# UCirKitBreadboardWithEverythingTop-08201.net
KiCad netlist of a schematic drawn in EAGLE
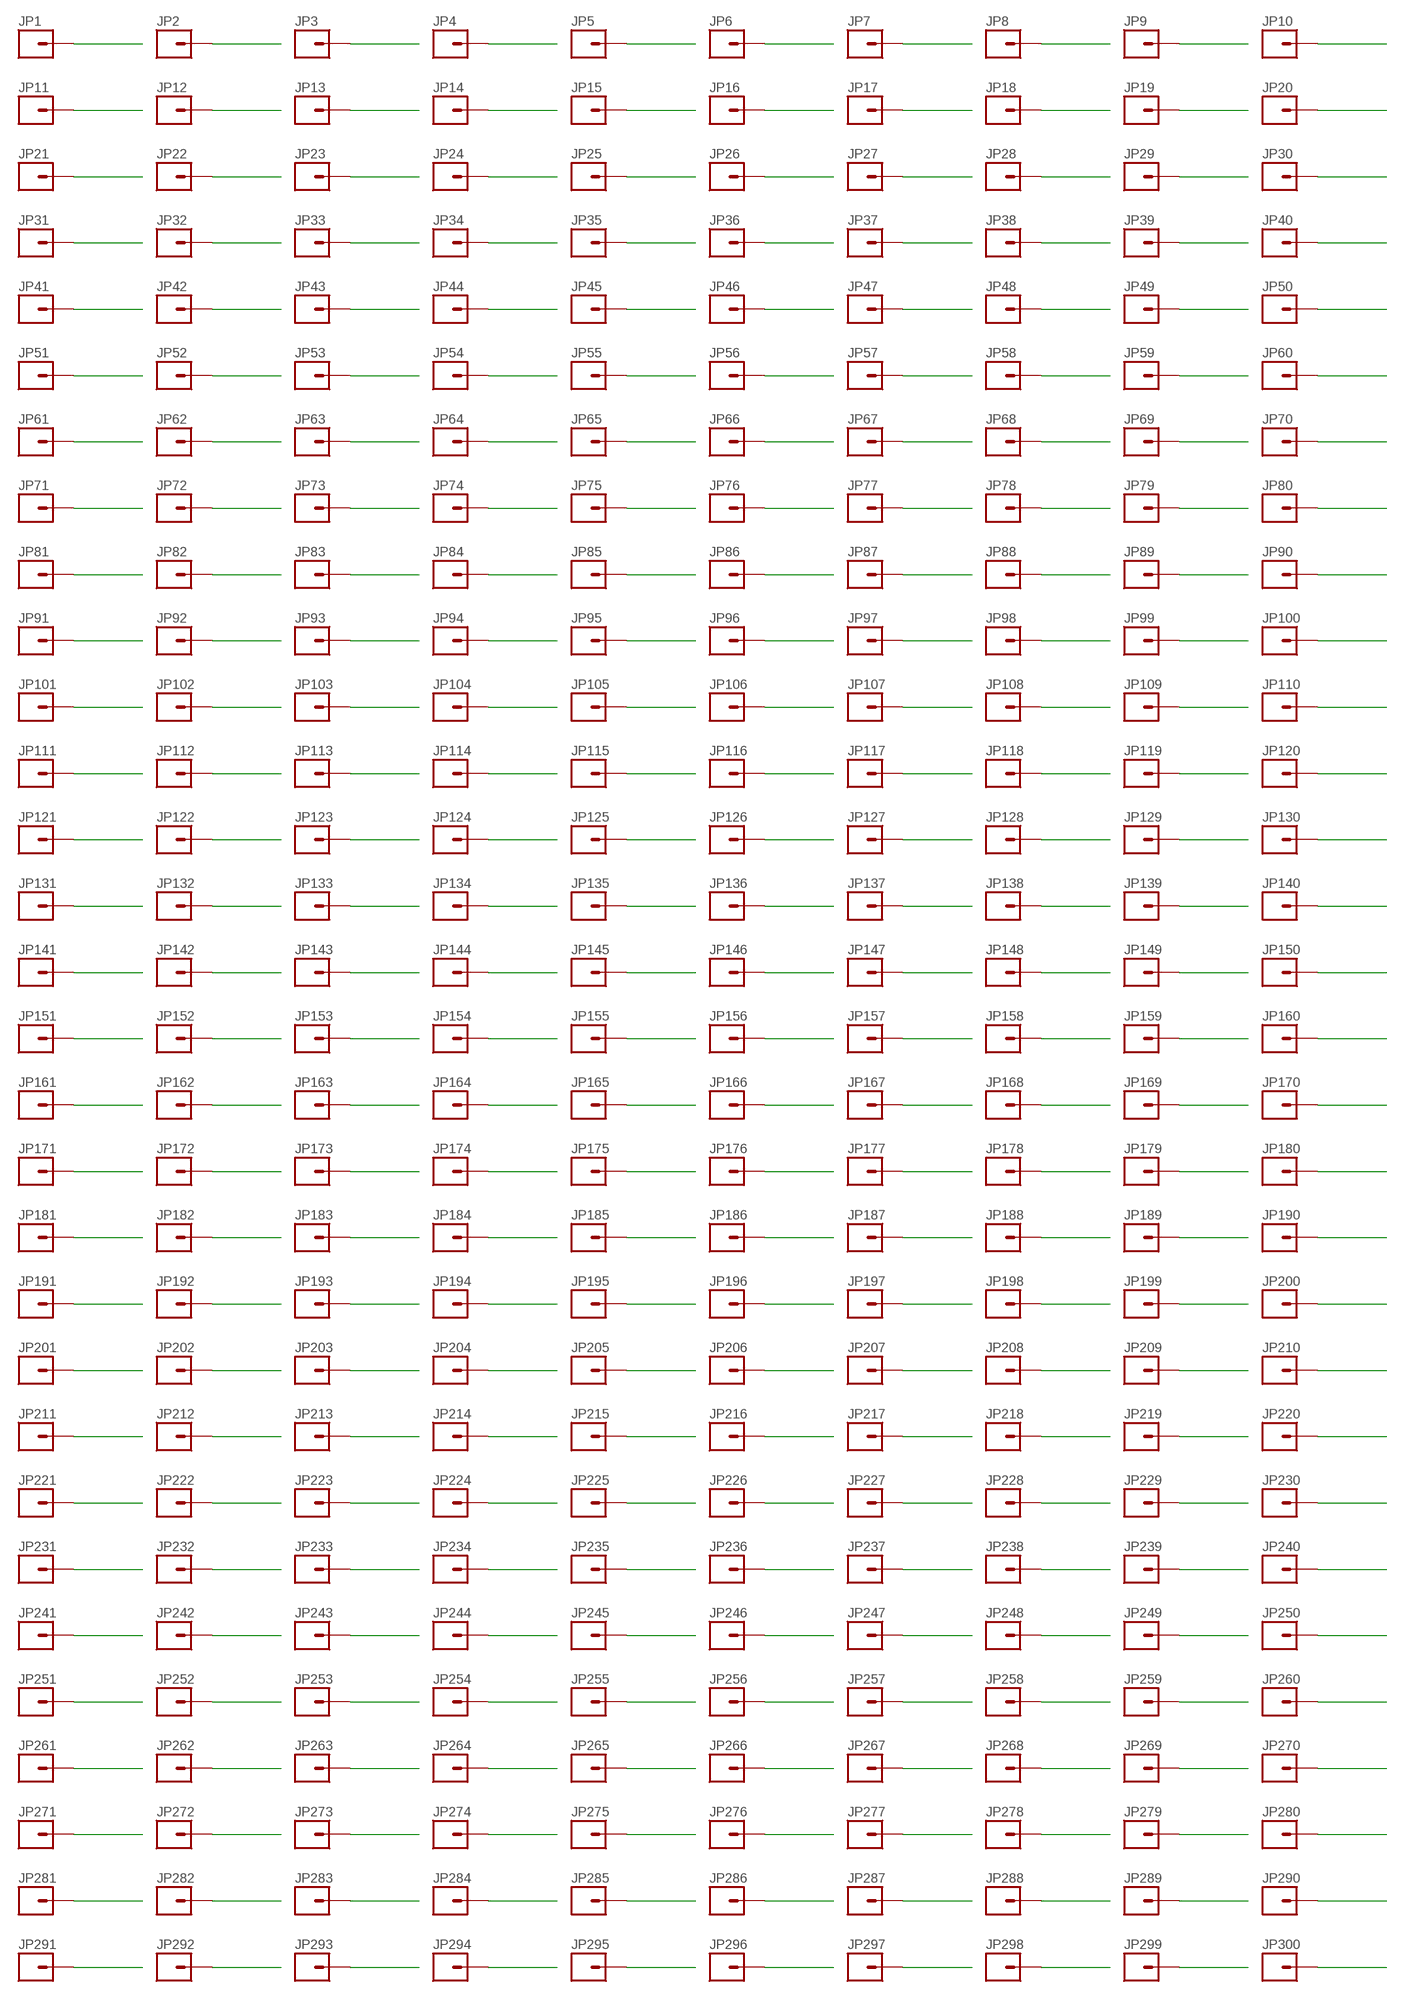
[diagram p0: schematic, sheet 1, part 1 of 2]
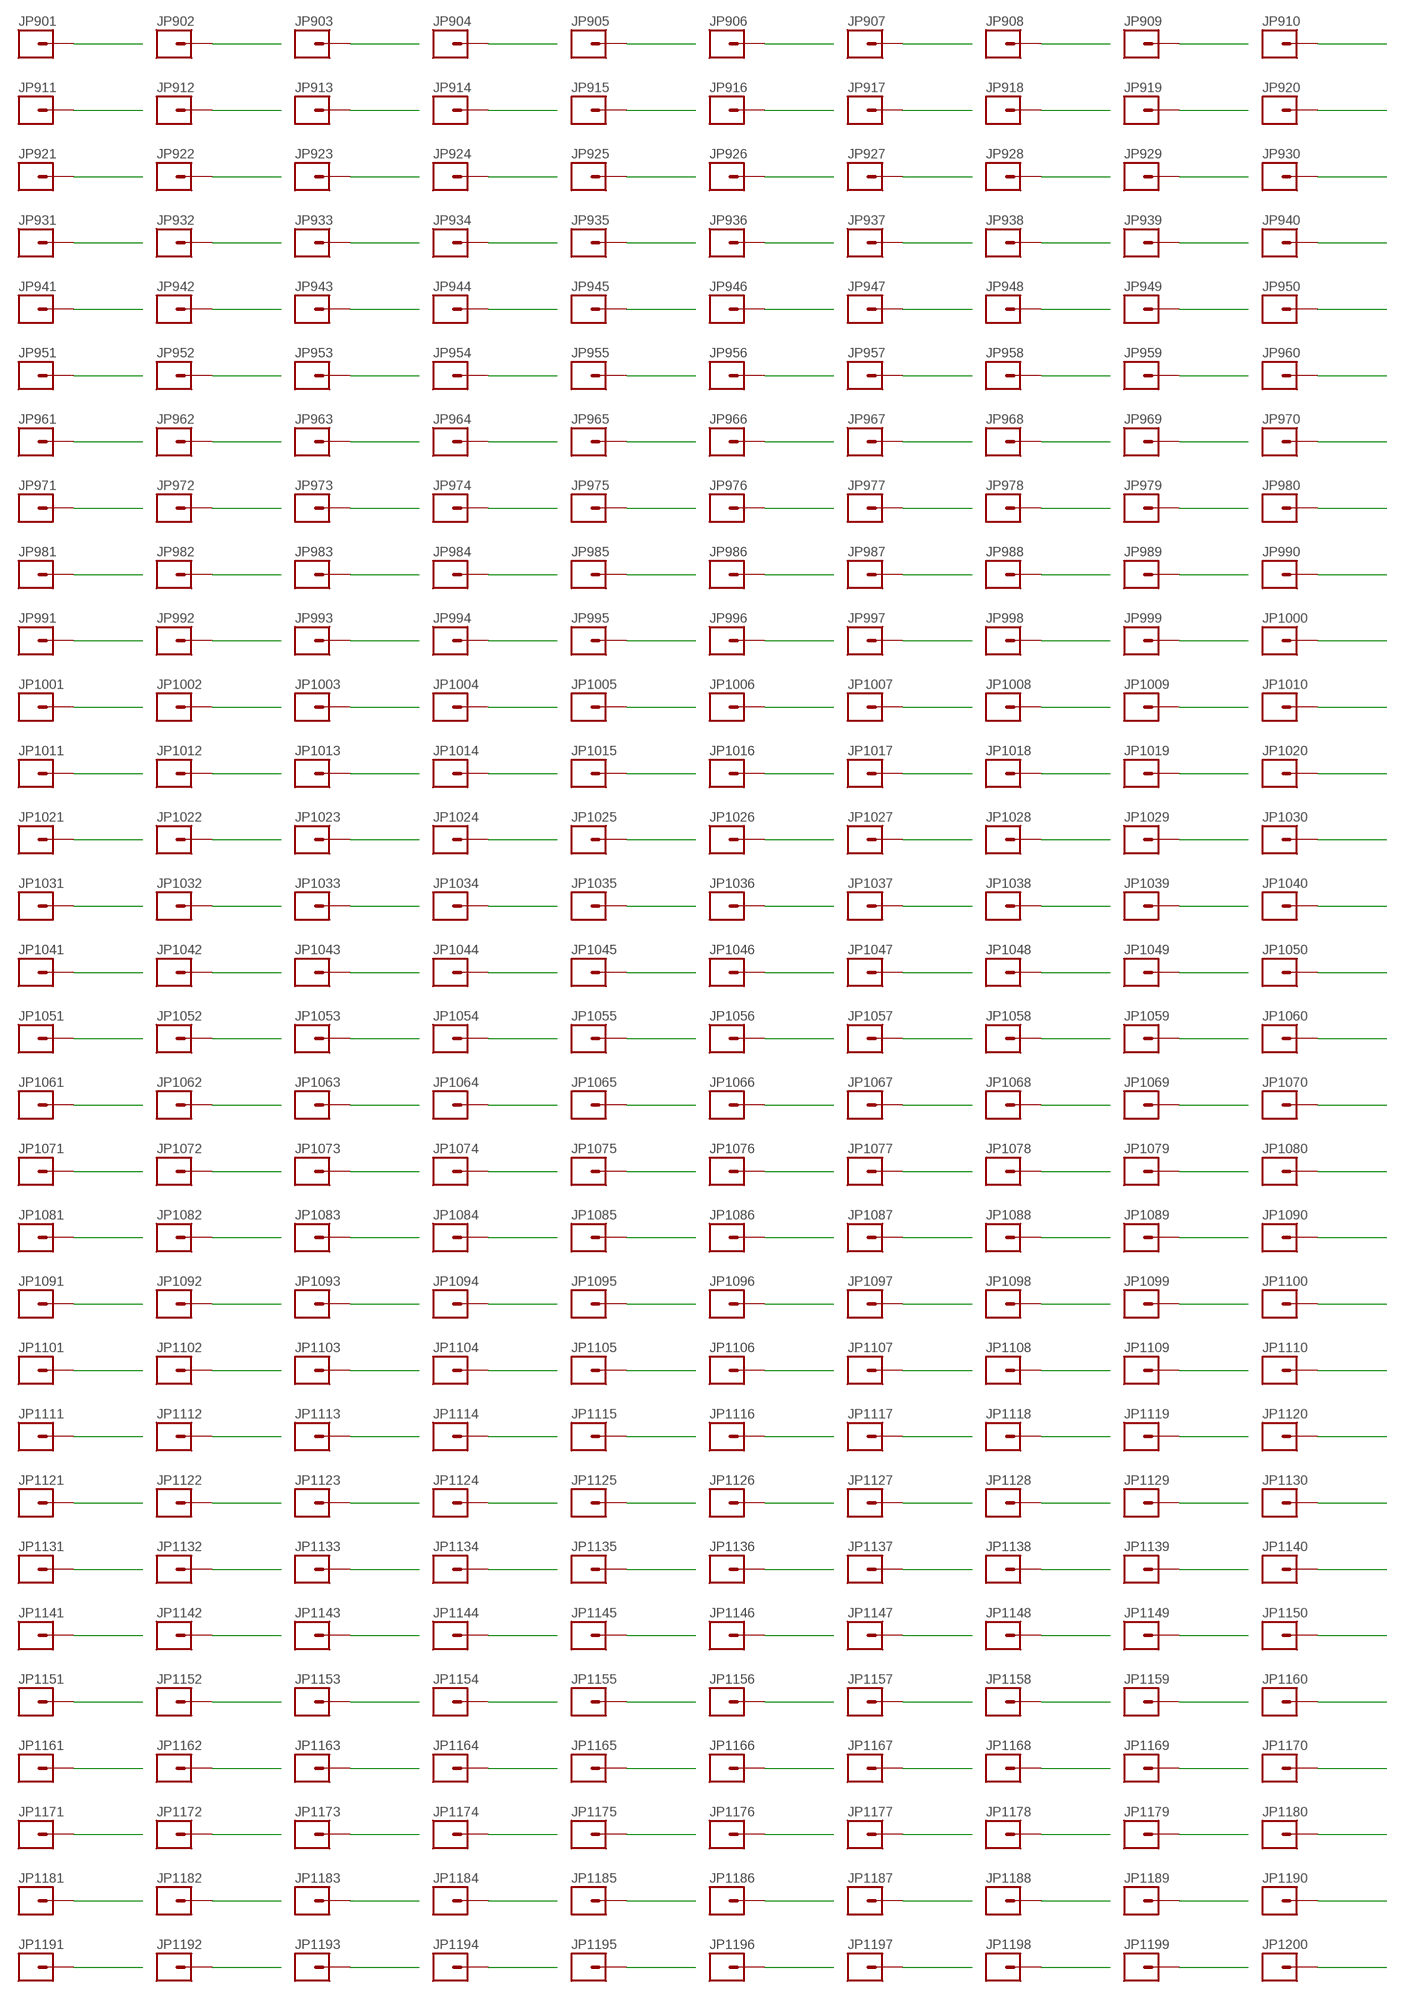
[diagram p1: schematic, sheet 1, part 2 of 2]

(export (version "E")
  (design (tool "Eeschema 10.0.6"))
  (components
    (comp (ref "JP1")
      (value "M01PTH_WITHOUT_TEXT")
      (footprint "eagle-import:1X01_WITHOUT_TEXT")
      (libsource (lib "eagle-import") (part "M01PTH_WITHOUT_TEXT"))
    )
    (comp (ref "JP2")
      (value "M01PTH_WITHOUT_TEXT")
      (footprint "eagle-import:1X01_WITHOUT_TEXT")
      (libsource (lib "eagle-import") (part "M01PTH_WITHOUT_TEXT"))
    )
    (comp (ref "JP3")
      (value "M01PTH_WITHOUT_TEXT")
      (footprint "eagle-import:1X01_WITHOUT_TEXT")
      (libsource (lib "eagle-import") (part "M01PTH_WITHOUT_TEXT"))
    )
    (comp (ref "JP4")
      (value "M01PTH_WITHOUT_TEXT")
      (footprint "eagle-import:1X01_WITHOUT_TEXT")
      (libsource (lib "eagle-import") (part "M01PTH_WITHOUT_TEXT"))
    )
    (comp (ref "JP5")
      (value "M01PTH_WITHOUT_TEXT")
      (footprint "eagle-import:1X01_WITHOUT_TEXT")
      (libsource (lib "eagle-import") (part "M01PTH_WITHOUT_TEXT"))
    )
    (comp (ref "JP6")
      (value "M01PTH_WITHOUT_TEXT")
      (footprint "eagle-import:1X01_WITHOUT_TEXT")
      (libsource (lib "eagle-import") (part "M01PTH_WITHOUT_TEXT"))
    )
    (comp (ref "JP7")
      (value "M01PTH_WITHOUT_TEXT")
      (footprint "eagle-import:1X01_WITHOUT_TEXT")
      (libsource (lib "eagle-import") (part "M01PTH_WITHOUT_TEXT"))
    )
    (comp (ref "JP8")
      (value "M01PTH_WITHOUT_TEXT")
      (footprint "eagle-import:1X01_WITHOUT_TEXT")
      (libsource (lib "eagle-import") (part "M01PTH_WITHOUT_TEXT"))
    )
    (comp (ref "JP9")
      (value "M01PTH_WITHOUT_TEXT")
      (footprint "eagle-import:1X01_WITHOUT_TEXT")
      (libsource (lib "eagle-import") (part "M01PTH_WITHOUT_TEXT"))
    )
    (comp (ref "JP10")
      (value "M01PTH_WITHOUT_TEXT")
      (footprint "eagle-import:1X01_WITHOUT_TEXT")
      (libsource (lib "eagle-import") (part "M01PTH_WITHOUT_TEXT"))
    )
    (comp (ref "JP11")
      (value "M01PTH_WITHOUT_TEXT")
      (footprint "eagle-import:1X01_WITHOUT_TEXT")
      (libsource (lib "eagle-import") (part "M01PTH_WITHOUT_TEXT"))
    )
    (comp (ref "JP12")
      (value "M01PTH_WITHOUT_TEXT")
      (footprint "eagle-import:1X01_WITHOUT_TEXT")
      (libsource (lib "eagle-import") (part "M01PTH_WITHOUT_TEXT"))
    )
    (comp (ref "JP13")
      (value "M01PTH_WITHOUT_TEXT")
      (footprint "eagle-import:1X01_WITHOUT_TEXT")
      (libsource (lib "eagle-import") (part "M01PTH_WITHOUT_TEXT"))
    )
    (comp (ref "JP14")
      (value "M01PTH_WITHOUT_TEXT")
      (footprint "eagle-import:1X01_WITHOUT_TEXT")
      (libsource (lib "eagle-import") (part "M01PTH_WITHOUT_TEXT"))
    )
    (comp (ref "JP15")
      (value "M01PTH_WITHOUT_TEXT")
      (footprint "eagle-import:1X01_WITHOUT_TEXT")
      (libsource (lib "eagle-import") (part "M01PTH_WITHOUT_TEXT"))
    )
    (comp (ref "JP16")
      (value "M01PTH_WITHOUT_TEXT")
      (footprint "eagle-import:1X01_WITHOUT_TEXT")
      (libsource (lib "eagle-import") (part "M01PTH_WITHOUT_TEXT"))
    )
    (comp (ref "JP17")
      (value "M01PTH_WITHOUT_TEXT")
      (footprint "eagle-import:1X01_WITHOUT_TEXT")
      (libsource (lib "eagle-import") (part "M01PTH_WITHOUT_TEXT"))
    )
    (comp (ref "JP18")
      (value "M01PTH_WITHOUT_TEXT")
      (footprint "eagle-import:1X01_WITHOUT_TEXT")
      (libsource (lib "eagle-import") (part "M01PTH_WITHOUT_TEXT"))
    )
    (comp (ref "JP19")
      (value "M01PTH_WITHOUT_TEXT")
      (footprint "eagle-import:1X01_WITHOUT_TEXT")
      (libsource (lib "eagle-import") (part "M01PTH_WITHOUT_TEXT"))
    )
    (comp (ref "JP20")
      (value "M01PTH_WITHOUT_TEXT")
      (footprint "eagle-import:1X01_WITHOUT_TEXT")
      (libsource (lib "eagle-import") (part "M01PTH_WITHOUT_TEXT"))
    )
    (comp (ref "JP21")
      (value "M01PTH_WITHOUT_TEXT")
      (footprint "eagle-import:1X01_WITHOUT_TEXT")
      (libsource (lib "eagle-import") (part "M01PTH_WITHOUT_TEXT"))
    )
    (comp (ref "JP22")
      (value "M01PTH_WITHOUT_TEXT")
      (footprint "eagle-import:1X01_WITHOUT_TEXT")
      (libsource (lib "eagle-import") (part "M01PTH_WITHOUT_TEXT"))
    )
    (comp (ref "JP23")
      (value "M01PTH_WITHOUT_TEXT")
      (footprint "eagle-import:1X01_WITHOUT_TEXT")
      (libsource (lib "eagle-import") (part "M01PTH_WITHOUT_TEXT"))
    )
    (comp (ref "JP24")
      (value "M01PTH_WITHOUT_TEXT")
      (footprint "eagle-import:1X01_WITHOUT_TEXT")
      (libsource (lib "eagle-import") (part "M01PTH_WITHOUT_TEXT"))
    )
    (comp (ref "JP25")
      (value "M01PTH_WITHOUT_TEXT")
      (footprint "eagle-import:1X01_WITHOUT_TEXT")
      (libsource (lib "eagle-import") (part "M01PTH_WITHOUT_TEXT"))
    )
    (comp (ref "JP26")
      (value "M01PTH_WITHOUT_TEXT")
      (footprint "eagle-import:1X01_WITHOUT_TEXT")
      (libsource (lib "eagle-import") (part "M01PTH_WITHOUT_TEXT"))
    )
    (comp (ref "JP27")
      (value "M01PTH_WITHOUT_TEXT")
      (footprint "eagle-import:1X01_WITHOUT_TEXT")
      (libsource (lib "eagle-import") (part "M01PTH_WITHOUT_TEXT"))
    )
    (comp (ref "JP28")
      (value "M01PTH_WITHOUT_TEXT")
      (footprint "eagle-import:1X01_WITHOUT_TEXT")
      (libsource (lib "eagle-import") (part "M01PTH_WITHOUT_TEXT"))
    )
    (comp (ref "JP29")
      (value "M01PTH_WITHOUT_TEXT")
      (footprint "eagle-import:1X01_WITHOUT_TEXT")
      (libsource (lib "eagle-import") (part "M01PTH_WITHOUT_TEXT"))
    )
    (comp (ref "JP30")
      (value "M01PTH_WITHOUT_TEXT")
      (footprint "eagle-import:1X01_WITHOUT_TEXT")
      (libsource (lib "eagle-import") (part "M01PTH_WITHOUT_TEXT"))
    )
    (comp (ref "JP31")
      (value "M01PTH_WITHOUT_TEXT")
      (footprint "eagle-import:1X01_WITHOUT_TEXT")
      (libsource (lib "eagle-import") (part "M01PTH_WITHOUT_TEXT"))
    )
    (comp (ref "JP32")
      (value "M01PTH_WITHOUT_TEXT")
      (footprint "eagle-import:1X01_WITHOUT_TEXT")
      (libsource (lib "eagle-import") (part "M01PTH_WITHOUT_TEXT"))
    )
    (comp (ref "JP33")
      (value "M01PTH_WITHOUT_TEXT")
      (footprint "eagle-import:1X01_WITHOUT_TEXT")
      (libsource (lib "eagle-import") (part "M01PTH_WITHOUT_TEXT"))
    )
    (comp (ref "JP34")
      (value "M01PTH_WITHOUT_TEXT")
      (footprint "eagle-import:1X01_WITHOUT_TEXT")
      (libsource (lib "eagle-import") (part "M01PTH_WITHOUT_TEXT"))
    )
    (comp (ref "JP35")
      (value "M01PTH_WITHOUT_TEXT")
      (footprint "eagle-import:1X01_WITHOUT_TEXT")
      (libsource (lib "eagle-import") (part "M01PTH_WITHOUT_TEXT"))
    )
    (comp (ref "JP36")
      (value "M01PTH_WITHOUT_TEXT")
      (footprint "eagle-import:1X01_WITHOUT_TEXT")
      (libsource (lib "eagle-import") (part "M01PTH_WITHOUT_TEXT"))
    )
    (comp (ref "JP37")
      (value "M01PTH_WITHOUT_TEXT")
      (footprint "eagle-import:1X01_WITHOUT_TEXT")
      (libsource (lib "eagle-import") (part "M01PTH_WITHOUT_TEXT"))
    )
    (comp (ref "JP38")
      (value "M01PTH_WITHOUT_TEXT")
      (footprint "eagle-import:1X01_WITHOUT_TEXT")
      (libsource (lib "eagle-import") (part "M01PTH_WITHOUT_TEXT"))
    )
    (comp (ref "JP39")
      (value "M01PTH_WITHOUT_TEXT")
      (footprint "eagle-import:1X01_WITHOUT_TEXT")
      (libsource (lib "eagle-import") (part "M01PTH_WITHOUT_TEXT"))
    )
    (comp (ref "JP40")
      (value "M01PTH_WITHOUT_TEXT")
      (footprint "eagle-import:1X01_WITHOUT_TEXT")
      (libsource (lib "eagle-import") (part "M01PTH_WITHOUT_TEXT"))
    )
    (comp (ref "JP41")
      (value "M01PTH_WITHOUT_TEXT")
      (footprint "eagle-import:1X01_WITHOUT_TEXT")
      (libsource (lib "eagle-import") (part "M01PTH_WITHOUT_TEXT"))
    )
    (comp (ref "JP42")
      (value "M01PTH_WITHOUT_TEXT")
      (footprint "eagle-import:1X01_WITHOUT_TEXT")
      (libsource (lib "eagle-import") (part "M01PTH_WITHOUT_TEXT"))
    )
    (comp (ref "JP43")
      (value "M01PTH_WITHOUT_TEXT")
      (footprint "eagle-import:1X01_WITHOUT_TEXT")
      (libsource (lib "eagle-import") (part "M01PTH_WITHOUT_TEXT"))
    )
    (comp (ref "JP44")
      (value "M01PTH_WITHOUT_TEXT")
      (footprint "eagle-import:1X01_WITHOUT_TEXT")
      (libsource (lib "eagle-import") (part "M01PTH_WITHOUT_TEXT"))
    )
    (comp (ref "JP45")
      (value "M01PTH_WITHOUT_TEXT")
      (footprint "eagle-import:1X01_WITHOUT_TEXT")
      (libsource (lib "eagle-import") (part "M01PTH_WITHOUT_TEXT"))
    )
    (comp (ref "JP46")
      (value "M01PTH_WITHOUT_TEXT")
      (footprint "eagle-import:1X01_WITHOUT_TEXT")
      (libsource (lib "eagle-import") (part "M01PTH_WITHOUT_TEXT"))
    )
    (comp (ref "JP47")
      (value "M01PTH_WITHOUT_TEXT")
      (footprint "eagle-import:1X01_WITHOUT_TEXT")
      (libsource (lib "eagle-import") (part "M01PTH_WITHOUT_TEXT"))
    )
    (comp (ref "JP48")
      (value "M01PTH_WITHOUT_TEXT")
      (footprint "eagle-import:1X01_WITHOUT_TEXT")
      (libsource (lib "eagle-import") (part "M01PTH_WITHOUT_TEXT"))
    )
    (comp (ref "JP49")
      (value "M01PTH_WITHOUT_TEXT")
      (footprint "eagle-import:1X01_WITHOUT_TEXT")
      (libsource (lib "eagle-import") (part "M01PTH_WITHOUT_TEXT"))
    )
    (comp (ref "JP50")
      (value "M01PTH_WITHOUT_TEXT")
      (footprint "eagle-import:1X01_WITHOUT_TEXT")
      (libsource (lib "eagle-import") (part "M01PTH_WITHOUT_TEXT"))
    )
    (comp (ref "JP51")
      (value "M01PTH_WITHOUT_TEXT")
      (footprint "eagle-import:1X01_WITHOUT_TEXT")
      (libsource (lib "eagle-import") (part "M01PTH_WITHOUT_TEXT"))
    )
    (comp (ref "JP52")
      (value "M01PTH_WITHOUT_TEXT")
      (footprint "eagle-import:1X01_WITHOUT_TEXT")
      (libsource (lib "eagle-import") (part "M01PTH_WITHOUT_TEXT"))
    )
    (comp (ref "JP53")
      (value "M01PTH_WITHOUT_TEXT")
      (footprint "eagle-import:1X01_WITHOUT_TEXT")
      (libsource (lib "eagle-import") (part "M01PTH_WITHOUT_TEXT"))
    )
    (comp (ref "JP54")
      (value "M01PTH_WITHOUT_TEXT")
      (footprint "eagle-import:1X01_WITHOUT_TEXT")
      (libsource (lib "eagle-import") (part "M01PTH_WITHOUT_TEXT"))
    )
    (comp (ref "JP55")
      (value "M01PTH_WITHOUT_TEXT")
      (footprint "eagle-import:1X01_WITHOUT_TEXT")
      (libsource (lib "eagle-import") (part "M01PTH_WITHOUT_TEXT"))
    )
    (comp (ref "JP56")
      (value "M01PTH_WITHOUT_TEXT")
      (footprint "eagle-import:1X01_WITHOUT_TEXT")
      (libsource (lib "eagle-import") (part "M01PTH_WITHOUT_TEXT"))
    )
    (comp (ref "JP57")
      (value "M01PTH_WITHOUT_TEXT")
      (footprint "eagle-import:1X01_WITHOUT_TEXT")
      (libsource (lib "eagle-import") (part "M01PTH_WITHOUT_TEXT"))
    )
    (comp (ref "JP58")
      (value "M01PTH_WITHOUT_TEXT")
      (footprint "eagle-import:1X01_WITHOUT_TEXT")
      (libsource (lib "eagle-import") (part "M01PTH_WITHOUT_TEXT"))
    )
    (comp (ref "JP59")
      (value "M01PTH_WITHOUT_TEXT")
      (footprint "eagle-import:1X01_WITHOUT_TEXT")
      (libsource (lib "eagle-import") (part "M01PTH_WITHOUT_TEXT"))
    )
    (comp (ref "JP60")
      (value "M01PTH_WITHOUT_TEXT")
      (footprint "eagle-import:1X01_WITHOUT_TEXT")
      (libsource (lib "eagle-import") (part "M01PTH_WITHOUT_TEXT"))
    )
    (comp (ref "JP61")
      (value "M01PTH_WITHOUT_TEXT")
      (footprint "eagle-import:1X01_WITHOUT_TEXT")
      (libsource (lib "eagle-import") (part "M01PTH_WITHOUT_TEXT"))
    )
    (comp (ref "JP62")
      (value "M01PTH_WITHOUT_TEXT")
      (footprint "eagle-import:1X01_WITHOUT_TEXT")
      (libsource (lib "eagle-import") (part "M01PTH_WITHOUT_TEXT"))
    )
    (comp (ref "JP63")
      (value "M01PTH_WITHOUT_TEXT")
      (footprint "eagle-import:1X01_WITHOUT_TEXT")
      (libsource (lib "eagle-import") (part "M01PTH_WITHOUT_TEXT"))
    )
    (comp (ref "JP64")
      (value "M01PTH_WITHOUT_TEXT")
      (footprint "eagle-import:1X01_WITHOUT_TEXT")
      (libsource (lib "eagle-import") (part "M01PTH_WITHOUT_TEXT"))
    )
    (comp (ref "JP65")
      (value "M01PTH_WITHOUT_TEXT")
      (footprint "eagle-import:1X01_WITHOUT_TEXT")
      (libsource (lib "eagle-import") (part "M01PTH_WITHOUT_TEXT"))
    )
    (comp (ref "JP66")
      (value "M01PTH_WITHOUT_TEXT")
      (footprint "eagle-import:1X01_WITHOUT_TEXT")
      (libsource (lib "eagle-import") (part "M01PTH_WITHOUT_TEXT"))
    )
    (comp (ref "JP67")
      (value "M01PTH_WITHOUT_TEXT")
      (footprint "eagle-import:1X01_WITHOUT_TEXT")
      (libsource (lib "eagle-import") (part "M01PTH_WITHOUT_TEXT"))
    )
    (comp (ref "JP68")
      (value "M01PTH_WITHOUT_TEXT")
      (footprint "eagle-import:1X01_WITHOUT_TEXT")
      (libsource (lib "eagle-import") (part "M01PTH_WITHOUT_TEXT"))
    )
    (comp (ref "JP69")
      (value "M01PTH_WITHOUT_TEXT")
      (footprint "eagle-import:1X01_WITHOUT_TEXT")
      (libsource (lib "eagle-import") (part "M01PTH_WITHOUT_TEXT"))
    )
    (comp (ref "JP70")
      (value "M01PTH_WITHOUT_TEXT")
      (footprint "eagle-import:1X01_WITHOUT_TEXT")
      (libsource (lib "eagle-import") (part "M01PTH_WITHOUT_TEXT"))
    )
    (comp (ref "JP71")
      (value "M01PTH_WITHOUT_TEXT")
      (footprint "eagle-import:1X01_WITHOUT_TEXT")
      (libsource (lib "eagle-import") (part "M01PTH_WITHOUT_TEXT"))
    )
    (comp (ref "JP72")
      (value "M01PTH_WITHOUT_TEXT")
      (footprint "eagle-import:1X01_WITHOUT_TEXT")
      (libsource (lib "eagle-import") (part "M01PTH_WITHOUT_TEXT"))
    )
    (comp (ref "JP73")
      (value "M01PTH_WITHOUT_TEXT")
      (footprint "eagle-import:1X01_WITHOUT_TEXT")
      (libsource (lib "eagle-import") (part "M01PTH_WITHOUT_TEXT"))
    )
    (comp (ref "JP74")
      (value "M01PTH_WITHOUT_TEXT")
      (footprint "eagle-import:1X01_WITHOUT_TEXT")
      (libsource (lib "eagle-import") (part "M01PTH_WITHOUT_TEXT"))
    )
    (comp (ref "JP75")
      (value "M01PTH_WITHOUT_TEXT")
      (footprint "eagle-import:1X01_WITHOUT_TEXT")
      (libsource (lib "eagle-import") (part "M01PTH_WITHOUT_TEXT"))
    )
    (comp (ref "JP76")
      (value "M01PTH_WITHOUT_TEXT")
      (footprint "eagle-import:1X01_WITHOUT_TEXT")
      (libsource (lib "eagle-import") (part "M01PTH_WITHOUT_TEXT"))
    )
    (comp (ref "JP77")
      (value "M01PTH_WITHOUT_TEXT")
      (footprint "eagle-import:1X01_WITHOUT_TEXT")
      (libsource (lib "eagle-import") (part "M01PTH_WITHOUT_TEXT"))
    )
    (comp (ref "JP78")
      (value "M01PTH_WITHOUT_TEXT")
      (footprint "eagle-import:1X01_WITHOUT_TEXT")
      (libsource (lib "eagle-import") (part "M01PTH_WITHOUT_TEXT"))
    )
    (comp (ref "JP79")
      (value "M01PTH_WITHOUT_TEXT")
      (footprint "eagle-import:1X01_WITHOUT_TEXT")
      (libsource (lib "eagle-import") (part "M01PTH_WITHOUT_TEXT"))
    )
    (comp (ref "JP80")
      (value "M01PTH_WITHOUT_TEXT")
      (footprint "eagle-import:1X01_WITHOUT_TEXT")
      (libsource (lib "eagle-import") (part "M01PTH_WITHOUT_TEXT"))
    )
    (comp (ref "JP81")
      (value "M01PTH_WITHOUT_TEXT")
      (footprint "eagle-import:1X01_WITHOUT_TEXT")
      (libsource (lib "eagle-import") (part "M01PTH_WITHOUT_TEXT"))
    )
    (comp (ref "JP82")
      (value "M01PTH_WITHOUT_TEXT")
      (footprint "eagle-import:1X01_WITHOUT_TEXT")
      (libsource (lib "eagle-import") (part "M01PTH_WITHOUT_TEXT"))
    )
    (comp (ref "JP83")
      (value "M01PTH_WITHOUT_TEXT")
      (footprint "eagle-import:1X01_WITHOUT_TEXT")
      (libsource (lib "eagle-import") (part "M01PTH_WITHOUT_TEXT"))
    )
    (comp (ref "JP84")
      (value "M01PTH_WITHOUT_TEXT")
      (footprint "eagle-import:1X01_WITHOUT_TEXT")
      (libsource (lib "eagle-import") (part "M01PTH_WITHOUT_TEXT"))
    )
    (comp (ref "JP85")
      (value "M01PTH_WITHOUT_TEXT")
      (footprint "eagle-import:1X01_WITHOUT_TEXT")
      (libsource (lib "eagle-import") (part "M01PTH_WITHOUT_TEXT"))
    )
    (comp (ref "JP86")
      (value "M01PTH_WITHOUT_TEXT")
      (footprint "eagle-import:1X01_WITHOUT_TEXT")
      (libsource (lib "eagle-import") (part "M01PTH_WITHOUT_TEXT"))
    )
    (comp (ref "JP87")
      (value "M01PTH_WITHOUT_TEXT")
      (footprint "eagle-import:1X01_WITHOUT_TEXT")
      (libsource (lib "eagle-import") (part "M01PTH_WITHOUT_TEXT"))
    )
    (comp (ref "JP88")
      (value "M01PTH_WITHOUT_TEXT")
      (footprint "eagle-import:1X01_WITHOUT_TEXT")
      (libsource (lib "eagle-import") (part "M01PTH_WITHOUT_TEXT"))
    )
    (comp (ref "JP89")
      (value "M01PTH_WITHOUT_TEXT")
      (footprint "eagle-import:1X01_WITHOUT_TEXT")
      (libsource (lib "eagle-import") (part "M01PTH_WITHOUT_TEXT"))
    )
    (comp (ref "JP90")
      (value "M01PTH_WITHOUT_TEXT")
      (footprint "eagle-import:1X01_WITHOUT_TEXT")
      (libsource (lib "eagle-import") (part "M01PTH_WITHOUT_TEXT"))
    )
    (comp (ref "JP91")
      (value "M01PTH_WITHOUT_TEXT")
      (footprint "eagle-import:1X01_WITHOUT_TEXT")
      (libsource (lib "eagle-import") (part "M01PTH_WITHOUT_TEXT"))
    )
    (comp (ref "JP92")
      (value "M01PTH_WITHOUT_TEXT")
      (footprint "eagle-import:1X01_WITHOUT_TEXT")
      (libsource (lib "eagle-import") (part "M01PTH_WITHOUT_TEXT"))
    )
    (comp (ref "JP93")
      (value "M01PTH_WITHOUT_TEXT")
      (footprint "eagle-import:1X01_WITHOUT_TEXT")
      (libsource (lib "eagle-import") (part "M01PTH_WITHOUT_TEXT"))
    )
    (comp (ref "JP94")
      (value "M01PTH_WITHOUT_TEXT")
      (footprint "eagle-import:1X01_WITHOUT_TEXT")
      (libsource (lib "eagle-import") (part "M01PTH_WITHOUT_TEXT"))
    )
    (comp (ref "JP95")
      (value "M01PTH_WITHOUT_TEXT")
      (footprint "eagle-import:1X01_WITHOUT_TEXT")
      (libsource (lib "eagle-import") (part "M01PTH_WITHOUT_TEXT"))
    )
    (comp (ref "JP96")
      (value "M01PTH_WITHOUT_TEXT")
      (footprint "eagle-import:1X01_WITHOUT_TEXT")
      (libsource (lib "eagle-import") (part "M01PTH_WITHOUT_TEXT"))
    )
    (comp (ref "JP97")
      (value "M01PTH_WITHOUT_TEXT")
      (footprint "eagle-import:1X01_WITHOUT_TEXT")
      (libsource (lib "eagle-import") (part "M01PTH_WITHOUT_TEXT"))
    )
    (comp (ref "JP98")
      (value "M01PTH_WITHOUT_TEXT")
      (footprint "eagle-import:1X01_WITHOUT_TEXT")
      (libsource (lib "eagle-import") (part "M01PTH_WITHOUT_TEXT"))
    )
    (comp (ref "JP99")
      (value "M01PTH_WITHOUT_TEXT")
      (footprint "eagle-import:1X01_WITHOUT_TEXT")
      (libsource (lib "eagle-import") (part "M01PTH_WITHOUT_TEXT"))
    )
    (comp (ref "JP100")
      (value "M01PTH_WITHOUT_TEXT")
      (footprint "eagle-import:1X01_WITHOUT_TEXT")
      (libsource (lib "eagle-import") (part "M01PTH_WITHOUT_TEXT"))
    )
    (comp (ref "JP101")
      (value "M01PTH_WITHOUT_TEXT")
      (footprint "eagle-import:1X01_WITHOUT_TEXT")
      (libsource (lib "eagle-import") (part "M01PTH_WITHOUT_TEXT"))
    )
    (comp (ref "JP102")
      (value "M01PTH_WITHOUT_TEXT")
      (footprint "eagle-import:1X01_WITHOUT_TEXT")
      (libsource (lib "eagle-import") (part "M01PTH_WITHOUT_TEXT"))
    )
    (comp (ref "JP103")
      (value "M01PTH_WITHOUT_TEXT")
      (footprint "eagle-import:1X01_WITHOUT_TEXT")
      (libsource (lib "eagle-import") (part "M01PTH_WITHOUT_TEXT"))
    )
    (comp (ref "JP104")
      (value "M01PTH_WITHOUT_TEXT")
      (footprint "eagle-import:1X01_WITHOUT_TEXT")
      (libsource (lib "eagle-import") (part "M01PTH_WITHOUT_TEXT"))
    )
    (comp (ref "JP105")
      (value "M01PTH_WITHOUT_TEXT")
      (footprint "eagle-import:1X01_WITHOUT_TEXT")
      (libsource (lib "eagle-import") (part "M01PTH_WITHOUT_TEXT"))
    )
    (comp (ref "JP106")
      (value "M01PTH_WITHOUT_TEXT")
      (footprint "eagle-import:1X01_WITHOUT_TEXT")
      (libsource (lib "eagle-import") (part "M01PTH_WITHOUT_TEXT"))
    )
    (comp (ref "JP107")
      (value "M01PTH_WITHOUT_TEXT")
      (footprint "eagle-import:1X01_WITHOUT_TEXT")
      (libsource (lib "eagle-import") (part "M01PTH_WITHOUT_TEXT"))
    )
    (comp (ref "JP108")
      (value "M01PTH_WITHOUT_TEXT")
      (footprint "eagle-import:1X01_WITHOUT_TEXT")
      (libsource (lib "eagle-import") (part "M01PTH_WITHOUT_TEXT"))
    )
    (comp (ref "JP109")
      (value "M01PTH_WITHOUT_TEXT")
      (footprint "eagle-import:1X01_WITHOUT_TEXT")
      (libsource (lib "eagle-import") (part "M01PTH_WITHOUT_TEXT"))
    )
    (comp (ref "JP110")
      (value "M01PTH_WITHOUT_TEXT")
      (footprint "eagle-import:1X01_WITHOUT_TEXT")
      (libsource (lib "eagle-import") (part "M01PTH_WITHOUT_TEXT"))
    )
    (comp (ref "JP111")
      (value "M01PTH_WITHOUT_TEXT")
      (footprint "eagle-import:1X01_WITHOUT_TEXT")
      (libsource (lib "eagle-import") (part "M01PTH_WITHOUT_TEXT"))
    )
    (comp (ref "JP112")
      (value "M01PTH_WITHOUT_TEXT")
      (footprint "eagle-import:1X01_WITHOUT_TEXT")
      (libsource (lib "eagle-import") (part "M01PTH_WITHOUT_TEXT"))
    )
    (comp (ref "JP113")
      (value "M01PTH_WITHOUT_TEXT")
      (footprint "eagle-import:1X01_WITHOUT_TEXT")
      (libsource (lib "eagle-import") (part "M01PTH_WITHOUT_TEXT"))
    )
    (comp (ref "JP114")
      (value "M01PTH_WITHOUT_TEXT")
      (footprint "eagle-import:1X01_WITHOUT_TEXT")
      (libsource (lib "eagle-import") (part "M01PTH_WITHOUT_TEXT"))
    )
    (comp (ref "JP115")
      (value "M01PTH_WITHOUT_TEXT")
      (footprint "eagle-import:1X01_WITHOUT_TEXT")
      (libsource (lib "eagle-import") (part "M01PTH_WITHOUT_TEXT"))
    )
    (comp (ref "JP116")
      (value "M01PTH_WITHOUT_TEXT")
      (footprint "eagle-import:1X01_WITHOUT_TEXT")
      (libsource (lib "eagle-import") (part "M01PTH_WITHOUT_TEXT"))
    )
    (comp (ref "JP117")
      (value "M01PTH_WITHOUT_TEXT")
      (footprint "eagle-import:1X01_WITHOUT_TEXT")
      (libsource (lib "eagle-import") (part "M01PTH_WITHOUT_TEXT"))
    )
    (comp (ref "JP118")
      (value "M01PTH_WITHOUT_TEXT")
      (footprint "eagle-import:1X01_WITHOUT_TEXT")
      (libsource (lib "eagle-import") (part "M01PTH_WITHOUT_TEXT"))
    )
    (comp (ref "JP119")
      (value "M01PTH_WITHOUT_TEXT")
      (footprint "eagle-import:1X01_WITHOUT_TEXT")
      (libsource (lib "eagle-import") (part "M01PTH_WITHOUT_TEXT"))
    )
    (comp (ref "JP120")
      (value "M01PTH_WITHOUT_TEXT")
      (footprint "eagle-import:1X01_WITHOUT_TEXT")
      (libsource (lib "eagle-import") (part "M01PTH_WITHOUT_TEXT"))
    )
    (comp (ref "JP121")
      (value "M01PTH_WITHOUT_TEXT")
      (footprint "eagle-import:1X01_WITHOUT_TEXT")
      (libsource (lib "eagle-import") (part "M01PTH_WITHOUT_TEXT"))
    )
    (comp (ref "JP122")
      (value "M01PTH_WITHOUT_TEXT")
      (footprint "eagle-import:1X01_WITHOUT_TEXT")
      (libsource (lib "eagle-import") (part "M01PTH_WITHOUT_TEXT"))
    )
    (comp (ref "JP123")
      (value "M01PTH_WITHOUT_TEXT")
      (footprint "eagle-import:1X01_WITHOUT_TEXT")
      (libsource (lib "eagle-import") (part "M01PTH_WITHOUT_TEXT"))
    )
    (comp (ref "JP124")
      (value "M01PTH_WITHOUT_TEXT")
      (footprint "eagle-import:1X01_WITHOUT_TEXT")
      (libsource (lib "eagle-import") (part "M01PTH_WITHOUT_TEXT"))
    )
    (comp (ref "JP125")
      (value "M01PTH_WITHOUT_TEXT")
      (footprint "eagle-import:1X01_WITHOUT_TEXT")
      (libsource (lib "eagle-import") (part "M01PTH_WITHOUT_TEXT"))
    )
    (comp (ref "JP126")
      (value "M01PTH_WITHOUT_TEXT")
      (footprint "eagle-import:1X01_WITHOUT_TEXT")
      (libsource (lib "eagle-import") (part "M01PTH_WITHOUT_TEXT"))
    )
    (comp (ref "JP127")
      (value "M01PTH_WITHOUT_TEXT")
      (footprint "eagle-import:1X01_WITHOUT_TEXT")
      (libsource (lib "eagle-import") (part "M01PTH_WITHOUT_TEXT"))
    )
    (comp (ref "JP128")
      (value "M01PTH_WITHOUT_TEXT")
      (footprint "eagle-import:1X01_WITHOUT_TEXT")
      (libsource (lib "eagle-import") (part "M01PTH_WITHOUT_TEXT"))
    )
    (comp (ref "JP129")
      (value "M01PTH_WITHOUT_TEXT")
      (footprint "eagle-import:1X01_WITHOUT_TEXT")
      (libsource (lib "eagle-import") (part "M01PTH_WITHOUT_TEXT"))
    )
    (comp (ref "JP130")
      (value "M01PTH_WITHOUT_TEXT")
      (footprint "eagle-import:1X01_WITHOUT_TEXT")
      (libsource (lib "eagle-import") (part "M01PTH_WITHOUT_TEXT"))
    )
    (comp (ref "JP131")
      (value "M01PTH_WITHOUT_TEXT")
      (footprint "eagle-import:1X01_WITHOUT_TEXT")
      (libsource (lib "eagle-import") (part "M01PTH_WITHOUT_TEXT"))
    )
    (comp (ref "JP132")
      (value "M01PTH_WITHOUT_TEXT")
      (footprint "eagle-import:1X01_WITHOUT_TEXT")
      (libsource (lib "eagle-import") (part "M01PTH_WITHOUT_TEXT"))
    )
    (comp (ref "JP133")
      (value "M01PTH_WITHOUT_TEXT")
      (footprint "eagle-import:1X01_WITHOUT_TEXT")
      (libsource (lib "eagle-import") (part "M01PTH_WITHOUT_TEXT"))
    )
    (comp (ref "JP134")
      (value "M01PTH_WITHOUT_TEXT")
      (footprint "eagle-import:1X01_WITHOUT_TEXT")
      (libsource (lib "eagle-import") (part "M01PTH_WITHOUT_TEXT"))
    )
    (comp (ref "JP135")
      (value "M01PTH_WITHOUT_TEXT")
      (footprint "eagle-import:1X01_WITHOUT_TEXT")
      (libsource (lib "eagle-import") (part "M01PTH_WITHOUT_TEXT"))
    )
    (comp (ref "JP136")
      (value "M01PTH_WITHOUT_TEXT")
      (footprint "eagle-import:1X01_WITHOUT_TEXT")
      (libsource (lib "eagle-import") (part "M01PTH_WITHOUT_TEXT"))
    )
    (comp (ref "JP137")
      (value "M01PTH_WITHOUT_TEXT")
      (footprint "eagle-import:1X01_WITHOUT_TEXT")
      (libsource (lib "eagle-import") (part "M01PTH_WITHOUT_TEXT"))
    )
    (comp (ref "JP138")
      (value "M01PTH_WITHOUT_TEXT")
      (footprint "eagle-import:1X01_WITHOUT_TEXT")
      (libsource (lib "eagle-import") (part "M01PTH_WITHOUT_TEXT"))
    )
    (comp (ref "JP139")
      (value "M01PTH_WITHOUT_TEXT")
      (footprint "eagle-import:1X01_WITHOUT_TEXT")
      (libsource (lib "eagle-import") (part "M01PTH_WITHOUT_TEXT"))
    )
    (comp (ref "JP140")
      (value "M01PTH_WITHOUT_TEXT")
      (footprint "eagle-import:1X01_WITHOUT_TEXT")
      (libsource (lib "eagle-import") (part "M01PTH_WITHOUT_TEXT"))
    )
    (comp (ref "JP141")
      (value "M01PTH_WITHOUT_TEXT")
      (footprint "eagle-import:1X01_WITHOUT_TEXT")
      (libsource (lib "eagle-import") (part "M01PTH_WITHOUT_TEXT"))
    )
    (comp (ref "JP142")
      (value "M01PTH_WITHOUT_TEXT")
      (footprint "eagle-import:1X01_WITHOUT_TEXT")
      (libsource (lib "eagle-import") (part "M01PTH_WITHOUT_TEXT"))
    )
    (comp (ref "JP143")
      (value "M01PTH_WITHOUT_TEXT")
      (footprint "eagle-import:1X01_WITHOUT_TEXT")
      (libsource (lib "eagle-import") (part "M01PTH_WITHOUT_TEXT"))
    )
    (comp (ref "JP144")
      (value "M01PTH_WITHOUT_TEXT")
      (footprint "eagle-import:1X01_WITHOUT_TEXT")
      (libsource (lib "eagle-import") (part "M01PTH_WITHOUT_TEXT"))
    )
    (comp (ref "JP145")
      (value "M01PTH_WITHOUT_TEXT")
      (footprint "eagle-import:1X01_WITHOUT_TEXT")
      (libsource (lib "eagle-import") (part "M01PTH_WITHOUT_TEXT"))
    )
    (comp (ref "JP146")
      (value "M01PTH_WITHOUT_TEXT")
      (footprint "eagle-import:1X01_WITHOUT_TEXT")
      (libsource (lib "eagle-import") (part "M01PTH_WITHOUT_TEXT"))
    )
    (comp (ref "JP147")
      (value "M01PTH_WITHOUT_TEXT")
      (footprint "eagle-import:1X01_WITHOUT_TEXT")
      (libsource (lib "eagle-import") (part "M01PTH_WITHOUT_TEXT"))
    )
    (comp (ref "JP148")
      (value "M01PTH_WITHOUT_TEXT")
      (footprint "eagle-import:1X01_WITHOUT_TEXT")
      (libsource (lib "eagle-import") (part "M01PTH_WITHOUT_TEXT"))
    )
    (comp (ref "JP149")
      (value "M01PTH_WITHOUT_TEXT")
      (footprint "eagle-import:1X01_WITHOUT_TEXT")
      (libsource (lib "eagle-import") (part "M01PTH_WITHOUT_TEXT"))
    )
    (comp (ref "JP150")
      (value "M01PTH_WITHOUT_TEXT")
      (footprint "eagle-import:1X01_WITHOUT_TEXT")
      (libsource (lib "eagle-import") (part "M01PTH_WITHOUT_TEXT"))
    )
    (comp (ref "JP151")
      (value "M01PTH_WITHOUT_TEXT")
      (footprint "eagle-import:1X01_WITHOUT_TEXT")
      (libsource (lib "eagle-import") (part "M01PTH_WITHOUT_TEXT"))
    )
    (comp (ref "JP152")
      (value "M01PTH_WITHOUT_TEXT")
      (footprint "eagle-import:1X01_WITHOUT_TEXT")
      (libsource (lib "eagle-import") (part "M01PTH_WITHOUT_TEXT"))
    )
    (comp (ref "JP153")
      (value "M01PTH_WITHOUT_TEXT")
      (footprint "eagle-import:1X01_WITHOUT_TEXT")
      (libsource (lib "eagle-import") (part "M01PTH_WITHOUT_TEXT"))
    )
    (comp (ref "JP154")
      (value "M01PTH_WITHOUT_TEXT")
      (footprint "eagle-import:1X01_WITHOUT_TEXT")
      (libsource (lib "eagle-import") (part "M01PTH_WITHOUT_TEXT"))
    )
    (comp (ref "JP155")
      (value "M01PTH_WITHOUT_TEXT")
      (footprint "eagle-import:1X01_WITHOUT_TEXT")
      (libsource (lib "eagle-import") (part "M01PTH_WITHOUT_TEXT"))
    )
    (comp (ref "JP156")
      (value "M01PTH_WITHOUT_TEXT")
      (footprint "eagle-import:1X01_WITHOUT_TEXT")
      (libsource (lib "eagle-import") (part "M01PTH_WITHOUT_TEXT"))
    )
    (comp (ref "JP157")
      (value "M01PTH_WITHOUT_TEXT")
      (footprint "eagle-import:1X01_WITHOUT_TEXT")
      (libsource (lib "eagle-import") (part "M01PTH_WITHOUT_TEXT"))
    )
    (comp (ref "JP158")
      (value "M01PTH_WITHOUT_TEXT")
      (footprint "eagle-import:1X01_WITHOUT_TEXT")
      (libsource (lib "eagle-import") (part "M01PTH_WITHOUT_TEXT"))
    )
    (comp (ref "JP159")
      (value "M01PTH_WITHOUT_TEXT")
      (footprint "eagle-import:1X01_WITHOUT_TEXT")
      (libsource (lib "eagle-import") (part "M01PTH_WITHOUT_TEXT"))
    )
    (comp (ref "JP160")
      (value "M01PTH_WITHOUT_TEXT")
      (footprint "eagle-import:1X01_WITHOUT_TEXT")
      (libsource (lib "eagle-import") (part "M01PTH_WITHOUT_TEXT"))
    )
    (comp (ref "JP161")
      (value "M01PTH_WITHOUT_TEXT")
      (footprint "eagle-import:1X01_WITHOUT_TEXT")
      (libsource (lib "eagle-import") (part "M01PTH_WITHOUT_TEXT"))
    )
    (comp (ref "JP162")
      (value "M01PTH_WITHOUT_TEXT")
      (footprint "eagle-import:1X01_WITHOUT_TEXT")
      (libsource (lib "eagle-import") (part "M01PTH_WITHOUT_TEXT"))
    )
    (comp (ref "JP163")
      (value "M01PTH_WITHOUT_TEXT")
      (footprint "eagle-import:1X01_WITHOUT_TEXT")
      (libsource (lib "eagle-import") (part "M01PTH_WITHOUT_TEXT"))
    )
    (comp (ref "JP164")
      (value "M01PTH_WITHOUT_TEXT")
      (footprint "eagle-import:1X01_WITHOUT_TEXT")
      (libsource (lib "eagle-import") (part "M01PTH_WITHOUT_TEXT"))
    )
    (comp (ref "JP165")
      (value "M01PTH_WITHOUT_TEXT")
      (footprint "eagle-import:1X01_WITHOUT_TEXT")
      (libsource (lib "eagle-import") (part "M01PTH_WITHOUT_TEXT"))
    )
    (comp (ref "JP166")
      (value "M01PTH_WITHOUT_TEXT")
      (footprint "eagle-import:1X01_WITHOUT_TEXT")
      (libsource (lib "eagle-import") (part "M01PTH_WITHOUT_TEXT"))
    )
    (comp (ref "JP167")
      (value "M01PTH_WITHOUT_TEXT")
      (footprint "eagle-import:1X01_WITHOUT_TEXT")
      (libsource (lib "eagle-import") (part "M01PTH_WITHOUT_TEXT"))
    )
    (comp (ref "JP168")
      (value "M01PTH_WITHOUT_TEXT")
      (footprint "eagle-import:1X01_WITHOUT_TEXT")
      (libsource (lib "eagle-import") (part "M01PTH_WITHOUT_TEXT"))
    )
    (comp (ref "JP169")
      (value "M01PTH_WITHOUT_TEXT")
      (footprint "eagle-import:1X01_WITHOUT_TEXT")
      (libsource (lib "eagle-import") (part "M01PTH_WITHOUT_TEXT"))
    )
    (comp (ref "JP170")
      (value "M01PTH_WITHOUT_TEXT")
      (footprint "eagle-import:1X01_WITHOUT_TEXT")
      (libsource (lib "eagle-import") (part "M01PTH_WITHOUT_TEXT"))
    )
    (comp (ref "JP171")
      (value "M01PTH_WITHOUT_TEXT")
      (footprint "eagle-import:1X01_WITHOUT_TEXT")
      (libsource (lib "eagle-import") (part "M01PTH_WITHOUT_TEXT"))
    )
    (comp (ref "JP172")
      (value "M01PTH_WITHOUT_TEXT")
      (footprint "eagle-import:1X01_WITHOUT_TEXT")
      (libsource (lib "eagle-import") (part "M01PTH_WITHOUT_TEXT"))
    )
    (comp (ref "JP173")
      (value "M01PTH_WITHOUT_TEXT")
      (footprint "eagle-import:1X01_WITHOUT_TEXT")
      (libsource (lib "eagle-import") (part "M01PTH_WITHOUT_TEXT"))
    )
    (comp (ref "JP174")
      (value "M01PTH_WITHOUT_TEXT")
      (footprint "eagle-import:1X01_WITHOUT_TEXT")
      (libsource (lib "eagle-import") (part "M01PTH_WITHOUT_TEXT"))
    )
    (comp (ref "JP175")
      (value "M01PTH_WITHOUT_TEXT")
      (footprint "eagle-import:1X01_WITHOUT_TEXT")
      (libsource (lib "eagle-import") (part "M01PTH_WITHOUT_TEXT"))
    )
    (comp (ref "JP176")
      (value "M01PTH_WITHOUT_TEXT")
      (footprint "eagle-import:1X01_WITHOUT_TEXT")
      (libsource (lib "eagle-import") (part "M01PTH_WITHOUT_TEXT"))
    )
    (comp (ref "JP177")
      (value "M01PTH_WITHOUT_TEXT")
      (footprint "eagle-import:1X01_WITHOUT_TEXT")
      (libsource (lib "eagle-import") (part "M01PTH_WITHOUT_TEXT"))
    )
    (comp (ref "JP178")
      (value "M01PTH_WITHOUT_TEXT")
      (footprint "eagle-import:1X01_WITHOUT_TEXT")
      (libsource (lib "eagle-import") (part "M01PTH_WITHOUT_TEXT"))
    )
    (comp (ref "JP179")
      (value "M01PTH_WITHOUT_TEXT")
      (footprint "eagle-import:1X01_WITHOUT_TEXT")
      (libsource (lib "eagle-import") (part "M01PTH_WITHOUT_TEXT"))
    )
    (comp (ref "JP180")
      (value "M01PTH_WITHOUT_TEXT")
      (footprint "eagle-import:1X01_WITHOUT_TEXT")
      (libsource (lib "eagle-import") (part "M01PTH_WITHOUT_TEXT"))
    )
    (comp (ref "JP181")
      (value "M01PTH_WITHOUT_TEXT")
      (footprint "eagle-import:1X01_WITHOUT_TEXT")
      (libsource (lib "eagle-import") (part "M01PTH_WITHOUT_TEXT"))
    )
    (comp (ref "JP182")
      (value "M01PTH_WITHOUT_TEXT")
      (footprint "eagle-import:1X01_WITHOUT_TEXT")
      (libsource (lib "eagle-import") (part "M01PTH_WITHOUT_TEXT"))
    )
    (comp (ref "JP183")
      (value "M01PTH_WITHOUT_TEXT")
      (footprint "eagle-import:1X01_WITHOUT_TEXT")
      (libsource (lib "eagle-import") (part "M01PTH_WITHOUT_TEXT"))
    )
    (comp (ref "JP184")
      (value "M01PTH_WITHOUT_TEXT")
      (footprint "eagle-import:1X01_WITHOUT_TEXT")
      (libsource (lib "eagle-import") (part "M01PTH_WITHOUT_TEXT"))
    )
    (comp (ref "JP185")
      (value "M01PTH_WITHOUT_TEXT")
      (footprint "eagle-import:1X01_WITHOUT_TEXT")
      (libsource (lib "eagle-import") (part "M01PTH_WITHOUT_TEXT"))
    )
    (comp (ref "JP186")
      (value "M01PTH_WITHOUT_TEXT")
      (footprint "eagle-import:1X01_WITHOUT_TEXT")
      (libsource (lib "eagle-import") (part "M01PTH_WITHOUT_TEXT"))
    )
    (comp (ref "JP187")
      (value "M01PTH_WITHOUT_TEXT")
      (footprint "eagle-import:1X01_WITHOUT_TEXT")
      (libsource (lib "eagle-import") (part "M01PTH_WITHOUT_TEXT"))
    )
    (comp (ref "JP188")
      (value "M01PTH_WITHOUT_TEXT")
      (footprint "eagle-import:1X01_WITHOUT_TEXT")
      (libsource (lib "eagle-import") (part "M01PTH_WITHOUT_TEXT"))
    )
    (comp (ref "JP189")
      (value "M01PTH_WITHOUT_TEXT")
      (footprint "eagle-import:1X01_WITHOUT_TEXT")
      (libsource (lib "eagle-import") (part "M01PTH_WITHOUT_TEXT"))
    )
    (comp (ref "JP190")
      (value "M01PTH_WITHOUT_TEXT")
      (footprint "eagle-import:1X01_WITHOUT_TEXT")
      (libsource (lib "eagle-import") (part "M01PTH_WITHOUT_TEXT"))
    )
    (comp (ref "JP191")
      (value "M01PTH_WITHOUT_TEXT")
      (footprint "eagle-import:1X01_WITHOUT_TEXT")
      (libsource (lib "eagle-import") (part "M01PTH_WITHOUT_TEXT"))
    )
    (comp (ref "JP192")
      (value "M01PTH_WITHOUT_TEXT")
      (footprint "eagle-import:1X01_WITHOUT_TEXT")
      (libsource (lib "eagle-import") (part "M01PTH_WITHOUT_TEXT"))
    )
    (comp (ref "JP193")
      (value "M01PTH_WITHOUT_TEXT")
      (footprint "eagle-import:1X01_WITHOUT_TEXT")
      (libsource (lib "eagle-import") (part "M01PTH_WITHOUT_TEXT"))
    )
    (comp (ref "JP194")
      (value "M01PTH_WITHOUT_TEXT")
      (footprint "eagle-import:1X01_WITHOUT_TEXT")
      (libsource (lib "eagle-import") (part "M01PTH_WITHOUT_TEXT"))
    )
    (comp (ref "JP195")
      (value "M01PTH_WITHOUT_TEXT")
      (footprint "eagle-import:1X01_WITHOUT_TEXT")
      (libsource (lib "eagle-import") (part "M01PTH_WITHOUT_TEXT"))
    )
    (comp (ref "JP196")
      (value "M01PTH_WITHOUT_TEXT")
      (footprint "eagle-import:1X01_WITHOUT_TEXT")
      (libsource (lib "eagle-import") (part "M01PTH_WITHOUT_TEXT"))
    )
    (comp (ref "JP197")
      (value "M01PTH_WITHOUT_TEXT")
      (footprint "eagle-import:1X01_WITHOUT_TEXT")
      (libsource (lib "eagle-import") (part "M01PTH_WITHOUT_TEXT"))
    )
    (comp (ref "JP198")
      (value "M01PTH_WITHOUT_TEXT")
      (footprint "eagle-import:1X01_WITHOUT_TEXT")
      (libsource (lib "eagle-import") (part "M01PTH_WITHOUT_TEXT"))
    )
    (comp (ref "JP199")
      (value "M01PTH_WITHOUT_TEXT")
      (footprint "eagle-import:1X01_WITHOUT_TEXT")
      (libsource (lib "eagle-import") (part "M01PTH_WITHOUT_TEXT"))
    )
    (comp (ref "JP200")
      (value "M01PTH_WITHOUT_TEXT")
      (footprint "eagle-import:1X01_WITHOUT_TEXT")
      (libsource (lib "eagle-import") (part "M01PTH_WITHOUT_TEXT"))
    )
    (comp (ref "JP201")
      (value "M01PTH_WITHOUT_TEXT")
      (footprint "eagle-import:1X01_WITHOUT_TEXT")
      (libsource (lib "eagle-import") (part "M01PTH_WITHOUT_TEXT"))
    )
    (comp (ref "JP202")
      (value "M01PTH_WITHOUT_TEXT")
      (footprint "eagle-import:1X01_WITHOUT_TEXT")
      (libsource (lib "eagle-import") (part "M01PTH_WITHOUT_TEXT"))
    )
    (comp (ref "JP203")
      (value "M01PTH_WITHOUT_TEXT")
      (footprint "eagle-import:1X01_WITHOUT_TEXT")
      (libsource (lib "eagle-import") (part "M01PTH_WITHOUT_TEXT"))
    )
    (comp (ref "JP204")
      (value "M01PTH_WITHOUT_TEXT")
      (footprint "eagle-import:1X01_WITHOUT_TEXT")
      (libsource (lib "eagle-import") (part "M01PTH_WITHOUT_TEXT"))
    )
    (comp (ref "JP205")
      (value "M01PTH_WITHOUT_TEXT")
      (footprint "eagle-import:1X01_WITHOUT_TEXT")
      (libsource (lib "eagle-import") (part "M01PTH_WITHOUT_TEXT"))
    )
    (comp (ref "JP206")
      (value "M01PTH_WITHOUT_TEXT")
      (footprint "eagle-import:1X01_WITHOUT_TEXT")
      (libsource (lib "eagle-import") (part "M01PTH_WITHOUT_TEXT"))
    )
    (comp (ref "JP207")
      (value "M01PTH_WITHOUT_TEXT")
      (footprint "eagle-import:1X01_WITHOUT_TEXT")
      (libsource (lib "eagle-import") (part "M01PTH_WITHOUT_TEXT"))
    )
    (comp (ref "JP208")
      (value "M01PTH_WITHOUT_TEXT")
      (footprint "eagle-import:1X01_WITHOUT_TEXT")
      (libsource (lib "eagle-import") (part "M01PTH_WITHOUT_TEXT"))
    )
    (comp (ref "JP209")
      (value "M01PTH_WITHOUT_TEXT")
      (footprint "eagle-import:1X01_WITHOUT_TEXT")
      (libsource (lib "eagle-import") (part "M01PTH_WITHOUT_TEXT"))
    )
    (comp (ref "JP210")
      (value "M01PTH_WITHOUT_TEXT")
      (footprint "eagle-import:1X01_WITHOUT_TEXT")
      (libsource (lib "eagle-import") (part "M01PTH_WITHOUT_TEXT"))
    )
    (comp (ref "JP211")
      (value "M01PTH_WITHOUT_TEXT")
      (footprint "eagle-import:1X01_WITHOUT_TEXT")
      (libsource (lib "eagle-import") (part "M01PTH_WITHOUT_TEXT"))
    )
    (comp (ref "JP212")
      (value "M01PTH_WITHOUT_TEXT")
      (footprint "eagle-import:1X01_WITHOUT_TEXT")
      (libsource (lib "eagle-import") (part "M01PTH_WITHOUT_TEXT"))
    )
    (comp (ref "JP213")
      (value "M01PTH_WITHOUT_TEXT")
      (footprint "eagle-import:1X01_WITHOUT_TEXT")
      (libsource (lib "eagle-import") (part "M01PTH_WITHOUT_TEXT"))
    )
    (comp (ref "JP214")
      (value "M01PTH_WITHOUT_TEXT")
      (footprint "eagle-import:1X01_WITHOUT_TEXT")
      (libsource (lib "eagle-import") (part "M01PTH_WITHOUT_TEXT"))
    )
    (comp (ref "JP215")
      (value "M01PTH_WITHOUT_TEXT")
      (footprint "eagle-import:1X01_WITHOUT_TEXT")
      (libsource (lib "eagle-import") (part "M01PTH_WITHOUT_TEXT"))
    )
    (comp (ref "JP216")
      (value "M01PTH_WITHOUT_TEXT")
      (footprint "eagle-import:1X01_WITHOUT_TEXT")
      (libsource (lib "eagle-import") (part "M01PTH_WITHOUT_TEXT"))
    )
    (comp (ref "JP217")
      (value "M01PTH_WITHOUT_TEXT")
      (footprint "eagle-import:1X01_WITHOUT_TEXT")
      (libsource (lib "eagle-import") (part "M01PTH_WITHOUT_TEXT"))
    )
    (comp (ref "JP218")
      (value "M01PTH_WITHOUT_TEXT")
      (footprint "eagle-import:1X01_WITHOUT_TEXT")
      (libsource (lib "eagle-import") (part "M01PTH_WITHOUT_TEXT"))
    )
    (comp (ref "JP219")
      (value "M01PTH_WITHOUT_TEXT")
      (footprint "eagle-import:1X01_WITHOUT_TEXT")
      (libsource (lib "eagle-import") (part "M01PTH_WITHOUT_TEXT"))
    )
    (comp (ref "JP220")
      (value "M01PTH_WITHOUT_TEXT")
      (footprint "eagle-import:1X01_WITHOUT_TEXT")
      (libsource (lib "eagle-import") (part "M01PTH_WITHOUT_TEXT"))
    )
    (comp (ref "JP221")
      (value "M01PTH_WITHOUT_TEXT")
      (footprint "eagle-import:1X01_WITHOUT_TEXT")
      (libsource (lib "eagle-import") (part "M01PTH_WITHOUT_TEXT"))
    )
    (comp (ref "JP222")
      (value "M01PTH_WITHOUT_TEXT")
      (footprint "eagle-import:1X01_WITHOUT_TEXT")
      (libsource (lib "eagle-import") (part "M01PTH_WITHOUT_TEXT"))
    )
    (comp (ref "JP223")
      (value "M01PTH_WITHOUT_TEXT")
      (footprint "eagle-import:1X01_WITHOUT_TEXT")
      (libsource (lib "eagle-import") (part "M01PTH_WITHOUT_TEXT"))
    )
    (comp (ref "JP224")
      (value "M01PTH_WITHOUT_TEXT")
      (footprint "eagle-import:1X01_WITHOUT_TEXT")
      (libsource (lib "eagle-import") (part "M01PTH_WITHOUT_TEXT"))
    )
    (comp (ref "JP225")
      (value "M01PTH_WITHOUT_TEXT")
      (footprint "eagle-import:1X01_WITHOUT_TEXT")
      (libsource (lib "eagle-import") (part "M01PTH_WITHOUT_TEXT"))
    )
    (comp (ref "JP226")
      (value "M01PTH_WITHOUT_TEXT")
      (footprint "eagle-import:1X01_WITHOUT_TEXT")
      (libsource (lib "eagle-import") (part "M01PTH_WITHOUT_TEXT"))
    )
    (comp (ref "JP227")
      (value "M01PTH_WITHOUT_TEXT")
      (footprint "eagle-import:1X01_WITHOUT_TEXT")
      (libsource (lib "eagle-import") (part "M01PTH_WITHOUT_TEXT"))
    )
    (comp (ref "JP228")
      (value "M01PTH_WITHOUT_TEXT")
      (footprint "eagle-import:1X01_WITHOUT_TEXT")
      (libsource (lib "eagle-import") (part "M01PTH_WITHOUT_TEXT"))
    )
    (comp (ref "JP229")
      (value "M01PTH_WITHOUT_TEXT")
      (footprint "eagle-import:1X01_WITHOUT_TEXT")
      (libsource (lib "eagle-import") (part "M01PTH_WITHOUT_TEXT"))
    )
    (comp (ref "JP230")
      (value "M01PTH_WITHOUT_TEXT")
      (footprint "eagle-import:1X01_WITHOUT_TEXT")
      (libsource (lib "eagle-import") (part "M01PTH_WITHOUT_TEXT"))
    )
    (comp (ref "JP231")
      (value "M01PTH_WITHOUT_TEXT")
      (footprint "eagle-import:1X01_WITHOUT_TEXT")
      (libsource (lib "eagle-import") (part "M01PTH_WITHOUT_TEXT"))
    )
    (comp (ref "JP232")
      (value "M01PTH_WITHOUT_TEXT")
      (footprint "eagle-import:1X01_WITHOUT_TEXT")
      (libsource (lib "eagle-import") (part "M01PTH_WITHOUT_TEXT"))
    )
    (comp (ref "JP233")
      (value "M01PTH_WITHOUT_TEXT")
      (footprint "eagle-import:1X01_WITHOUT_TEXT")
      (libsource (lib "eagle-import") (part "M01PTH_WITHOUT_TEXT"))
    )
    (comp (ref "JP234")
      (value "M01PTH_WITHOUT_TEXT")
      (footprint "eagle-import:1X01_WITHOUT_TEXT")
      (libsource (lib "eagle-import") (part "M01PTH_WITHOUT_TEXT"))
    )
    (comp (ref "JP235")
      (value "M01PTH_WITHOUT_TEXT")
      (footprint "eagle-import:1X01_WITHOUT_TEXT")
      (libsource (lib "eagle-import") (part "M01PTH_WITHOUT_TEXT"))
    )
    (comp (ref "JP236")
      (value "M01PTH_WITHOUT_TEXT")
      (footprint "eagle-import:1X01_WITHOUT_TEXT")
      (libsource (lib "eagle-import") (part "M01PTH_WITHOUT_TEXT"))
    )
    (comp (ref "JP237")
      (value "M01PTH_WITHOUT_TEXT")
      (footprint "eagle-import:1X01_WITHOUT_TEXT")
      (libsource (lib "eagle-import") (part "M01PTH_WITHOUT_TEXT"))
    )
    (comp (ref "JP238")
      (value "M01PTH_WITHOUT_TEXT")
      (footprint "eagle-import:1X01_WITHOUT_TEXT")
      (libsource (lib "eagle-import") (part "M01PTH_WITHOUT_TEXT"))
    )
    (comp (ref "JP239")
      (value "M01PTH_WITHOUT_TEXT")
      (footprint "eagle-import:1X01_WITHOUT_TEXT")
      (libsource (lib "eagle-import") (part "M01PTH_WITHOUT_TEXT"))
    )
    (comp (ref "JP240")
      (value "M01PTH_WITHOUT_TEXT")
      (footprint "eagle-import:1X01_WITHOUT_TEXT")
      (libsource (lib "eagle-import") (part "M01PTH_WITHOUT_TEXT"))
    )
    (comp (ref "JP241")
      (value "M01PTH_WITHOUT_TEXT")
      (footprint "eagle-import:1X01_WITHOUT_TEXT")
      (libsource (lib "eagle-import") (part "M01PTH_WITHOUT_TEXT"))
    )
    (comp (ref "JP242")
      (value "M01PTH_WITHOUT_TEXT")
      (footprint "eagle-import:1X01_WITHOUT_TEXT")
      (libsource (lib "eagle-import") (part "M01PTH_WITHOUT_TEXT"))
    )
    (comp (ref "JP243")
      (value "M01PTH_WITHOUT_TEXT")
      (footprint "eagle-import:1X01_WITHOUT_TEXT")
      (libsource (lib "eagle-import") (part "M01PTH_WITHOUT_TEXT"))
    )
    (comp (ref "JP244")
      (value "M01PTH_WITHOUT_TEXT")
      (footprint "eagle-import:1X01_WITHOUT_TEXT")
      (libsource (lib "eagle-import") (part "M01PTH_WITHOUT_TEXT"))
    )
    (comp (ref "JP245")
      (value "M01PTH_WITHOUT_TEXT")
      (footprint "eagle-import:1X01_WITHOUT_TEXT")
      (libsource (lib "eagle-import") (part "M01PTH_WITHOUT_TEXT"))
    )
    (comp (ref "JP246")
      (value "M01PTH_WITHOUT_TEXT")
      (footprint "eagle-import:1X01_WITHOUT_TEXT")
      (libsource (lib "eagle-import") (part "M01PTH_WITHOUT_TEXT"))
    )
    (comp (ref "JP247")
      (value "M01PTH_WITHOUT_TEXT")
      (footprint "eagle-import:1X01_WITHOUT_TEXT")
      (libsource (lib "eagle-import") (part "M01PTH_WITHOUT_TEXT"))
    )
    (comp (ref "JP248")
      (value "M01PTH_WITHOUT_TEXT")
      (footprint "eagle-import:1X01_WITHOUT_TEXT")
      (libsource (lib "eagle-import") (part "M01PTH_WITHOUT_TEXT"))
    )
    (comp (ref "JP249")
      (value "M01PTH_WITHOUT_TEXT")
      (footprint "eagle-import:1X01_WITHOUT_TEXT")
      (libsource (lib "eagle-import") (part "M01PTH_WITHOUT_TEXT"))
    )
    (comp (ref "JP250")
      (value "M01PTH_WITHOUT_TEXT")
      (footprint "eagle-import:1X01_WITHOUT_TEXT")
      (libsource (lib "eagle-import") (part "M01PTH_WITHOUT_TEXT"))
    )
    (comp (ref "JP251")
      (value "M01PTH_WITHOUT_TEXT")
      (footprint "eagle-import:1X01_WITHOUT_TEXT")
      (libsource (lib "eagle-import") (part "M01PTH_WITHOUT_TEXT"))
    )
    (comp (ref "JP252")
      (value "M01PTH_WITHOUT_TEXT")
      (footprint "eagle-import:1X01_WITHOUT_TEXT")
      (libsource (lib "eagle-import") (part "M01PTH_WITHOUT_TEXT"))
    )
    (comp (ref "JP253")
      (value "M01PTH_WITHOUT_TEXT")
      (footprint "eagle-import:1X01_WITHOUT_TEXT")
      (libsource (lib "eagle-import") (part "M01PTH_WITHOUT_TEXT"))
    )
    (comp (ref "JP254")
      (value "M01PTH_WITHOUT_TEXT")
      (footprint "eagle-import:1X01_WITHOUT_TEXT")
      (libsource (lib "eagle-import") (part "M01PTH_WITHOUT_TEXT"))
    )
    (comp (ref "JP255")
      (value "M01PTH_WITHOUT_TEXT")
      (footprint "eagle-import:1X01_WITHOUT_TEXT")
      (libsource (lib "eagle-import") (part "M01PTH_WITHOUT_TEXT"))
    )
    (comp (ref "JP256")
      (value "M01PTH_WITHOUT_TEXT")
      (footprint "eagle-import:1X01_WITHOUT_TEXT")
      (libsource (lib "eagle-import") (part "M01PTH_WITHOUT_TEXT"))
    )
    (comp (ref "JP257")
      (value "M01PTH_WITHOUT_TEXT")
      (footprint "eagle-import:1X01_WITHOUT_TEXT")
      (libsource (lib "eagle-import") (part "M01PTH_WITHOUT_TEXT"))
    )
    (comp (ref "JP258")
      (value "M01PTH_WITHOUT_TEXT")
      (footprint "eagle-import:1X01_WITHOUT_TEXT")
      (libsource (lib "eagle-import") (part "M01PTH_WITHOUT_TEXT"))
    )
    (comp (ref "JP259")
      (value "M01PTH_WITHOUT_TEXT")
      (footprint "eagle-import:1X01_WITHOUT_TEXT")
      (libsource (lib "eagle-import") (part "M01PTH_WITHOUT_TEXT"))
    )
    (comp (ref "JP260")
      (value "M01PTH_WITHOUT_TEXT")
      (footprint "eagle-import:1X01_WITHOUT_TEXT")
      (libsource (lib "eagle-import") (part "M01PTH_WITHOUT_TEXT"))
    )
    (comp (ref "JP261")
      (value "M01PTH_WITHOUT_TEXT")
      (footprint "eagle-import:1X01_WITHOUT_TEXT")
      (libsource (lib "eagle-import") (part "M01PTH_WITHOUT_TEXT"))
    )
    (comp (ref "JP262")
      (value "M01PTH_WITHOUT_TEXT")
      (footprint "eagle-import:1X01_WITHOUT_TEXT")
      (libsource (lib "eagle-import") (part "M01PTH_WITHOUT_TEXT"))
    )
    (comp (ref "JP263")
      (value "M01PTH_WITHOUT_TEXT")
      (footprint "eagle-import:1X01_WITHOUT_TEXT")
      (libsource (lib "eagle-import") (part "M01PTH_WITHOUT_TEXT"))
    )
    (comp (ref "JP264")
      (value "M01PTH_WITHOUT_TEXT")
      (footprint "eagle-import:1X01_WITHOUT_TEXT")
      (libsource (lib "eagle-import") (part "M01PTH_WITHOUT_TEXT"))
    )
    (comp (ref "JP265")
      (value "M01PTH_WITHOUT_TEXT")
      (footprint "eagle-import:1X01_WITHOUT_TEXT")
      (libsource (lib "eagle-import") (part "M01PTH_WITHOUT_TEXT"))
    )
    (comp (ref "JP266")
      (value "M01PTH_WITHOUT_TEXT")
      (footprint "eagle-import:1X01_WITHOUT_TEXT")
      (libsource (lib "eagle-import") (part "M01PTH_WITHOUT_TEXT"))
    )
    (comp (ref "JP267")
      (value "M01PTH_WITHOUT_TEXT")
      (footprint "eagle-import:1X01_WITHOUT_TEXT")
      (libsource (lib "eagle-import") (part "M01PTH_WITHOUT_TEXT"))
    )
    (comp (ref "JP268")
      (value "M01PTH_WITHOUT_TEXT")
      (footprint "eagle-import:1X01_WITHOUT_TEXT")
      (libsource (lib "eagle-import") (part "M01PTH_WITHOUT_TEXT"))
    )
    (comp (ref "JP269")
      (value "M01PTH_WITHOUT_TEXT")
      (footprint "eagle-import:1X01_WITHOUT_TEXT")
      (libsource (lib "eagle-import") (part "M01PTH_WITHOUT_TEXT"))
    )
    (comp (ref "JP270")
      (value "M01PTH_WITHOUT_TEXT")
      (footprint "eagle-import:1X01_WITHOUT_TEXT")
      (libsource (lib "eagle-import") (part "M01PTH_WITHOUT_TEXT"))
    )
    (comp (ref "JP271")
      (value "M01PTH_WITHOUT_TEXT")
      (footprint "eagle-import:1X01_WITHOUT_TEXT")
      (libsource (lib "eagle-import") (part "M01PTH_WITHOUT_TEXT"))
    )
    (comp (ref "JP272")
      (value "M01PTH_WITHOUT_TEXT")
      (footprint "eagle-import:1X01_WITHOUT_TEXT")
      (libsource (lib "eagle-import") (part "M01PTH_WITHOUT_TEXT"))
    )
    (comp (ref "JP273")
      (value "M01PTH_WITHOUT_TEXT")
      (footprint "eagle-import:1X01_WITHOUT_TEXT")
      (libsource (lib "eagle-import") (part "M01PTH_WITHOUT_TEXT"))
    )
    (comp (ref "JP274")
      (value "M01PTH_WITHOUT_TEXT")
      (footprint "eagle-import:1X01_WITHOUT_TEXT")
      (libsource (lib "eagle-import") (part "M01PTH_WITHOUT_TEXT"))
    )
    (comp (ref "JP275")
      (value "M01PTH_WITHOUT_TEXT")
      (footprint "eagle-import:1X01_WITHOUT_TEXT")
      (libsource (lib "eagle-import") (part "M01PTH_WITHOUT_TEXT"))
    )
    (comp (ref "JP276")
      (value "M01PTH_WITHOUT_TEXT")
      (footprint "eagle-import:1X01_WITHOUT_TEXT")
      (libsource (lib "eagle-import") (part "M01PTH_WITHOUT_TEXT"))
    )
    (comp (ref "JP277")
      (value "M01PTH_WITHOUT_TEXT")
      (footprint "eagle-import:1X01_WITHOUT_TEXT")
      (libsource (lib "eagle-import") (part "M01PTH_WITHOUT_TEXT"))
    )
    (comp (ref "JP278")
      (value "M01PTH_WITHOUT_TEXT")
      (footprint "eagle-import:1X01_WITHOUT_TEXT")
      (libsource (lib "eagle-import") (part "M01PTH_WITHOUT_TEXT"))
    )
    (comp (ref "JP279")
      (value "M01PTH_WITHOUT_TEXT")
      (footprint "eagle-import:1X01_WITHOUT_TEXT")
      (libsource (lib "eagle-import") (part "M01PTH_WITHOUT_TEXT"))
    )
    (comp (ref "JP280")
      (value "M01PTH_WITHOUT_TEXT")
      (footprint "eagle-import:1X01_WITHOUT_TEXT")
      (libsource (lib "eagle-import") (part "M01PTH_WITHOUT_TEXT"))
    )
    (comp (ref "JP281")
      (value "M01PTH_WITHOUT_TEXT")
      (footprint "eagle-import:1X01_WITHOUT_TEXT")
      (libsource (lib "eagle-import") (part "M01PTH_WITHOUT_TEXT"))
    )
    (comp (ref "JP282")
      (value "M01PTH_WITHOUT_TEXT")
      (footprint "eagle-import:1X01_WITHOUT_TEXT")
      (libsource (lib "eagle-import") (part "M01PTH_WITHOUT_TEXT"))
    )
    (comp (ref "JP283")
      (value "M01PTH_WITHOUT_TEXT")
      (footprint "eagle-import:1X01_WITHOUT_TEXT")
      (libsource (lib "eagle-import") (part "M01PTH_WITHOUT_TEXT"))
    )
    (comp (ref "JP284")
      (value "M01PTH_WITHOUT_TEXT")
      (footprint "eagle-import:1X01_WITHOUT_TEXT")
      (libsource (lib "eagle-import") (part "M01PTH_WITHOUT_TEXT"))
    )
    (comp (ref "JP285")
      (value "M01PTH_WITHOUT_TEXT")
      (footprint "eagle-import:1X01_WITHOUT_TEXT")
      (libsource (lib "eagle-import") (part "M01PTH_WITHOUT_TEXT"))
    )
    (comp (ref "JP286")
      (value "M01PTH_WITHOUT_TEXT")
      (footprint "eagle-import:1X01_WITHOUT_TEXT")
      (libsource (lib "eagle-import") (part "M01PTH_WITHOUT_TEXT"))
    )
    (comp (ref "JP287")
      (value "M01PTH_WITHOUT_TEXT")
      (footprint "eagle-import:1X01_WITHOUT_TEXT")
      (libsource (lib "eagle-import") (part "M01PTH_WITHOUT_TEXT"))
    )
    (comp (ref "JP288")
      (value "M01PTH_WITHOUT_TEXT")
      (footprint "eagle-import:1X01_WITHOUT_TEXT")
      (libsource (lib "eagle-import") (part "M01PTH_WITHOUT_TEXT"))
    )
    (comp (ref "JP289")
      (value "M01PTH_WITHOUT_TEXT")
      (footprint "eagle-import:1X01_WITHOUT_TEXT")
      (libsource (lib "eagle-import") (part "M01PTH_WITHOUT_TEXT"))
    )
    (comp (ref "JP290")
      (value "M01PTH_WITHOUT_TEXT")
      (footprint "eagle-import:1X01_WITHOUT_TEXT")
      (libsource (lib "eagle-import") (part "M01PTH_WITHOUT_TEXT"))
    )
    (comp (ref "JP291")
      (value "M01PTH_WITHOUT_TEXT")
      (footprint "eagle-import:1X01_WITHOUT_TEXT")
      (libsource (lib "eagle-import") (part "M01PTH_WITHOUT_TEXT"))
    )
    (comp (ref "JP292")
      (value "M01PTH_WITHOUT_TEXT")
      (footprint "eagle-import:1X01_WITHOUT_TEXT")
      (libsource (lib "eagle-import") (part "M01PTH_WITHOUT_TEXT"))
    )
    (comp (ref "JP293")
      (value "M01PTH_WITHOUT_TEXT")
      (footprint "eagle-import:1X01_WITHOUT_TEXT")
      (libsource (lib "eagle-import") (part "M01PTH_WITHOUT_TEXT"))
    )
    (comp (ref "JP294")
      (value "M01PTH_WITHOUT_TEXT")
      (footprint "eagle-import:1X01_WITHOUT_TEXT")
      (libsource (lib "eagle-import") (part "M01PTH_WITHOUT_TEXT"))
    )
    (comp (ref "JP295")
      (value "M01PTH_WITHOUT_TEXT")
      (footprint "eagle-import:1X01_WITHOUT_TEXT")
      (libsource (lib "eagle-import") (part "M01PTH_WITHOUT_TEXT"))
    )
    (comp (ref "JP296")
      (value "M01PTH_WITHOUT_TEXT")
      (footprint "eagle-import:1X01_WITHOUT_TEXT")
      (libsource (lib "eagle-import") (part "M01PTH_WITHOUT_TEXT"))
    )
    (comp (ref "JP297")
      (value "M01PTH_WITHOUT_TEXT")
      (footprint "eagle-import:1X01_WITHOUT_TEXT")
      (libsource (lib "eagle-import") (part "M01PTH_WITHOUT_TEXT"))
    )
    (comp (ref "JP298")
      (value "M01PTH_WITHOUT_TEXT")
      (footprint "eagle-import:1X01_WITHOUT_TEXT")
      (libsource (lib "eagle-import") (part "M01PTH_WITHOUT_TEXT"))
    )
    (comp (ref "JP299")
      (value "M01PTH_WITHOUT_TEXT")
      (footprint "eagle-import:1X01_WITHOUT_TEXT")
      (libsource (lib "eagle-import") (part "M01PTH_WITHOUT_TEXT"))
    )
    (comp (ref "JP300")
      (value "M01PTH_WITHOUT_TEXT")
      (footprint "eagle-import:1X01_WITHOUT_TEXT")
      (libsource (lib "eagle-import") (part "M01PTH_WITHOUT_TEXT"))
    )
    (comp (ref "JP901")
      (value "M01PTH_SMD_3.25X0.85MM_NO_SILK")
      (footprint "eagle-import:1X01_SMD_3.25X0.85MM_NO_SILK")
      (libsource (lib "eagle-import") (part "M01PTH_SMD_3.25X0.85MM_NO_SILK"))
    )
    (comp (ref "JP902")
      (value "M01PTH_SMD_3.25X0.85MM_NO_SILK")
      (footprint "eagle-import:1X01_SMD_3.25X0.85MM_NO_SILK")
      (libsource (lib "eagle-import") (part "M01PTH_SMD_3.25X0.85MM_NO_SILK"))
    )
    (comp (ref "JP903")
      (value "M01PTH_SMD_3.25X0.85MM_NO_SILK")
      (footprint "eagle-import:1X01_SMD_3.25X0.85MM_NO_SILK")
      (libsource (lib "eagle-import") (part "M01PTH_SMD_3.25X0.85MM_NO_SILK"))
    )
    (comp (ref "JP904")
      (value "M01PTH_SMD_3.25X0.85MM_NO_SILK")
      (footprint "eagle-import:1X01_SMD_3.25X0.85MM_NO_SILK")
      (libsource (lib "eagle-import") (part "M01PTH_SMD_3.25X0.85MM_NO_SILK"))
    )
    (comp (ref "JP905")
      (value "M01PTH_SMD_3.25X0.85MM_NO_SILK")
      (footprint "eagle-import:1X01_SMD_3.25X0.85MM_NO_SILK")
      (libsource (lib "eagle-import") (part "M01PTH_SMD_3.25X0.85MM_NO_SILK"))
    )
    (comp (ref "JP906")
      (value "M01PTH_SMD_3.25X0.85MM_NO_SILK")
      (footprint "eagle-import:1X01_SMD_3.25X0.85MM_NO_SILK")
      (libsource (lib "eagle-import") (part "M01PTH_SMD_3.25X0.85MM_NO_SILK"))
    )
    (comp (ref "JP907")
      (value "M01PTH_SMD_3.25X0.85MM_NO_SILK")
      (footprint "eagle-import:1X01_SMD_3.25X0.85MM_NO_SILK")
      (libsource (lib "eagle-import") (part "M01PTH_SMD_3.25X0.85MM_NO_SILK"))
    )
    (comp (ref "JP908")
      (value "M01PTH_SMD_3.25X0.85MM_NO_SILK")
      (footprint "eagle-import:1X01_SMD_3.25X0.85MM_NO_SILK")
      (libsource (lib "eagle-import") (part "M01PTH_SMD_3.25X0.85MM_NO_SILK"))
    )
    (comp (ref "JP909")
      (value "M01PTH_SMD_3.25X0.85MM_NO_SILK")
      (footprint "eagle-import:1X01_SMD_3.25X0.85MM_NO_SILK")
      (libsource (lib "eagle-import") (part "M01PTH_SMD_3.25X0.85MM_NO_SILK"))
    )
    (comp (ref "JP910")
      (value "M01PTH_SMD_3.25X0.85MM_NO_SILK")
      (footprint "eagle-import:1X01_SMD_3.25X0.85MM_NO_SILK")
      (libsource (lib "eagle-import") (part "M01PTH_SMD_3.25X0.85MM_NO_SILK"))
    )
    (comp (ref "JP911")
      (value "M01PTH_SMD_3.25X0.85MM_NO_SILK")
      (footprint "eagle-import:1X01_SMD_3.25X0.85MM_NO_SILK")
      (libsource (lib "eagle-import") (part "M01PTH_SMD_3.25X0.85MM_NO_SILK"))
    )
    (comp (ref "JP912")
      (value "M01PTH_SMD_3.25X0.85MM_NO_SILK")
      (footprint "eagle-import:1X01_SMD_3.25X0.85MM_NO_SILK")
      (libsource (lib "eagle-import") (part "M01PTH_SMD_3.25X0.85MM_NO_SILK"))
    )
    (comp (ref "JP913")
      (value "M01PTH_SMD_3.25X0.85MM_NO_SILK")
      (footprint "eagle-import:1X01_SMD_3.25X0.85MM_NO_SILK")
      (libsource (lib "eagle-import") (part "M01PTH_SMD_3.25X0.85MM_NO_SILK"))
    )
    (comp (ref "JP914")
      (value "M01PTH_SMD_3.25X0.85MM_NO_SILK")
      (footprint "eagle-import:1X01_SMD_3.25X0.85MM_NO_SILK")
      (libsource (lib "eagle-import") (part "M01PTH_SMD_3.25X0.85MM_NO_SILK"))
    )
    (comp (ref "JP915")
      (value "M01PTH_SMD_3.25X0.85MM_NO_SILK")
      (footprint "eagle-import:1X01_SMD_3.25X0.85MM_NO_SILK")
      (libsource (lib "eagle-import") (part "M01PTH_SMD_3.25X0.85MM_NO_SILK"))
    )
    (comp (ref "JP916")
      (value "M01PTH_SMD_3.25X0.85MM_NO_SILK")
      (footprint "eagle-import:1X01_SMD_3.25X0.85MM_NO_SILK")
      (libsource (lib "eagle-import") (part "M01PTH_SMD_3.25X0.85MM_NO_SILK"))
    )
    (comp (ref "JP917")
      (value "M01PTH_SMD_3.25X0.85MM_NO_SILK")
      (footprint "eagle-import:1X01_SMD_3.25X0.85MM_NO_SILK")
      (libsource (lib "eagle-import") (part "M01PTH_SMD_3.25X0.85MM_NO_SILK"))
    )
    (comp (ref "JP918")
      (value "M01PTH_SMD_3.25X0.85MM_NO_SILK")
      (footprint "eagle-import:1X01_SMD_3.25X0.85MM_NO_SILK")
      (libsource (lib "eagle-import") (part "M01PTH_SMD_3.25X0.85MM_NO_SILK"))
    )
    (comp (ref "JP919")
      (value "M01PTH_SMD_3.25X0.85MM_NO_SILK")
      (footprint "eagle-import:1X01_SMD_3.25X0.85MM_NO_SILK")
      (libsource (lib "eagle-import") (part "M01PTH_SMD_3.25X0.85MM_NO_SILK"))
    )
    (comp (ref "JP920")
      (value "M01PTH_SMD_3.25X0.85MM_NO_SILK")
      (footprint "eagle-import:1X01_SMD_3.25X0.85MM_NO_SILK")
      (libsource (lib "eagle-import") (part "M01PTH_SMD_3.25X0.85MM_NO_SILK"))
    )
    (comp (ref "JP921")
      (value "M01PTH_SMD_3.25X0.85MM_NO_SILK")
      (footprint "eagle-import:1X01_SMD_3.25X0.85MM_NO_SILK")
      (libsource (lib "eagle-import") (part "M01PTH_SMD_3.25X0.85MM_NO_SILK"))
    )
    (comp (ref "JP922")
      (value "M01PTH_SMD_3.25X0.85MM_NO_SILK")
      (footprint "eagle-import:1X01_SMD_3.25X0.85MM_NO_SILK")
      (libsource (lib "eagle-import") (part "M01PTH_SMD_3.25X0.85MM_NO_SILK"))
    )
    (comp (ref "JP923")
      (value "M01PTH_SMD_3.25X0.85MM_NO_SILK")
      (footprint "eagle-import:1X01_SMD_3.25X0.85MM_NO_SILK")
      (libsource (lib "eagle-import") (part "M01PTH_SMD_3.25X0.85MM_NO_SILK"))
    )
    (comp (ref "JP924")
      (value "M01PTH_SMD_3.25X0.85MM_NO_SILK")
      (footprint "eagle-import:1X01_SMD_3.25X0.85MM_NO_SILK")
      (libsource (lib "eagle-import") (part "M01PTH_SMD_3.25X0.85MM_NO_SILK"))
    )
    (comp (ref "JP925")
      (value "M01PTH_SMD_3.25X0.85MM_NO_SILK")
      (footprint "eagle-import:1X01_SMD_3.25X0.85MM_NO_SILK")
      (libsource (lib "eagle-import") (part "M01PTH_SMD_3.25X0.85MM_NO_SILK"))
    )
    (comp (ref "JP926")
      (value "M01PTH_SMD_3.25X0.85MM_NO_SILK")
      (footprint "eagle-import:1X01_SMD_3.25X0.85MM_NO_SILK")
      (libsource (lib "eagle-import") (part "M01PTH_SMD_3.25X0.85MM_NO_SILK"))
    )
    (comp (ref "JP927")
      (value "M01PTH_SMD_3.25X0.85MM_NO_SILK")
      (footprint "eagle-import:1X01_SMD_3.25X0.85MM_NO_SILK")
      (libsource (lib "eagle-import") (part "M01PTH_SMD_3.25X0.85MM_NO_SILK"))
    )
    (comp (ref "JP928")
      (value "M01PTH_SMD_3.25X0.85MM_NO_SILK")
      (footprint "eagle-import:1X01_SMD_3.25X0.85MM_NO_SILK")
      (libsource (lib "eagle-import") (part "M01PTH_SMD_3.25X0.85MM_NO_SILK"))
    )
    (comp (ref "JP929")
      (value "M01PTH_SMD_3.25X0.85MM_NO_SILK")
      (footprint "eagle-import:1X01_SMD_3.25X0.85MM_NO_SILK")
      (libsource (lib "eagle-import") (part "M01PTH_SMD_3.25X0.85MM_NO_SILK"))
    )
    (comp (ref "JP930")
      (value "M01PTH_SMD_3.25X0.85MM_NO_SILK")
      (footprint "eagle-import:1X01_SMD_3.25X0.85MM_NO_SILK")
      (libsource (lib "eagle-import") (part "M01PTH_SMD_3.25X0.85MM_NO_SILK"))
    )
    (comp (ref "JP931")
      (value "M01PTH_SMD_3.25X0.85MM_NO_SILK")
      (footprint "eagle-import:1X01_SMD_3.25X0.85MM_NO_SILK")
      (libsource (lib "eagle-import") (part "M01PTH_SMD_3.25X0.85MM_NO_SILK"))
    )
    (comp (ref "JP932")
      (value "M01PTH_SMD_3.25X0.85MM_NO_SILK")
      (footprint "eagle-import:1X01_SMD_3.25X0.85MM_NO_SILK")
      (libsource (lib "eagle-import") (part "M01PTH_SMD_3.25X0.85MM_NO_SILK"))
    )
    (comp (ref "JP933")
      (value "M01PTH_SMD_3.25X0.85MM_NO_SILK")
      (footprint "eagle-import:1X01_SMD_3.25X0.85MM_NO_SILK")
      (libsource (lib "eagle-import") (part "M01PTH_SMD_3.25X0.85MM_NO_SILK"))
    )
    (comp (ref "JP934")
      (value "M01PTH_SMD_3.25X0.85MM_NO_SILK")
      (footprint "eagle-import:1X01_SMD_3.25X0.85MM_NO_SILK")
      (libsource (lib "eagle-import") (part "M01PTH_SMD_3.25X0.85MM_NO_SILK"))
    )
    (comp (ref "JP935")
      (value "M01PTH_SMD_3.25X0.85MM_NO_SILK")
      (footprint "eagle-import:1X01_SMD_3.25X0.85MM_NO_SILK")
      (libsource (lib "eagle-import") (part "M01PTH_SMD_3.25X0.85MM_NO_SILK"))
    )
    (comp (ref "JP936")
      (value "M01PTH_SMD_3.25X0.85MM_NO_SILK")
      (footprint "eagle-import:1X01_SMD_3.25X0.85MM_NO_SILK")
      (libsource (lib "eagle-import") (part "M01PTH_SMD_3.25X0.85MM_NO_SILK"))
    )
    (comp (ref "JP937")
      (value "M01PTH_SMD_3.25X0.85MM_NO_SILK")
      (footprint "eagle-import:1X01_SMD_3.25X0.85MM_NO_SILK")
      (libsource (lib "eagle-import") (part "M01PTH_SMD_3.25X0.85MM_NO_SILK"))
    )
    (comp (ref "JP938")
      (value "M01PTH_SMD_3.25X0.85MM_NO_SILK")
      (footprint "eagle-import:1X01_SMD_3.25X0.85MM_NO_SILK")
      (libsource (lib "eagle-import") (part "M01PTH_SMD_3.25X0.85MM_NO_SILK"))
    )
    (comp (ref "JP939")
      (value "M01PTH_SMD_3.25X0.85MM_NO_SILK")
      (footprint "eagle-import:1X01_SMD_3.25X0.85MM_NO_SILK")
      (libsource (lib "eagle-import") (part "M01PTH_SMD_3.25X0.85MM_NO_SILK"))
    )
    (comp (ref "JP940")
      (value "M01PTH_SMD_3.25X0.85MM_NO_SILK")
      (footprint "eagle-import:1X01_SMD_3.25X0.85MM_NO_SILK")
      (libsource (lib "eagle-import") (part "M01PTH_SMD_3.25X0.85MM_NO_SILK"))
    )
    (comp (ref "JP941")
      (value "M01PTH_SMD_3.25X0.85MM_NO_SILK")
      (footprint "eagle-import:1X01_SMD_3.25X0.85MM_NO_SILK")
      (libsource (lib "eagle-import") (part "M01PTH_SMD_3.25X0.85MM_NO_SILK"))
    )
    (comp (ref "JP942")
      (value "M01PTH_SMD_3.25X0.85MM_NO_SILK")
      (footprint "eagle-import:1X01_SMD_3.25X0.85MM_NO_SILK")
      (libsource (lib "eagle-import") (part "M01PTH_SMD_3.25X0.85MM_NO_SILK"))
    )
    (comp (ref "JP943")
      (value "M01PTH_SMD_3.25X0.85MM_NO_SILK")
      (footprint "eagle-import:1X01_SMD_3.25X0.85MM_NO_SILK")
      (libsource (lib "eagle-import") (part "M01PTH_SMD_3.25X0.85MM_NO_SILK"))
    )
    (comp (ref "JP944")
      (value "M01PTH_SMD_3.25X0.85MM_NO_SILK")
      (footprint "eagle-import:1X01_SMD_3.25X0.85MM_NO_SILK")
      (libsource (lib "eagle-import") (part "M01PTH_SMD_3.25X0.85MM_NO_SILK"))
    )
    (comp (ref "JP945")
      (value "M01PTH_SMD_3.25X0.85MM_NO_SILK")
      (footprint "eagle-import:1X01_SMD_3.25X0.85MM_NO_SILK")
      (libsource (lib "eagle-import") (part "M01PTH_SMD_3.25X0.85MM_NO_SILK"))
    )
    (comp (ref "JP946")
      (value "M01PTH_SMD_3.25X0.85MM_NO_SILK")
      (footprint "eagle-import:1X01_SMD_3.25X0.85MM_NO_SILK")
      (libsource (lib "eagle-import") (part "M01PTH_SMD_3.25X0.85MM_NO_SILK"))
    )
    (comp (ref "JP947")
      (value "M01PTH_SMD_3.25X0.85MM_NO_SILK")
      (footprint "eagle-import:1X01_SMD_3.25X0.85MM_NO_SILK")
      (libsource (lib "eagle-import") (part "M01PTH_SMD_3.25X0.85MM_NO_SILK"))
    )
    (comp (ref "JP948")
      (value "M01PTH_SMD_3.25X0.85MM_NO_SILK")
      (footprint "eagle-import:1X01_SMD_3.25X0.85MM_NO_SILK")
      (libsource (lib "eagle-import") (part "M01PTH_SMD_3.25X0.85MM_NO_SILK"))
    )
    (comp (ref "JP949")
      (value "M01PTH_SMD_3.25X0.85MM_NO_SILK")
      (footprint "eagle-import:1X01_SMD_3.25X0.85MM_NO_SILK")
      (libsource (lib "eagle-import") (part "M01PTH_SMD_3.25X0.85MM_NO_SILK"))
    )
    (comp (ref "JP950")
      (value "M01PTH_SMD_3.25X0.85MM_NO_SILK")
      (footprint "eagle-import:1X01_SMD_3.25X0.85MM_NO_SILK")
      (libsource (lib "eagle-import") (part "M01PTH_SMD_3.25X0.85MM_NO_SILK"))
    )
    (comp (ref "JP951")
      (value "M01PTH_SMD_3.25X0.85MM_NO_SILK")
      (footprint "eagle-import:1X01_SMD_3.25X0.85MM_NO_SILK")
      (libsource (lib "eagle-import") (part "M01PTH_SMD_3.25X0.85MM_NO_SILK"))
    )
    (comp (ref "JP952")
      (value "M01PTH_SMD_3.25X0.85MM_NO_SILK")
      (footprint "eagle-import:1X01_SMD_3.25X0.85MM_NO_SILK")
      (libsource (lib "eagle-import") (part "M01PTH_SMD_3.25X0.85MM_NO_SILK"))
    )
    (comp (ref "JP953")
      (value "M01PTH_SMD_3.25X0.85MM_NO_SILK")
      (footprint "eagle-import:1X01_SMD_3.25X0.85MM_NO_SILK")
      (libsource (lib "eagle-import") (part "M01PTH_SMD_3.25X0.85MM_NO_SILK"))
    )
    (comp (ref "JP954")
      (value "M01PTH_SMD_3.25X0.85MM_NO_SILK")
      (footprint "eagle-import:1X01_SMD_3.25X0.85MM_NO_SILK")
      (libsource (lib "eagle-import") (part "M01PTH_SMD_3.25X0.85MM_NO_SILK"))
    )
    (comp (ref "JP955")
      (value "M01PTH_SMD_3.25X0.85MM_NO_SILK")
      (footprint "eagle-import:1X01_SMD_3.25X0.85MM_NO_SILK")
      (libsource (lib "eagle-import") (part "M01PTH_SMD_3.25X0.85MM_NO_SILK"))
    )
    (comp (ref "JP956")
      (value "M01PTH_SMD_3.25X0.85MM_NO_SILK")
      (footprint "eagle-import:1X01_SMD_3.25X0.85MM_NO_SILK")
      (libsource (lib "eagle-import") (part "M01PTH_SMD_3.25X0.85MM_NO_SILK"))
    )
    (comp (ref "JP957")
      (value "M01PTH_SMD_3.25X0.85MM_NO_SILK")
      (footprint "eagle-import:1X01_SMD_3.25X0.85MM_NO_SILK")
      (libsource (lib "eagle-import") (part "M01PTH_SMD_3.25X0.85MM_NO_SILK"))
    )
    (comp (ref "JP958")
      (value "M01PTH_SMD_3.25X0.85MM_NO_SILK")
      (footprint "eagle-import:1X01_SMD_3.25X0.85MM_NO_SILK")
      (libsource (lib "eagle-import") (part "M01PTH_SMD_3.25X0.85MM_NO_SILK"))
    )
    (comp (ref "JP959")
      (value "M01PTH_SMD_3.25X0.85MM_NO_SILK")
      (footprint "eagle-import:1X01_SMD_3.25X0.85MM_NO_SILK")
      (libsource (lib "eagle-import") (part "M01PTH_SMD_3.25X0.85MM_NO_SILK"))
    )
    (comp (ref "JP960")
      (value "M01PTH_SMD_3.25X0.85MM_NO_SILK")
      (footprint "eagle-import:1X01_SMD_3.25X0.85MM_NO_SILK")
      (libsource (lib "eagle-import") (part "M01PTH_SMD_3.25X0.85MM_NO_SILK"))
    )
    (comp (ref "JP961")
      (value "M01PTH_SMD_3.25X0.85MM_NO_SILK")
      (footprint "eagle-import:1X01_SMD_3.25X0.85MM_NO_SILK")
      (libsource (lib "eagle-import") (part "M01PTH_SMD_3.25X0.85MM_NO_SILK"))
    )
    (comp (ref "JP962")
      (value "M01PTH_SMD_3.25X0.85MM_NO_SILK")
      (footprint "eagle-import:1X01_SMD_3.25X0.85MM_NO_SILK")
      (libsource (lib "eagle-import") (part "M01PTH_SMD_3.25X0.85MM_NO_SILK"))
    )
    (comp (ref "JP963")
      (value "M01PTH_SMD_3.25X0.85MM_NO_SILK")
      (footprint "eagle-import:1X01_SMD_3.25X0.85MM_NO_SILK")
      (libsource (lib "eagle-import") (part "M01PTH_SMD_3.25X0.85MM_NO_SILK"))
    )
    (comp (ref "JP964")
      (value "M01PTH_SMD_3.25X0.85MM_NO_SILK")
      (footprint "eagle-import:1X01_SMD_3.25X0.85MM_NO_SILK")
      (libsource (lib "eagle-import") (part "M01PTH_SMD_3.25X0.85MM_NO_SILK"))
    )
    (comp (ref "JP965")
      (value "M01PTH_SMD_3.25X0.85MM_NO_SILK")
      (footprint "eagle-import:1X01_SMD_3.25X0.85MM_NO_SILK")
      (libsource (lib "eagle-import") (part "M01PTH_SMD_3.25X0.85MM_NO_SILK"))
    )
    (comp (ref "JP966")
      (value "M01PTH_SMD_3.25X0.85MM_NO_SILK")
      (footprint "eagle-import:1X01_SMD_3.25X0.85MM_NO_SILK")
      (libsource (lib "eagle-import") (part "M01PTH_SMD_3.25X0.85MM_NO_SILK"))
    )
    (comp (ref "JP967")
      (value "M01PTH_SMD_3.25X0.85MM_NO_SILK")
      (footprint "eagle-import:1X01_SMD_3.25X0.85MM_NO_SILK")
      (libsource (lib "eagle-import") (part "M01PTH_SMD_3.25X0.85MM_NO_SILK"))
    )
    (comp (ref "JP968")
      (value "M01PTH_SMD_3.25X0.85MM_NO_SILK")
      (footprint "eagle-import:1X01_SMD_3.25X0.85MM_NO_SILK")
      (libsource (lib "eagle-import") (part "M01PTH_SMD_3.25X0.85MM_NO_SILK"))
    )
    (comp (ref "JP969")
      (value "M01PTH_SMD_3.25X0.85MM_NO_SILK")
      (footprint "eagle-import:1X01_SMD_3.25X0.85MM_NO_SILK")
      (libsource (lib "eagle-import") (part "M01PTH_SMD_3.25X0.85MM_NO_SILK"))
    )
    (comp (ref "JP970")
      (value "M01PTH_SMD_3.25X0.85MM_NO_SILK")
      (footprint "eagle-import:1X01_SMD_3.25X0.85MM_NO_SILK")
      (libsource (lib "eagle-import") (part "M01PTH_SMD_3.25X0.85MM_NO_SILK"))
    )
    (comp (ref "JP971")
      (value "M01PTH_SMD_3.25X0.85MM_NO_SILK")
      (footprint "eagle-import:1X01_SMD_3.25X0.85MM_NO_SILK")
      (libsource (lib "eagle-import") (part "M01PTH_SMD_3.25X0.85MM_NO_SILK"))
    )
    (comp (ref "JP972")
      (value "M01PTH_SMD_3.25X0.85MM_NO_SILK")
      (footprint "eagle-import:1X01_SMD_3.25X0.85MM_NO_SILK")
      (libsource (lib "eagle-import") (part "M01PTH_SMD_3.25X0.85MM_NO_SILK"))
    )
    (comp (ref "JP973")
      (value "M01PTH_SMD_3.25X0.85MM_NO_SILK")
      (footprint "eagle-import:1X01_SMD_3.25X0.85MM_NO_SILK")
      (libsource (lib "eagle-import") (part "M01PTH_SMD_3.25X0.85MM_NO_SILK"))
    )
    (comp (ref "JP974")
      (value "M01PTH_SMD_3.25X0.85MM_NO_SILK")
      (footprint "eagle-import:1X01_SMD_3.25X0.85MM_NO_SILK")
      (libsource (lib "eagle-import") (part "M01PTH_SMD_3.25X0.85MM_NO_SILK"))
    )
    (comp (ref "JP975")
      (value "M01PTH_SMD_3.25X0.85MM_NO_SILK")
      (footprint "eagle-import:1X01_SMD_3.25X0.85MM_NO_SILK")
      (libsource (lib "eagle-import") (part "M01PTH_SMD_3.25X0.85MM_NO_SILK"))
    )
    (comp (ref "JP976")
      (value "M01PTH_SMD_3.25X0.85MM_NO_SILK")
      (footprint "eagle-import:1X01_SMD_3.25X0.85MM_NO_SILK")
      (libsource (lib "eagle-import") (part "M01PTH_SMD_3.25X0.85MM_NO_SILK"))
    )
    (comp (ref "JP977")
      (value "M01PTH_SMD_3.25X0.85MM_NO_SILK")
      (footprint "eagle-import:1X01_SMD_3.25X0.85MM_NO_SILK")
      (libsource (lib "eagle-import") (part "M01PTH_SMD_3.25X0.85MM_NO_SILK"))
    )
    (comp (ref "JP978")
      (value "M01PTH_SMD_3.25X0.85MM_NO_SILK")
      (footprint "eagle-import:1X01_SMD_3.25X0.85MM_NO_SILK")
      (libsource (lib "eagle-import") (part "M01PTH_SMD_3.25X0.85MM_NO_SILK"))
    )
    (comp (ref "JP979")
      (value "M01PTH_SMD_3.25X0.85MM_NO_SILK")
      (footprint "eagle-import:1X01_SMD_3.25X0.85MM_NO_SILK")
      (libsource (lib "eagle-import") (part "M01PTH_SMD_3.25X0.85MM_NO_SILK"))
    )
    (comp (ref "JP980")
      (value "M01PTH_SMD_3.25X0.85MM_NO_SILK")
      (footprint "eagle-import:1X01_SMD_3.25X0.85MM_NO_SILK")
      (libsource (lib "eagle-import") (part "M01PTH_SMD_3.25X0.85MM_NO_SILK"))
    )
    (comp (ref "JP981")
      (value "M01PTH_SMD_3.25X0.85MM_NO_SILK")
      (footprint "eagle-import:1X01_SMD_3.25X0.85MM_NO_SILK")
      (libsource (lib "eagle-import") (part "M01PTH_SMD_3.25X0.85MM_NO_SILK"))
    )
    (comp (ref "JP982")
      (value "M01PTH_SMD_3.25X0.85MM_NO_SILK")
      (footprint "eagle-import:1X01_SMD_3.25X0.85MM_NO_SILK")
      (libsource (lib "eagle-import") (part "M01PTH_SMD_3.25X0.85MM_NO_SILK"))
    )
    (comp (ref "JP983")
      (value "M01PTH_SMD_3.25X0.85MM_NO_SILK")
      (footprint "eagle-import:1X01_SMD_3.25X0.85MM_NO_SILK")
      (libsource (lib "eagle-import") (part "M01PTH_SMD_3.25X0.85MM_NO_SILK"))
    )
    (comp (ref "JP984")
      (value "M01PTH_SMD_3.25X0.85MM_NO_SILK")
      (footprint "eagle-import:1X01_SMD_3.25X0.85MM_NO_SILK")
      (libsource (lib "eagle-import") (part "M01PTH_SMD_3.25X0.85MM_NO_SILK"))
    )
    (comp (ref "JP985")
      (value "M01PTH_SMD_3.25X0.85MM_NO_SILK")
      (footprint "eagle-import:1X01_SMD_3.25X0.85MM_NO_SILK")
      (libsource (lib "eagle-import") (part "M01PTH_SMD_3.25X0.85MM_NO_SILK"))
    )
    (comp (ref "JP986")
      (value "M01PTH_SMD_3.25X0.85MM_NO_SILK")
      (footprint "eagle-import:1X01_SMD_3.25X0.85MM_NO_SILK")
      (libsource (lib "eagle-import") (part "M01PTH_SMD_3.25X0.85MM_NO_SILK"))
    )
    (comp (ref "JP987")
      (value "M01PTH_SMD_3.25X0.85MM_NO_SILK")
      (footprint "eagle-import:1X01_SMD_3.25X0.85MM_NO_SILK")
      (libsource (lib "eagle-import") (part "M01PTH_SMD_3.25X0.85MM_NO_SILK"))
    )
    (comp (ref "JP988")
      (value "M01PTH_SMD_3.25X0.85MM_NO_SILK")
      (footprint "eagle-import:1X01_SMD_3.25X0.85MM_NO_SILK")
      (libsource (lib "eagle-import") (part "M01PTH_SMD_3.25X0.85MM_NO_SILK"))
    )
    (comp (ref "JP989")
      (value "M01PTH_SMD_3.25X0.85MM_NO_SILK")
      (footprint "eagle-import:1X01_SMD_3.25X0.85MM_NO_SILK")
      (libsource (lib "eagle-import") (part "M01PTH_SMD_3.25X0.85MM_NO_SILK"))
    )
    (comp (ref "JP990")
      (value "M01PTH_SMD_3.25X0.85MM_NO_SILK")
      (footprint "eagle-import:1X01_SMD_3.25X0.85MM_NO_SILK")
      (libsource (lib "eagle-import") (part "M01PTH_SMD_3.25X0.85MM_NO_SILK"))
    )
    (comp (ref "JP991")
      (value "M01PTH_SMD_3.25X0.85MM_NO_SILK")
      (footprint "eagle-import:1X01_SMD_3.25X0.85MM_NO_SILK")
      (libsource (lib "eagle-import") (part "M01PTH_SMD_3.25X0.85MM_NO_SILK"))
    )
    (comp (ref "JP992")
      (value "M01PTH_SMD_3.25X0.85MM_NO_SILK")
      (footprint "eagle-import:1X01_SMD_3.25X0.85MM_NO_SILK")
      (libsource (lib "eagle-import") (part "M01PTH_SMD_3.25X0.85MM_NO_SILK"))
    )
    (comp (ref "JP993")
      (value "M01PTH_SMD_3.25X0.85MM_NO_SILK")
      (footprint "eagle-import:1X01_SMD_3.25X0.85MM_NO_SILK")
      (libsource (lib "eagle-import") (part "M01PTH_SMD_3.25X0.85MM_NO_SILK"))
    )
    (comp (ref "JP994")
      (value "M01PTH_SMD_3.25X0.85MM_NO_SILK")
      (footprint "eagle-import:1X01_SMD_3.25X0.85MM_NO_SILK")
      (libsource (lib "eagle-import") (part "M01PTH_SMD_3.25X0.85MM_NO_SILK"))
    )
    (comp (ref "JP995")
      (value "M01PTH_SMD_3.25X0.85MM_NO_SILK")
      (footprint "eagle-import:1X01_SMD_3.25X0.85MM_NO_SILK")
      (libsource (lib "eagle-import") (part "M01PTH_SMD_3.25X0.85MM_NO_SILK"))
    )
    (comp (ref "JP996")
      (value "M01PTH_SMD_3.25X0.85MM_NO_SILK")
      (footprint "eagle-import:1X01_SMD_3.25X0.85MM_NO_SILK")
      (libsource (lib "eagle-import") (part "M01PTH_SMD_3.25X0.85MM_NO_SILK"))
    )
    (comp (ref "JP997")
      (value "M01PTH_SMD_3.25X0.85MM_NO_SILK")
      (footprint "eagle-import:1X01_SMD_3.25X0.85MM_NO_SILK")
      (libsource (lib "eagle-import") (part "M01PTH_SMD_3.25X0.85MM_NO_SILK"))
    )
    (comp (ref "JP998")
      (value "M01PTH_SMD_3.25X0.85MM_NO_SILK")
      (footprint "eagle-import:1X01_SMD_3.25X0.85MM_NO_SILK")
      (libsource (lib "eagle-import") (part "M01PTH_SMD_3.25X0.85MM_NO_SILK"))
    )
    (comp (ref "JP999")
      (value "M01PTH_SMD_3.25X0.85MM_NO_SILK")
      (footprint "eagle-import:1X01_SMD_3.25X0.85MM_NO_SILK")
      (libsource (lib "eagle-import") (part "M01PTH_SMD_3.25X0.85MM_NO_SILK"))
    )
    (comp (ref "JP1000")
      (value "M01PTH_SMD_3.25X0.85MM_NO_SILK")
      (footprint "eagle-import:1X01_SMD_3.25X0.85MM_NO_SILK")
      (libsource (lib "eagle-import") (part "M01PTH_SMD_3.25X0.85MM_NO_SILK"))
    )
    (comp (ref "JP1001")
      (value "M01PTH_SMD_3.25X0.85MM_NO_SILK")
      (footprint "eagle-import:1X01_SMD_3.25X0.85MM_NO_SILK")
      (libsource (lib "eagle-import") (part "M01PTH_SMD_3.25X0.85MM_NO_SILK"))
    )
    (comp (ref "JP1002")
      (value "M01PTH_SMD_3.25X0.85MM_NO_SILK")
      (footprint "eagle-import:1X01_SMD_3.25X0.85MM_NO_SILK")
      (libsource (lib "eagle-import") (part "M01PTH_SMD_3.25X0.85MM_NO_SILK"))
    )
    (comp (ref "JP1003")
      (value "M01PTH_SMD_3.25X0.85MM_NO_SILK")
      (footprint "eagle-import:1X01_SMD_3.25X0.85MM_NO_SILK")
      (libsource (lib "eagle-import") (part "M01PTH_SMD_3.25X0.85MM_NO_SILK"))
    )
    (comp (ref "JP1004")
      (value "M01PTH_SMD_3.25X0.85MM_NO_SILK")
      (footprint "eagle-import:1X01_SMD_3.25X0.85MM_NO_SILK")
      (libsource (lib "eagle-import") (part "M01PTH_SMD_3.25X0.85MM_NO_SILK"))
    )
    (comp (ref "JP1005")
      (value "M01PTH_SMD_3.25X0.85MM_NO_SILK")
      (footprint "eagle-import:1X01_SMD_3.25X0.85MM_NO_SILK")
      (libsource (lib "eagle-import") (part "M01PTH_SMD_3.25X0.85MM_NO_SILK"))
    )
    (comp (ref "JP1006")
      (value "M01PTH_SMD_3.25X0.85MM_NO_SILK")
      (footprint "eagle-import:1X01_SMD_3.25X0.85MM_NO_SILK")
      (libsource (lib "eagle-import") (part "M01PTH_SMD_3.25X0.85MM_NO_SILK"))
    )
    (comp (ref "JP1007")
      (value "M01PTH_SMD_3.25X0.85MM_NO_SILK")
      (footprint "eagle-import:1X01_SMD_3.25X0.85MM_NO_SILK")
      (libsource (lib "eagle-import") (part "M01PTH_SMD_3.25X0.85MM_NO_SILK"))
    )
    (comp (ref "JP1008")
      (value "M01PTH_SMD_3.25X0.85MM_NO_SILK")
      (footprint "eagle-import:1X01_SMD_3.25X0.85MM_NO_SILK")
      (libsource (lib "eagle-import") (part "M01PTH_SMD_3.25X0.85MM_NO_SILK"))
    )
    (comp (ref "JP1009")
      (value "M01PTH_SMD_3.25X0.85MM_NO_SILK")
      (footprint "eagle-import:1X01_SMD_3.25X0.85MM_NO_SILK")
      (libsource (lib "eagle-import") (part "M01PTH_SMD_3.25X0.85MM_NO_SILK"))
    )
    (comp (ref "JP1010")
      (value "M01PTH_SMD_3.25X0.85MM_NO_SILK")
      (footprint "eagle-import:1X01_SMD_3.25X0.85MM_NO_SILK")
      (libsource (lib "eagle-import") (part "M01PTH_SMD_3.25X0.85MM_NO_SILK"))
    )
    (comp (ref "JP1011")
      (value "M01PTH_SMD_3.25X0.85MM_NO_SILK")
      (footprint "eagle-import:1X01_SMD_3.25X0.85MM_NO_SILK")
      (libsource (lib "eagle-import") (part "M01PTH_SMD_3.25X0.85MM_NO_SILK"))
    )
    (comp (ref "JP1012")
      (value "M01PTH_SMD_3.25X0.85MM_NO_SILK")
      (footprint "eagle-import:1X01_SMD_3.25X0.85MM_NO_SILK")
      (libsource (lib "eagle-import") (part "M01PTH_SMD_3.25X0.85MM_NO_SILK"))
    )
    (comp (ref "JP1013")
      (value "M01PTH_SMD_3.25X0.85MM_NO_SILK")
      (footprint "eagle-import:1X01_SMD_3.25X0.85MM_NO_SILK")
      (libsource (lib "eagle-import") (part "M01PTH_SMD_3.25X0.85MM_NO_SILK"))
    )
    (comp (ref "JP1014")
      (value "M01PTH_SMD_3.25X0.85MM_NO_SILK")
      (footprint "eagle-import:1X01_SMD_3.25X0.85MM_NO_SILK")
      (libsource (lib "eagle-import") (part "M01PTH_SMD_3.25X0.85MM_NO_SILK"))
    )
    (comp (ref "JP1015")
      (value "M01PTH_SMD_3.25X0.85MM_NO_SILK")
      (footprint "eagle-import:1X01_SMD_3.25X0.85MM_NO_SILK")
      (libsource (lib "eagle-import") (part "M01PTH_SMD_3.25X0.85MM_NO_SILK"))
    )
    (comp (ref "JP1016")
      (value "M01PTH_SMD_3.25X0.85MM_NO_SILK")
      (footprint "eagle-import:1X01_SMD_3.25X0.85MM_NO_SILK")
      (libsource (lib "eagle-import") (part "M01PTH_SMD_3.25X0.85MM_NO_SILK"))
    )
    (comp (ref "JP1017")
      (value "M01PTH_SMD_3.25X0.85MM_NO_SILK")
      (footprint "eagle-import:1X01_SMD_3.25X0.85MM_NO_SILK")
      (libsource (lib "eagle-import") (part "M01PTH_SMD_3.25X0.85MM_NO_SILK"))
    )
    (comp (ref "JP1018")
      (value "M01PTH_SMD_3.25X0.85MM_NO_SILK")
      (footprint "eagle-import:1X01_SMD_3.25X0.85MM_NO_SILK")
      (libsource (lib "eagle-import") (part "M01PTH_SMD_3.25X0.85MM_NO_SILK"))
    )
    (comp (ref "JP1019")
      (value "M01PTH_SMD_3.25X0.85MM_NO_SILK")
      (footprint "eagle-import:1X01_SMD_3.25X0.85MM_NO_SILK")
      (libsource (lib "eagle-import") (part "M01PTH_SMD_3.25X0.85MM_NO_SILK"))
    )
    (comp (ref "JP1020")
      (value "M01PTH_SMD_3.25X0.85MM_NO_SILK")
      (footprint "eagle-import:1X01_SMD_3.25X0.85MM_NO_SILK")
      (libsource (lib "eagle-import") (part "M01PTH_SMD_3.25X0.85MM_NO_SILK"))
    )
    (comp (ref "JP1021")
      (value "M01PTH_SMD_3.25X0.85MM_NO_SILK")
      (footprint "eagle-import:1X01_SMD_3.25X0.85MM_NO_SILK")
      (libsource (lib "eagle-import") (part "M01PTH_SMD_3.25X0.85MM_NO_SILK"))
    )
    (comp (ref "JP1022")
      (value "M01PTH_SMD_3.25X0.85MM_NO_SILK")
      (footprint "eagle-import:1X01_SMD_3.25X0.85MM_NO_SILK")
      (libsource (lib "eagle-import") (part "M01PTH_SMD_3.25X0.85MM_NO_SILK"))
    )
    (comp (ref "JP1023")
      (value "M01PTH_SMD_3.25X0.85MM_NO_SILK")
      (footprint "eagle-import:1X01_SMD_3.25X0.85MM_NO_SILK")
      (libsource (lib "eagle-import") (part "M01PTH_SMD_3.25X0.85MM_NO_SILK"))
    )
    (comp (ref "JP1024")
      (value "M01PTH_SMD_3.25X0.85MM_NO_SILK")
      (footprint "eagle-import:1X01_SMD_3.25X0.85MM_NO_SILK")
      (libsource (lib "eagle-import") (part "M01PTH_SMD_3.25X0.85MM_NO_SILK"))
    )
    (comp (ref "JP1025")
      (value "M01PTH_SMD_3.25X0.85MM_NO_SILK")
      (footprint "eagle-import:1X01_SMD_3.25X0.85MM_NO_SILK")
      (libsource (lib "eagle-import") (part "M01PTH_SMD_3.25X0.85MM_NO_SILK"))
    )
    (comp (ref "JP1026")
      (value "M01PTH_SMD_3.25X0.85MM_NO_SILK")
      (footprint "eagle-import:1X01_SMD_3.25X0.85MM_NO_SILK")
      (libsource (lib "eagle-import") (part "M01PTH_SMD_3.25X0.85MM_NO_SILK"))
    )
    (comp (ref "JP1027")
      (value "M01PTH_SMD_3.25X0.85MM_NO_SILK")
      (footprint "eagle-import:1X01_SMD_3.25X0.85MM_NO_SILK")
      (libsource (lib "eagle-import") (part "M01PTH_SMD_3.25X0.85MM_NO_SILK"))
    )
    (comp (ref "JP1028")
      (value "M01PTH_SMD_3.25X0.85MM_NO_SILK")
      (footprint "eagle-import:1X01_SMD_3.25X0.85MM_NO_SILK")
      (libsource (lib "eagle-import") (part "M01PTH_SMD_3.25X0.85MM_NO_SILK"))
    )
    (comp (ref "JP1029")
      (value "M01PTH_SMD_3.25X0.85MM_NO_SILK")
      (footprint "eagle-import:1X01_SMD_3.25X0.85MM_NO_SILK")
      (libsource (lib "eagle-import") (part "M01PTH_SMD_3.25X0.85MM_NO_SILK"))
    )
    (comp (ref "JP1030")
      (value "M01PTH_SMD_3.25X0.85MM_NO_SILK")
      (footprint "eagle-import:1X01_SMD_3.25X0.85MM_NO_SILK")
      (libsource (lib "eagle-import") (part "M01PTH_SMD_3.25X0.85MM_NO_SILK"))
    )
    (comp (ref "JP1031")
      (value "M01PTH_SMD_3.25X0.85MM_NO_SILK")
      (footprint "eagle-import:1X01_SMD_3.25X0.85MM_NO_SILK")
      (libsource (lib "eagle-import") (part "M01PTH_SMD_3.25X0.85MM_NO_SILK"))
    )
    (comp (ref "JP1032")
      (value "M01PTH_SMD_3.25X0.85MM_NO_SILK")
      (footprint "eagle-import:1X01_SMD_3.25X0.85MM_NO_SILK")
      (libsource (lib "eagle-import") (part "M01PTH_SMD_3.25X0.85MM_NO_SILK"))
    )
    (comp (ref "JP1033")
      (value "M01PTH_SMD_3.25X0.85MM_NO_SILK")
      (footprint "eagle-import:1X01_SMD_3.25X0.85MM_NO_SILK")
      (libsource (lib "eagle-import") (part "M01PTH_SMD_3.25X0.85MM_NO_SILK"))
    )
    (comp (ref "JP1034")
      (value "M01PTH_SMD_3.25X0.85MM_NO_SILK")
      (footprint "eagle-import:1X01_SMD_3.25X0.85MM_NO_SILK")
      (libsource (lib "eagle-import") (part "M01PTH_SMD_3.25X0.85MM_NO_SILK"))
    )
    (comp (ref "JP1035")
      (value "M01PTH_SMD_3.25X0.85MM_NO_SILK")
      (footprint "eagle-import:1X01_SMD_3.25X0.85MM_NO_SILK")
      (libsource (lib "eagle-import") (part "M01PTH_SMD_3.25X0.85MM_NO_SILK"))
    )
    (comp (ref "JP1036")
      (value "M01PTH_SMD_3.25X0.85MM_NO_SILK")
      (footprint "eagle-import:1X01_SMD_3.25X0.85MM_NO_SILK")
      (libsource (lib "eagle-import") (part "M01PTH_SMD_3.25X0.85MM_NO_SILK"))
    )
    (comp (ref "JP1037")
      (value "M01PTH_SMD_3.25X0.85MM_NO_SILK")
      (footprint "eagle-import:1X01_SMD_3.25X0.85MM_NO_SILK")
      (libsource (lib "eagle-import") (part "M01PTH_SMD_3.25X0.85MM_NO_SILK"))
    )
    (comp (ref "JP1038")
      (value "M01PTH_SMD_3.25X0.85MM_NO_SILK")
      (footprint "eagle-import:1X01_SMD_3.25X0.85MM_NO_SILK")
      (libsource (lib "eagle-import") (part "M01PTH_SMD_3.25X0.85MM_NO_SILK"))
    )
    (comp (ref "JP1039")
      (value "M01PTH_SMD_3.25X0.85MM_NO_SILK")
      (footprint "eagle-import:1X01_SMD_3.25X0.85MM_NO_SILK")
      (libsource (lib "eagle-import") (part "M01PTH_SMD_3.25X0.85MM_NO_SILK"))
    )
    (comp (ref "JP1040")
      (value "M01PTH_SMD_3.25X0.85MM_NO_SILK")
      (footprint "eagle-import:1X01_SMD_3.25X0.85MM_NO_SILK")
      (libsource (lib "eagle-import") (part "M01PTH_SMD_3.25X0.85MM_NO_SILK"))
    )
    (comp (ref "JP1041")
      (value "M01PTH_SMD_3.25X0.85MM_NO_SILK")
      (footprint "eagle-import:1X01_SMD_3.25X0.85MM_NO_SILK")
      (libsource (lib "eagle-import") (part "M01PTH_SMD_3.25X0.85MM_NO_SILK"))
    )
    (comp (ref "JP1042")
      (value "M01PTH_SMD_3.25X0.85MM_NO_SILK")
      (footprint "eagle-import:1X01_SMD_3.25X0.85MM_NO_SILK")
      (libsource (lib "eagle-import") (part "M01PTH_SMD_3.25X0.85MM_NO_SILK"))
    )
    (comp (ref "JP1043")
      (value "M01PTH_SMD_3.25X0.85MM_NO_SILK")
      (footprint "eagle-import:1X01_SMD_3.25X0.85MM_NO_SILK")
      (libsource (lib "eagle-import") (part "M01PTH_SMD_3.25X0.85MM_NO_SILK"))
    )
    (comp (ref "JP1044")
      (value "M01PTH_SMD_3.25X0.85MM_NO_SILK")
      (footprint "eagle-import:1X01_SMD_3.25X0.85MM_NO_SILK")
      (libsource (lib "eagle-import") (part "M01PTH_SMD_3.25X0.85MM_NO_SILK"))
    )
    (comp (ref "JP1045")
      (value "M01PTH_SMD_3.25X0.85MM_NO_SILK")
      (footprint "eagle-import:1X01_SMD_3.25X0.85MM_NO_SILK")
      (libsource (lib "eagle-import") (part "M01PTH_SMD_3.25X0.85MM_NO_SILK"))
    )
    (comp (ref "JP1046")
      (value "M01PTH_SMD_3.25X0.85MM_NO_SILK")
      (footprint "eagle-import:1X01_SMD_3.25X0.85MM_NO_SILK")
      (libsource (lib "eagle-import") (part "M01PTH_SMD_3.25X0.85MM_NO_SILK"))
    )
    (comp (ref "JP1047")
      (value "M01PTH_SMD_3.25X0.85MM_NO_SILK")
      (footprint "eagle-import:1X01_SMD_3.25X0.85MM_NO_SILK")
      (libsource (lib "eagle-import") (part "M01PTH_SMD_3.25X0.85MM_NO_SILK"))
    )
    (comp (ref "JP1048")
      (value "M01PTH_SMD_3.25X0.85MM_NO_SILK")
      (footprint "eagle-import:1X01_SMD_3.25X0.85MM_NO_SILK")
      (libsource (lib "eagle-import") (part "M01PTH_SMD_3.25X0.85MM_NO_SILK"))
    )
    (comp (ref "JP1049")
      (value "M01PTH_SMD_3.25X0.85MM_NO_SILK")
      (footprint "eagle-import:1X01_SMD_3.25X0.85MM_NO_SILK")
      (libsource (lib "eagle-import") (part "M01PTH_SMD_3.25X0.85MM_NO_SILK"))
    )
    (comp (ref "JP1050")
      (value "M01PTH_SMD_3.25X0.85MM_NO_SILK")
      (footprint "eagle-import:1X01_SMD_3.25X0.85MM_NO_SILK")
      (libsource (lib "eagle-import") (part "M01PTH_SMD_3.25X0.85MM_NO_SILK"))
    )
    (comp (ref "JP1051")
      (value "M01PTH_SMD_3.25X0.85MM_NO_SILK")
      (footprint "eagle-import:1X01_SMD_3.25X0.85MM_NO_SILK")
      (libsource (lib "eagle-import") (part "M01PTH_SMD_3.25X0.85MM_NO_SILK"))
    )
    (comp (ref "JP1052")
      (value "M01PTH_SMD_3.25X0.85MM_NO_SILK")
      (footprint "eagle-import:1X01_SMD_3.25X0.85MM_NO_SILK")
      (libsource (lib "eagle-import") (part "M01PTH_SMD_3.25X0.85MM_NO_SILK"))
    )
    (comp (ref "JP1053")
      (value "M01PTH_SMD_3.25X0.85MM_NO_SILK")
      (footprint "eagle-import:1X01_SMD_3.25X0.85MM_NO_SILK")
      (libsource (lib "eagle-import") (part "M01PTH_SMD_3.25X0.85MM_NO_SILK"))
    )
    (comp (ref "JP1054")
      (value "M01PTH_SMD_3.25X0.85MM_NO_SILK")
      (footprint "eagle-import:1X01_SMD_3.25X0.85MM_NO_SILK")
      (libsource (lib "eagle-import") (part "M01PTH_SMD_3.25X0.85MM_NO_SILK"))
    )
    (comp (ref "JP1055")
      (value "M01PTH_SMD_3.25X0.85MM_NO_SILK")
      (footprint "eagle-import:1X01_SMD_3.25X0.85MM_NO_SILK")
      (libsource (lib "eagle-import") (part "M01PTH_SMD_3.25X0.85MM_NO_SILK"))
    )
    (comp (ref "JP1056")
      (value "M01PTH_SMD_3.25X0.85MM_NO_SILK")
      (footprint "eagle-import:1X01_SMD_3.25X0.85MM_NO_SILK")
      (libsource (lib "eagle-import") (part "M01PTH_SMD_3.25X0.85MM_NO_SILK"))
    )
    (comp (ref "JP1057")
      (value "M01PTH_SMD_3.25X0.85MM_NO_SILK")
      (footprint "eagle-import:1X01_SMD_3.25X0.85MM_NO_SILK")
      (libsource (lib "eagle-import") (part "M01PTH_SMD_3.25X0.85MM_NO_SILK"))
    )
    (comp (ref "JP1058")
      (value "M01PTH_SMD_3.25X0.85MM_NO_SILK")
      (footprint "eagle-import:1X01_SMD_3.25X0.85MM_NO_SILK")
      (libsource (lib "eagle-import") (part "M01PTH_SMD_3.25X0.85MM_NO_SILK"))
    )
    (comp (ref "JP1059")
      (value "M01PTH_SMD_3.25X0.85MM_NO_SILK")
      (footprint "eagle-import:1X01_SMD_3.25X0.85MM_NO_SILK")
      (libsource (lib "eagle-import") (part "M01PTH_SMD_3.25X0.85MM_NO_SILK"))
    )
    (comp (ref "JP1060")
      (value "M01PTH_SMD_3.25X0.85MM_NO_SILK")
      (footprint "eagle-import:1X01_SMD_3.25X0.85MM_NO_SILK")
      (libsource (lib "eagle-import") (part "M01PTH_SMD_3.25X0.85MM_NO_SILK"))
    )
    (comp (ref "JP1061")
      (value "M01PTH_SMD_3.25X0.85MM_NO_SILK")
      (footprint "eagle-import:1X01_SMD_3.25X0.85MM_NO_SILK")
      (libsource (lib "eagle-import") (part "M01PTH_SMD_3.25X0.85MM_NO_SILK"))
    )
    (comp (ref "JP1062")
      (value "M01PTH_SMD_3.25X0.85MM_NO_SILK")
      (footprint "eagle-import:1X01_SMD_3.25X0.85MM_NO_SILK")
      (libsource (lib "eagle-import") (part "M01PTH_SMD_3.25X0.85MM_NO_SILK"))
    )
    (comp (ref "JP1063")
      (value "M01PTH_SMD_3.25X0.85MM_NO_SILK")
      (footprint "eagle-import:1X01_SMD_3.25X0.85MM_NO_SILK")
      (libsource (lib "eagle-import") (part "M01PTH_SMD_3.25X0.85MM_NO_SILK"))
    )
    (comp (ref "JP1064")
      (value "M01PTH_SMD_3.25X0.85MM_NO_SILK")
      (footprint "eagle-import:1X01_SMD_3.25X0.85MM_NO_SILK")
      (libsource (lib "eagle-import") (part "M01PTH_SMD_3.25X0.85MM_NO_SILK"))
    )
    (comp (ref "JP1065")
      (value "M01PTH_SMD_3.25X0.85MM_NO_SILK")
      (footprint "eagle-import:1X01_SMD_3.25X0.85MM_NO_SILK")
      (libsource (lib "eagle-import") (part "M01PTH_SMD_3.25X0.85MM_NO_SILK"))
    )
    (comp (ref "JP1066")
      (value "M01PTH_SMD_3.25X0.85MM_NO_SILK")
      (footprint "eagle-import:1X01_SMD_3.25X0.85MM_NO_SILK")
      (libsource (lib "eagle-import") (part "M01PTH_SMD_3.25X0.85MM_NO_SILK"))
    )
    (comp (ref "JP1067")
      (value "M01PTH_SMD_3.25X0.85MM_NO_SILK")
      (footprint "eagle-import:1X01_SMD_3.25X0.85MM_NO_SILK")
      (libsource (lib "eagle-import") (part "M01PTH_SMD_3.25X0.85MM_NO_SILK"))
    )
    (comp (ref "JP1068")
      (value "M01PTH_SMD_3.25X0.85MM_NO_SILK")
      (footprint "eagle-import:1X01_SMD_3.25X0.85MM_NO_SILK")
      (libsource (lib "eagle-import") (part "M01PTH_SMD_3.25X0.85MM_NO_SILK"))
    )
    (comp (ref "JP1069")
      (value "M01PTH_SMD_3.25X0.85MM_NO_SILK")
      (footprint "eagle-import:1X01_SMD_3.25X0.85MM_NO_SILK")
      (libsource (lib "eagle-import") (part "M01PTH_SMD_3.25X0.85MM_NO_SILK"))
    )
    (comp (ref "JP1070")
      (value "M01PTH_SMD_3.25X0.85MM_NO_SILK")
      (footprint "eagle-import:1X01_SMD_3.25X0.85MM_NO_SILK")
      (libsource (lib "eagle-import") (part "M01PTH_SMD_3.25X0.85MM_NO_SILK"))
    )
    (comp (ref "JP1071")
      (value "M01PTH_SMD_3.25X0.85MM_NO_SILK")
      (footprint "eagle-import:1X01_SMD_3.25X0.85MM_NO_SILK")
      (libsource (lib "eagle-import") (part "M01PTH_SMD_3.25X0.85MM_NO_SILK"))
    )
    (comp (ref "JP1072")
      (value "M01PTH_SMD_3.25X0.85MM_NO_SILK")
      (footprint "eagle-import:1X01_SMD_3.25X0.85MM_NO_SILK")
      (libsource (lib "eagle-import") (part "M01PTH_SMD_3.25X0.85MM_NO_SILK"))
    )
    (comp (ref "JP1073")
      (value "M01PTH_SMD_3.25X0.85MM_NO_SILK")
      (footprint "eagle-import:1X01_SMD_3.25X0.85MM_NO_SILK")
      (libsource (lib "eagle-import") (part "M01PTH_SMD_3.25X0.85MM_NO_SILK"))
    )
    (comp (ref "JP1074")
      (value "M01PTH_SMD_3.25X0.85MM_NO_SILK")
      (footprint "eagle-import:1X01_SMD_3.25X0.85MM_NO_SILK")
      (libsource (lib "eagle-import") (part "M01PTH_SMD_3.25X0.85MM_NO_SILK"))
    )
    (comp (ref "JP1075")
      (value "M01PTH_SMD_3.25X0.85MM_NO_SILK")
      (footprint "eagle-import:1X01_SMD_3.25X0.85MM_NO_SILK")
      (libsource (lib "eagle-import") (part "M01PTH_SMD_3.25X0.85MM_NO_SILK"))
    )
    (comp (ref "JP1076")
      (value "M01PTH_SMD_3.25X0.85MM_NO_SILK")
      (footprint "eagle-import:1X01_SMD_3.25X0.85MM_NO_SILK")
      (libsource (lib "eagle-import") (part "M01PTH_SMD_3.25X0.85MM_NO_SILK"))
    )
    (comp (ref "JP1077")
      (value "M01PTH_SMD_3.25X0.85MM_NO_SILK")
      (footprint "eagle-import:1X01_SMD_3.25X0.85MM_NO_SILK")
      (libsource (lib "eagle-import") (part "M01PTH_SMD_3.25X0.85MM_NO_SILK"))
    )
    (comp (ref "JP1078")
      (value "M01PTH_SMD_3.25X0.85MM_NO_SILK")
      (footprint "eagle-import:1X01_SMD_3.25X0.85MM_NO_SILK")
      (libsource (lib "eagle-import") (part "M01PTH_SMD_3.25X0.85MM_NO_SILK"))
    )
    (comp (ref "JP1079")
      (value "M01PTH_SMD_3.25X0.85MM_NO_SILK")
      (footprint "eagle-import:1X01_SMD_3.25X0.85MM_NO_SILK")
      (libsource (lib "eagle-import") (part "M01PTH_SMD_3.25X0.85MM_NO_SILK"))
    )
    (comp (ref "JP1080")
      (value "M01PTH_SMD_3.25X0.85MM_NO_SILK")
      (footprint "eagle-import:1X01_SMD_3.25X0.85MM_NO_SILK")
      (libsource (lib "eagle-import") (part "M01PTH_SMD_3.25X0.85MM_NO_SILK"))
    )
    (comp (ref "JP1081")
      (value "M01PTH_SMD_3.25X0.85MM_NO_SILK")
      (footprint "eagle-import:1X01_SMD_3.25X0.85MM_NO_SILK")
      (libsource (lib "eagle-import") (part "M01PTH_SMD_3.25X0.85MM_NO_SILK"))
    )
    (comp (ref "JP1082")
      (value "M01PTH_SMD_3.25X0.85MM_NO_SILK")
      (footprint "eagle-import:1X01_SMD_3.25X0.85MM_NO_SILK")
      (libsource (lib "eagle-import") (part "M01PTH_SMD_3.25X0.85MM_NO_SILK"))
    )
    (comp (ref "JP1083")
      (value "M01PTH_SMD_3.25X0.85MM_NO_SILK")
      (footprint "eagle-import:1X01_SMD_3.25X0.85MM_NO_SILK")
      (libsource (lib "eagle-import") (part "M01PTH_SMD_3.25X0.85MM_NO_SILK"))
    )
    (comp (ref "JP1084")
      (value "M01PTH_SMD_3.25X0.85MM_NO_SILK")
      (footprint "eagle-import:1X01_SMD_3.25X0.85MM_NO_SILK")
      (libsource (lib "eagle-import") (part "M01PTH_SMD_3.25X0.85MM_NO_SILK"))
    )
    (comp (ref "JP1085")
      (value "M01PTH_SMD_3.25X0.85MM_NO_SILK")
      (footprint "eagle-import:1X01_SMD_3.25X0.85MM_NO_SILK")
      (libsource (lib "eagle-import") (part "M01PTH_SMD_3.25X0.85MM_NO_SILK"))
    )
    (comp (ref "JP1086")
      (value "M01PTH_SMD_3.25X0.85MM_NO_SILK")
      (footprint "eagle-import:1X01_SMD_3.25X0.85MM_NO_SILK")
      (libsource (lib "eagle-import") (part "M01PTH_SMD_3.25X0.85MM_NO_SILK"))
    )
    (comp (ref "JP1087")
      (value "M01PTH_SMD_3.25X0.85MM_NO_SILK")
      (footprint "eagle-import:1X01_SMD_3.25X0.85MM_NO_SILK")
      (libsource (lib "eagle-import") (part "M01PTH_SMD_3.25X0.85MM_NO_SILK"))
    )
    (comp (ref "JP1088")
      (value "M01PTH_SMD_3.25X0.85MM_NO_SILK")
      (footprint "eagle-import:1X01_SMD_3.25X0.85MM_NO_SILK")
      (libsource (lib "eagle-import") (part "M01PTH_SMD_3.25X0.85MM_NO_SILK"))
    )
    (comp (ref "JP1089")
      (value "M01PTH_SMD_3.25X0.85MM_NO_SILK")
      (footprint "eagle-import:1X01_SMD_3.25X0.85MM_NO_SILK")
      (libsource (lib "eagle-import") (part "M01PTH_SMD_3.25X0.85MM_NO_SILK"))
    )
    (comp (ref "JP1090")
      (value "M01PTH_SMD_3.25X0.85MM_NO_SILK")
      (footprint "eagle-import:1X01_SMD_3.25X0.85MM_NO_SILK")
      (libsource (lib "eagle-import") (part "M01PTH_SMD_3.25X0.85MM_NO_SILK"))
    )
    (comp (ref "JP1091")
      (value "M01PTH_SMD_3.25X0.85MM_NO_SILK")
      (footprint "eagle-import:1X01_SMD_3.25X0.85MM_NO_SILK")
      (libsource (lib "eagle-import") (part "M01PTH_SMD_3.25X0.85MM_NO_SILK"))
    )
    (comp (ref "JP1092")
      (value "M01PTH_SMD_3.25X0.85MM_NO_SILK")
      (footprint "eagle-import:1X01_SMD_3.25X0.85MM_NO_SILK")
      (libsource (lib "eagle-import") (part "M01PTH_SMD_3.25X0.85MM_NO_SILK"))
    )
    (comp (ref "JP1093")
      (value "M01PTH_SMD_3.25X0.85MM_NO_SILK")
      (footprint "eagle-import:1X01_SMD_3.25X0.85MM_NO_SILK")
      (libsource (lib "eagle-import") (part "M01PTH_SMD_3.25X0.85MM_NO_SILK"))
    )
    (comp (ref "JP1094")
      (value "M01PTH_SMD_3.25X0.85MM_NO_SILK")
      (footprint "eagle-import:1X01_SMD_3.25X0.85MM_NO_SILK")
      (libsource (lib "eagle-import") (part "M01PTH_SMD_3.25X0.85MM_NO_SILK"))
    )
    (comp (ref "JP1095")
      (value "M01PTH_SMD_3.25X0.85MM_NO_SILK")
      (footprint "eagle-import:1X01_SMD_3.25X0.85MM_NO_SILK")
      (libsource (lib "eagle-import") (part "M01PTH_SMD_3.25X0.85MM_NO_SILK"))
    )
    (comp (ref "JP1096")
      (value "M01PTH_SMD_3.25X0.85MM_NO_SILK")
      (footprint "eagle-import:1X01_SMD_3.25X0.85MM_NO_SILK")
      (libsource (lib "eagle-import") (part "M01PTH_SMD_3.25X0.85MM_NO_SILK"))
    )
    (comp (ref "JP1097")
      (value "M01PTH_SMD_3.25X0.85MM_NO_SILK")
      (footprint "eagle-import:1X01_SMD_3.25X0.85MM_NO_SILK")
      (libsource (lib "eagle-import") (part "M01PTH_SMD_3.25X0.85MM_NO_SILK"))
    )
    (comp (ref "JP1098")
      (value "M01PTH_SMD_3.25X0.85MM_NO_SILK")
      (footprint "eagle-import:1X01_SMD_3.25X0.85MM_NO_SILK")
      (libsource (lib "eagle-import") (part "M01PTH_SMD_3.25X0.85MM_NO_SILK"))
    )
    (comp (ref "JP1099")
      (value "M01PTH_SMD_3.25X0.85MM_NO_SILK")
      (footprint "eagle-import:1X01_SMD_3.25X0.85MM_NO_SILK")
      (libsource (lib "eagle-import") (part "M01PTH_SMD_3.25X0.85MM_NO_SILK"))
    )
    (comp (ref "JP1100")
      (value "M01PTH_SMD_3.25X0.85MM_NO_SILK")
      (footprint "eagle-import:1X01_SMD_3.25X0.85MM_NO_SILK")
      (libsource (lib "eagle-import") (part "M01PTH_SMD_3.25X0.85MM_NO_SILK"))
    )
    (comp (ref "JP1101")
      (value "M01PTH_SMD_3.25X0.85MM_NO_SILK")
      (footprint "eagle-import:1X01_SMD_3.25X0.85MM_NO_SILK")
      (libsource (lib "eagle-import") (part "M01PTH_SMD_3.25X0.85MM_NO_SILK"))
    )
    (comp (ref "JP1102")
      (value "M01PTH_SMD_3.25X0.85MM_NO_SILK")
      (footprint "eagle-import:1X01_SMD_3.25X0.85MM_NO_SILK")
      (libsource (lib "eagle-import") (part "M01PTH_SMD_3.25X0.85MM_NO_SILK"))
    )
    (comp (ref "JP1103")
      (value "M01PTH_SMD_3.25X0.85MM_NO_SILK")
      (footprint "eagle-import:1X01_SMD_3.25X0.85MM_NO_SILK")
      (libsource (lib "eagle-import") (part "M01PTH_SMD_3.25X0.85MM_NO_SILK"))
    )
    (comp (ref "JP1104")
      (value "M01PTH_SMD_3.25X0.85MM_NO_SILK")
      (footprint "eagle-import:1X01_SMD_3.25X0.85MM_NO_SILK")
      (libsource (lib "eagle-import") (part "M01PTH_SMD_3.25X0.85MM_NO_SILK"))
    )
    (comp (ref "JP1105")
      (value "M01PTH_SMD_3.25X0.85MM_NO_SILK")
      (footprint "eagle-import:1X01_SMD_3.25X0.85MM_NO_SILK")
      (libsource (lib "eagle-import") (part "M01PTH_SMD_3.25X0.85MM_NO_SILK"))
    )
    (comp (ref "JP1106")
      (value "M01PTH_SMD_3.25X0.85MM_NO_SILK")
      (footprint "eagle-import:1X01_SMD_3.25X0.85MM_NO_SILK")
      (libsource (lib "eagle-import") (part "M01PTH_SMD_3.25X0.85MM_NO_SILK"))
    )
    (comp (ref "JP1107")
      (value "M01PTH_SMD_3.25X0.85MM_NO_SILK")
      (footprint "eagle-import:1X01_SMD_3.25X0.85MM_NO_SILK")
      (libsource (lib "eagle-import") (part "M01PTH_SMD_3.25X0.85MM_NO_SILK"))
    )
    (comp (ref "JP1108")
      (value "M01PTH_SMD_3.25X0.85MM_NO_SILK")
      (footprint "eagle-import:1X01_SMD_3.25X0.85MM_NO_SILK")
      (libsource (lib "eagle-import") (part "M01PTH_SMD_3.25X0.85MM_NO_SILK"))
    )
    (comp (ref "JP1109")
      (value "M01PTH_SMD_3.25X0.85MM_NO_SILK")
      (footprint "eagle-import:1X01_SMD_3.25X0.85MM_NO_SILK")
      (libsource (lib "eagle-import") (part "M01PTH_SMD_3.25X0.85MM_NO_SILK"))
    )
    (comp (ref "JP1110")
      (value "M01PTH_SMD_3.25X0.85MM_NO_SILK")
      (footprint "eagle-import:1X01_SMD_3.25X0.85MM_NO_SILK")
      (libsource (lib "eagle-import") (part "M01PTH_SMD_3.25X0.85MM_NO_SILK"))
    )
    (comp (ref "JP1111")
      (value "M01PTH_SMD_3.25X0.85MM_NO_SILK")
      (footprint "eagle-import:1X01_SMD_3.25X0.85MM_NO_SILK")
      (libsource (lib "eagle-import") (part "M01PTH_SMD_3.25X0.85MM_NO_SILK"))
    )
    (comp (ref "JP1112")
      (value "M01PTH_SMD_3.25X0.85MM_NO_SILK")
      (footprint "eagle-import:1X01_SMD_3.25X0.85MM_NO_SILK")
      (libsource (lib "eagle-import") (part "M01PTH_SMD_3.25X0.85MM_NO_SILK"))
    )
    (comp (ref "JP1113")
      (value "M01PTH_SMD_3.25X0.85MM_NO_SILK")
      (footprint "eagle-import:1X01_SMD_3.25X0.85MM_NO_SILK")
      (libsource (lib "eagle-import") (part "M01PTH_SMD_3.25X0.85MM_NO_SILK"))
    )
    (comp (ref "JP1114")
      (value "M01PTH_SMD_3.25X0.85MM_NO_SILK")
      (footprint "eagle-import:1X01_SMD_3.25X0.85MM_NO_SILK")
      (libsource (lib "eagle-import") (part "M01PTH_SMD_3.25X0.85MM_NO_SILK"))
    )
    (comp (ref "JP1115")
      (value "M01PTH_SMD_3.25X0.85MM_NO_SILK")
      (footprint "eagle-import:1X01_SMD_3.25X0.85MM_NO_SILK")
      (libsource (lib "eagle-import") (part "M01PTH_SMD_3.25X0.85MM_NO_SILK"))
    )
    (comp (ref "JP1116")
      (value "M01PTH_SMD_3.25X0.85MM_NO_SILK")
      (footprint "eagle-import:1X01_SMD_3.25X0.85MM_NO_SILK")
      (libsource (lib "eagle-import") (part "M01PTH_SMD_3.25X0.85MM_NO_SILK"))
    )
    (comp (ref "JP1117")
      (value "M01PTH_SMD_3.25X0.85MM_NO_SILK")
      (footprint "eagle-import:1X01_SMD_3.25X0.85MM_NO_SILK")
      (libsource (lib "eagle-import") (part "M01PTH_SMD_3.25X0.85MM_NO_SILK"))
    )
    (comp (ref "JP1118")
      (value "M01PTH_SMD_3.25X0.85MM_NO_SILK")
      (footprint "eagle-import:1X01_SMD_3.25X0.85MM_NO_SILK")
      (libsource (lib "eagle-import") (part "M01PTH_SMD_3.25X0.85MM_NO_SILK"))
    )
    (comp (ref "JP1119")
      (value "M01PTH_SMD_3.25X0.85MM_NO_SILK")
      (footprint "eagle-import:1X01_SMD_3.25X0.85MM_NO_SILK")
      (libsource (lib "eagle-import") (part "M01PTH_SMD_3.25X0.85MM_NO_SILK"))
    )
    (comp (ref "JP1120")
      (value "M01PTH_SMD_3.25X0.85MM_NO_SILK")
      (footprint "eagle-import:1X01_SMD_3.25X0.85MM_NO_SILK")
      (libsource (lib "eagle-import") (part "M01PTH_SMD_3.25X0.85MM_NO_SILK"))
    )
    (comp (ref "JP1121")
      (value "M01PTH_SMD_3.25X0.85MM_NO_SILK")
      (footprint "eagle-import:1X01_SMD_3.25X0.85MM_NO_SILK")
      (libsource (lib "eagle-import") (part "M01PTH_SMD_3.25X0.85MM_NO_SILK"))
    )
    (comp (ref "JP1122")
      (value "M01PTH_SMD_3.25X0.85MM_NO_SILK")
      (footprint "eagle-import:1X01_SMD_3.25X0.85MM_NO_SILK")
      (libsource (lib "eagle-import") (part "M01PTH_SMD_3.25X0.85MM_NO_SILK"))
    )
    (comp (ref "JP1123")
      (value "M01PTH_SMD_3.25X0.85MM_NO_SILK")
      (footprint "eagle-import:1X01_SMD_3.25X0.85MM_NO_SILK")
      (libsource (lib "eagle-import") (part "M01PTH_SMD_3.25X0.85MM_NO_SILK"))
    )
    (comp (ref "JP1124")
      (value "M01PTH_SMD_3.25X0.85MM_NO_SILK")
      (footprint "eagle-import:1X01_SMD_3.25X0.85MM_NO_SILK")
      (libsource (lib "eagle-import") (part "M01PTH_SMD_3.25X0.85MM_NO_SILK"))
    )
    (comp (ref "JP1125")
      (value "M01PTH_SMD_3.25X0.85MM_NO_SILK")
      (footprint "eagle-import:1X01_SMD_3.25X0.85MM_NO_SILK")
      (libsource (lib "eagle-import") (part "M01PTH_SMD_3.25X0.85MM_NO_SILK"))
    )
    (comp (ref "JP1126")
      (value "M01PTH_SMD_3.25X0.85MM_NO_SILK")
      (footprint "eagle-import:1X01_SMD_3.25X0.85MM_NO_SILK")
      (libsource (lib "eagle-import") (part "M01PTH_SMD_3.25X0.85MM_NO_SILK"))
    )
    (comp (ref "JP1127")
      (value "M01PTH_SMD_3.25X0.85MM_NO_SILK")
      (footprint "eagle-import:1X01_SMD_3.25X0.85MM_NO_SILK")
      (libsource (lib "eagle-import") (part "M01PTH_SMD_3.25X0.85MM_NO_SILK"))
    )
    (comp (ref "JP1128")
      (value "M01PTH_SMD_3.25X0.85MM_NO_SILK")
      (footprint "eagle-import:1X01_SMD_3.25X0.85MM_NO_SILK")
      (libsource (lib "eagle-import") (part "M01PTH_SMD_3.25X0.85MM_NO_SILK"))
    )
    (comp (ref "JP1129")
      (value "M01PTH_SMD_3.25X0.85MM_NO_SILK")
      (footprint "eagle-import:1X01_SMD_3.25X0.85MM_NO_SILK")
      (libsource (lib "eagle-import") (part "M01PTH_SMD_3.25X0.85MM_NO_SILK"))
    )
    (comp (ref "JP1130")
      (value "M01PTH_SMD_3.25X0.85MM_NO_SILK")
      (footprint "eagle-import:1X01_SMD_3.25X0.85MM_NO_SILK")
      (libsource (lib "eagle-import") (part "M01PTH_SMD_3.25X0.85MM_NO_SILK"))
    )
    (comp (ref "JP1131")
      (value "M01PTH_SMD_3.25X0.85MM_NO_SILK")
      (footprint "eagle-import:1X01_SMD_3.25X0.85MM_NO_SILK")
      (libsource (lib "eagle-import") (part "M01PTH_SMD_3.25X0.85MM_NO_SILK"))
    )
    (comp (ref "JP1132")
      (value "M01PTH_SMD_3.25X0.85MM_NO_SILK")
      (footprint "eagle-import:1X01_SMD_3.25X0.85MM_NO_SILK")
      (libsource (lib "eagle-import") (part "M01PTH_SMD_3.25X0.85MM_NO_SILK"))
    )
    (comp (ref "JP1133")
      (value "M01PTH_SMD_3.25X0.85MM_NO_SILK")
      (footprint "eagle-import:1X01_SMD_3.25X0.85MM_NO_SILK")
      (libsource (lib "eagle-import") (part "M01PTH_SMD_3.25X0.85MM_NO_SILK"))
    )
    (comp (ref "JP1134")
      (value "M01PTH_SMD_3.25X0.85MM_NO_SILK")
      (footprint "eagle-import:1X01_SMD_3.25X0.85MM_NO_SILK")
      (libsource (lib "eagle-import") (part "M01PTH_SMD_3.25X0.85MM_NO_SILK"))
    )
    (comp (ref "JP1135")
      (value "M01PTH_SMD_3.25X0.85MM_NO_SILK")
      (footprint "eagle-import:1X01_SMD_3.25X0.85MM_NO_SILK")
      (libsource (lib "eagle-import") (part "M01PTH_SMD_3.25X0.85MM_NO_SILK"))
    )
    (comp (ref "JP1136")
      (value "M01PTH_SMD_3.25X0.85MM_NO_SILK")
      (footprint "eagle-import:1X01_SMD_3.25X0.85MM_NO_SILK")
      (libsource (lib "eagle-import") (part "M01PTH_SMD_3.25X0.85MM_NO_SILK"))
    )
    (comp (ref "JP1137")
      (value "M01PTH_SMD_3.25X0.85MM_NO_SILK")
      (footprint "eagle-import:1X01_SMD_3.25X0.85MM_NO_SILK")
      (libsource (lib "eagle-import") (part "M01PTH_SMD_3.25X0.85MM_NO_SILK"))
    )
    (comp (ref "JP1138")
      (value "M01PTH_SMD_3.25X0.85MM_NO_SILK")
      (footprint "eagle-import:1X01_SMD_3.25X0.85MM_NO_SILK")
      (libsource (lib "eagle-import") (part "M01PTH_SMD_3.25X0.85MM_NO_SILK"))
    )
    (comp (ref "JP1139")
      (value "M01PTH_SMD_3.25X0.85MM_NO_SILK")
      (footprint "eagle-import:1X01_SMD_3.25X0.85MM_NO_SILK")
      (libsource (lib "eagle-import") (part "M01PTH_SMD_3.25X0.85MM_NO_SILK"))
    )
    (comp (ref "JP1140")
      (value "M01PTH_SMD_3.25X0.85MM_NO_SILK")
      (footprint "eagle-import:1X01_SMD_3.25X0.85MM_NO_SILK")
      (libsource (lib "eagle-import") (part "M01PTH_SMD_3.25X0.85MM_NO_SILK"))
    )
    (comp (ref "JP1141")
      (value "M01PTH_SMD_3.25X0.85MM_NO_SILK")
      (footprint "eagle-import:1X01_SMD_3.25X0.85MM_NO_SILK")
      (libsource (lib "eagle-import") (part "M01PTH_SMD_3.25X0.85MM_NO_SILK"))
    )
    (comp (ref "JP1142")
      (value "M01PTH_SMD_3.25X0.85MM_NO_SILK")
      (footprint "eagle-import:1X01_SMD_3.25X0.85MM_NO_SILK")
      (libsource (lib "eagle-import") (part "M01PTH_SMD_3.25X0.85MM_NO_SILK"))
    )
    (comp (ref "JP1143")
      (value "M01PTH_SMD_3.25X0.85MM_NO_SILK")
      (footprint "eagle-import:1X01_SMD_3.25X0.85MM_NO_SILK")
      (libsource (lib "eagle-import") (part "M01PTH_SMD_3.25X0.85MM_NO_SILK"))
    )
    (comp (ref "JP1144")
      (value "M01PTH_SMD_3.25X0.85MM_NO_SILK")
      (footprint "eagle-import:1X01_SMD_3.25X0.85MM_NO_SILK")
      (libsource (lib "eagle-import") (part "M01PTH_SMD_3.25X0.85MM_NO_SILK"))
    )
    (comp (ref "JP1145")
      (value "M01PTH_SMD_3.25X0.85MM_NO_SILK")
      (footprint "eagle-import:1X01_SMD_3.25X0.85MM_NO_SILK")
      (libsource (lib "eagle-import") (part "M01PTH_SMD_3.25X0.85MM_NO_SILK"))
    )
    (comp (ref "JP1146")
      (value "M01PTH_SMD_3.25X0.85MM_NO_SILK")
      (footprint "eagle-import:1X01_SMD_3.25X0.85MM_NO_SILK")
      (libsource (lib "eagle-import") (part "M01PTH_SMD_3.25X0.85MM_NO_SILK"))
    )
    (comp (ref "JP1147")
      (value "M01PTH_SMD_3.25X0.85MM_NO_SILK")
      (footprint "eagle-import:1X01_SMD_3.25X0.85MM_NO_SILK")
      (libsource (lib "eagle-import") (part "M01PTH_SMD_3.25X0.85MM_NO_SILK"))
    )
    (comp (ref "JP1148")
      (value "M01PTH_SMD_3.25X0.85MM_NO_SILK")
      (footprint "eagle-import:1X01_SMD_3.25X0.85MM_NO_SILK")
      (libsource (lib "eagle-import") (part "M01PTH_SMD_3.25X0.85MM_NO_SILK"))
    )
    (comp (ref "JP1149")
      (value "M01PTH_SMD_3.25X0.85MM_NO_SILK")
      (footprint "eagle-import:1X01_SMD_3.25X0.85MM_NO_SILK")
      (libsource (lib "eagle-import") (part "M01PTH_SMD_3.25X0.85MM_NO_SILK"))
    )
    (comp (ref "JP1150")
      (value "M01PTH_SMD_3.25X0.85MM_NO_SILK")
      (footprint "eagle-import:1X01_SMD_3.25X0.85MM_NO_SILK")
      (libsource (lib "eagle-import") (part "M01PTH_SMD_3.25X0.85MM_NO_SILK"))
    )
    (comp (ref "JP1151")
      (value "M01PTH_SMD_3.25X0.85MM_NO_SILK")
      (footprint "eagle-import:1X01_SMD_3.25X0.85MM_NO_SILK")
      (libsource (lib "eagle-import") (part "M01PTH_SMD_3.25X0.85MM_NO_SILK"))
    )
    (comp (ref "JP1152")
      (value "M01PTH_SMD_3.25X0.85MM_NO_SILK")
      (footprint "eagle-import:1X01_SMD_3.25X0.85MM_NO_SILK")
      (libsource (lib "eagle-import") (part "M01PTH_SMD_3.25X0.85MM_NO_SILK"))
    )
    (comp (ref "JP1153")
      (value "M01PTH_SMD_3.25X0.85MM_NO_SILK")
      (footprint "eagle-import:1X01_SMD_3.25X0.85MM_NO_SILK")
      (libsource (lib "eagle-import") (part "M01PTH_SMD_3.25X0.85MM_NO_SILK"))
    )
    (comp (ref "JP1154")
      (value "M01PTH_SMD_3.25X0.85MM_NO_SILK")
      (footprint "eagle-import:1X01_SMD_3.25X0.85MM_NO_SILK")
      (libsource (lib "eagle-import") (part "M01PTH_SMD_3.25X0.85MM_NO_SILK"))
    )
    (comp (ref "JP1155")
      (value "M01PTH_SMD_3.25X0.85MM_NO_SILK")
      (footprint "eagle-import:1X01_SMD_3.25X0.85MM_NO_SILK")
      (libsource (lib "eagle-import") (part "M01PTH_SMD_3.25X0.85MM_NO_SILK"))
    )
    (comp (ref "JP1156")
      (value "M01PTH_SMD_3.25X0.85MM_NO_SILK")
      (footprint "eagle-import:1X01_SMD_3.25X0.85MM_NO_SILK")
      (libsource (lib "eagle-import") (part "M01PTH_SMD_3.25X0.85MM_NO_SILK"))
    )
    (comp (ref "JP1157")
      (value "M01PTH_SMD_3.25X0.85MM_NO_SILK")
      (footprint "eagle-import:1X01_SMD_3.25X0.85MM_NO_SILK")
      (libsource (lib "eagle-import") (part "M01PTH_SMD_3.25X0.85MM_NO_SILK"))
    )
    (comp (ref "JP1158")
      (value "M01PTH_SMD_3.25X0.85MM_NO_SILK")
      (footprint "eagle-import:1X01_SMD_3.25X0.85MM_NO_SILK")
      (libsource (lib "eagle-import") (part "M01PTH_SMD_3.25X0.85MM_NO_SILK"))
    )
    (comp (ref "JP1159")
      (value "M01PTH_SMD_3.25X0.85MM_NO_SILK")
      (footprint "eagle-import:1X01_SMD_3.25X0.85MM_NO_SILK")
      (libsource (lib "eagle-import") (part "M01PTH_SMD_3.25X0.85MM_NO_SILK"))
    )
    (comp (ref "JP1160")
      (value "M01PTH_SMD_3.25X0.85MM_NO_SILK")
      (footprint "eagle-import:1X01_SMD_3.25X0.85MM_NO_SILK")
      (libsource (lib "eagle-import") (part "M01PTH_SMD_3.25X0.85MM_NO_SILK"))
    )
    (comp (ref "JP1161")
      (value "M01PTH_SMD_3.25X0.85MM_NO_SILK")
      (footprint "eagle-import:1X01_SMD_3.25X0.85MM_NO_SILK")
      (libsource (lib "eagle-import") (part "M01PTH_SMD_3.25X0.85MM_NO_SILK"))
    )
    (comp (ref "JP1162")
      (value "M01PTH_SMD_3.25X0.85MM_NO_SILK")
      (footprint "eagle-import:1X01_SMD_3.25X0.85MM_NO_SILK")
      (libsource (lib "eagle-import") (part "M01PTH_SMD_3.25X0.85MM_NO_SILK"))
    )
    (comp (ref "JP1163")
      (value "M01PTH_SMD_3.25X0.85MM_NO_SILK")
      (footprint "eagle-import:1X01_SMD_3.25X0.85MM_NO_SILK")
      (libsource (lib "eagle-import") (part "M01PTH_SMD_3.25X0.85MM_NO_SILK"))
    )
    (comp (ref "JP1164")
      (value "M01PTH_SMD_3.25X0.85MM_NO_SILK")
      (footprint "eagle-import:1X01_SMD_3.25X0.85MM_NO_SILK")
      (libsource (lib "eagle-import") (part "M01PTH_SMD_3.25X0.85MM_NO_SILK"))
    )
    (comp (ref "JP1165")
      (value "M01PTH_SMD_3.25X0.85MM_NO_SILK")
      (footprint "eagle-import:1X01_SMD_3.25X0.85MM_NO_SILK")
      (libsource (lib "eagle-import") (part "M01PTH_SMD_3.25X0.85MM_NO_SILK"))
    )
    (comp (ref "JP1166")
      (value "M01PTH_SMD_3.25X0.85MM_NO_SILK")
      (footprint "eagle-import:1X01_SMD_3.25X0.85MM_NO_SILK")
      (libsource (lib "eagle-import") (part "M01PTH_SMD_3.25X0.85MM_NO_SILK"))
    )
    (comp (ref "JP1167")
      (value "M01PTH_SMD_3.25X0.85MM_NO_SILK")
      (footprint "eagle-import:1X01_SMD_3.25X0.85MM_NO_SILK")
      (libsource (lib "eagle-import") (part "M01PTH_SMD_3.25X0.85MM_NO_SILK"))
    )
    (comp (ref "JP1168")
      (value "M01PTH_SMD_3.25X0.85MM_NO_SILK")
      (footprint "eagle-import:1X01_SMD_3.25X0.85MM_NO_SILK")
      (libsource (lib "eagle-import") (part "M01PTH_SMD_3.25X0.85MM_NO_SILK"))
    )
    (comp (ref "JP1169")
      (value "M01PTH_SMD_3.25X0.85MM_NO_SILK")
      (footprint "eagle-import:1X01_SMD_3.25X0.85MM_NO_SILK")
      (libsource (lib "eagle-import") (part "M01PTH_SMD_3.25X0.85MM_NO_SILK"))
    )
    (comp (ref "JP1170")
      (value "M01PTH_SMD_3.25X0.85MM_NO_SILK")
      (footprint "eagle-import:1X01_SMD_3.25X0.85MM_NO_SILK")
      (libsource (lib "eagle-import") (part "M01PTH_SMD_3.25X0.85MM_NO_SILK"))
    )
    (comp (ref "JP1171")
      (value "M01PTH_SMD_3.25X0.85MM_NO_SILK")
      (footprint "eagle-import:1X01_SMD_3.25X0.85MM_NO_SILK")
      (libsource (lib "eagle-import") (part "M01PTH_SMD_3.25X0.85MM_NO_SILK"))
    )
    (comp (ref "JP1172")
      (value "M01PTH_SMD_3.25X0.85MM_NO_SILK")
      (footprint "eagle-import:1X01_SMD_3.25X0.85MM_NO_SILK")
      (libsource (lib "eagle-import") (part "M01PTH_SMD_3.25X0.85MM_NO_SILK"))
    )
    (comp (ref "JP1173")
      (value "M01PTH_SMD_3.25X0.85MM_NO_SILK")
      (footprint "eagle-import:1X01_SMD_3.25X0.85MM_NO_SILK")
      (libsource (lib "eagle-import") (part "M01PTH_SMD_3.25X0.85MM_NO_SILK"))
    )
    (comp (ref "JP1174")
      (value "M01PTH_SMD_3.25X0.85MM_NO_SILK")
      (footprint "eagle-import:1X01_SMD_3.25X0.85MM_NO_SILK")
      (libsource (lib "eagle-import") (part "M01PTH_SMD_3.25X0.85MM_NO_SILK"))
    )
    (comp (ref "JP1175")
      (value "M01PTH_SMD_3.25X0.85MM_NO_SILK")
      (footprint "eagle-import:1X01_SMD_3.25X0.85MM_NO_SILK")
      (libsource (lib "eagle-import") (part "M01PTH_SMD_3.25X0.85MM_NO_SILK"))
    )
    (comp (ref "JP1176")
      (value "M01PTH_SMD_3.25X0.85MM_NO_SILK")
      (footprint "eagle-import:1X01_SMD_3.25X0.85MM_NO_SILK")
      (libsource (lib "eagle-import") (part "M01PTH_SMD_3.25X0.85MM_NO_SILK"))
    )
    (comp (ref "JP1177")
      (value "M01PTH_SMD_3.25X0.85MM_NO_SILK")
      (footprint "eagle-import:1X01_SMD_3.25X0.85MM_NO_SILK")
      (libsource (lib "eagle-import") (part "M01PTH_SMD_3.25X0.85MM_NO_SILK"))
    )
    (comp (ref "JP1178")
      (value "M01PTH_SMD_3.25X0.85MM_NO_SILK")
      (footprint "eagle-import:1X01_SMD_3.25X0.85MM_NO_SILK")
      (libsource (lib "eagle-import") (part "M01PTH_SMD_3.25X0.85MM_NO_SILK"))
    )
    (comp (ref "JP1179")
      (value "M01PTH_SMD_3.25X0.85MM_NO_SILK")
      (footprint "eagle-import:1X01_SMD_3.25X0.85MM_NO_SILK")
      (libsource (lib "eagle-import") (part "M01PTH_SMD_3.25X0.85MM_NO_SILK"))
    )
    (comp (ref "JP1180")
      (value "M01PTH_SMD_3.25X0.85MM_NO_SILK")
      (footprint "eagle-import:1X01_SMD_3.25X0.85MM_NO_SILK")
      (libsource (lib "eagle-import") (part "M01PTH_SMD_3.25X0.85MM_NO_SILK"))
    )
    (comp (ref "JP1181")
      (value "M01PTH_SMD_3.25X0.85MM_NO_SILK")
      (footprint "eagle-import:1X01_SMD_3.25X0.85MM_NO_SILK")
      (libsource (lib "eagle-import") (part "M01PTH_SMD_3.25X0.85MM_NO_SILK"))
    )
    (comp (ref "JP1182")
      (value "M01PTH_SMD_3.25X0.85MM_NO_SILK")
      (footprint "eagle-import:1X01_SMD_3.25X0.85MM_NO_SILK")
      (libsource (lib "eagle-import") (part "M01PTH_SMD_3.25X0.85MM_NO_SILK"))
    )
    (comp (ref "JP1183")
      (value "M01PTH_SMD_3.25X0.85MM_NO_SILK")
      (footprint "eagle-import:1X01_SMD_3.25X0.85MM_NO_SILK")
      (libsource (lib "eagle-import") (part "M01PTH_SMD_3.25X0.85MM_NO_SILK"))
    )
    (comp (ref "JP1184")
      (value "M01PTH_SMD_3.25X0.85MM_NO_SILK")
      (footprint "eagle-import:1X01_SMD_3.25X0.85MM_NO_SILK")
      (libsource (lib "eagle-import") (part "M01PTH_SMD_3.25X0.85MM_NO_SILK"))
    )
    (comp (ref "JP1185")
      (value "M01PTH_SMD_3.25X0.85MM_NO_SILK")
      (footprint "eagle-import:1X01_SMD_3.25X0.85MM_NO_SILK")
      (libsource (lib "eagle-import") (part "M01PTH_SMD_3.25X0.85MM_NO_SILK"))
    )
    (comp (ref "JP1186")
      (value "M01PTH_SMD_3.25X0.85MM_NO_SILK")
      (footprint "eagle-import:1X01_SMD_3.25X0.85MM_NO_SILK")
      (libsource (lib "eagle-import") (part "M01PTH_SMD_3.25X0.85MM_NO_SILK"))
    )
    (comp (ref "JP1187")
      (value "M01PTH_SMD_3.25X0.85MM_NO_SILK")
      (footprint "eagle-import:1X01_SMD_3.25X0.85MM_NO_SILK")
      (libsource (lib "eagle-import") (part "M01PTH_SMD_3.25X0.85MM_NO_SILK"))
    )
    (comp (ref "JP1188")
      (value "M01PTH_SMD_3.25X0.85MM_NO_SILK")
      (footprint "eagle-import:1X01_SMD_3.25X0.85MM_NO_SILK")
      (libsource (lib "eagle-import") (part "M01PTH_SMD_3.25X0.85MM_NO_SILK"))
    )
    (comp (ref "JP1189")
      (value "M01PTH_SMD_3.25X0.85MM_NO_SILK")
      (footprint "eagle-import:1X01_SMD_3.25X0.85MM_NO_SILK")
      (libsource (lib "eagle-import") (part "M01PTH_SMD_3.25X0.85MM_NO_SILK"))
    )
    (comp (ref "JP1190")
      (value "M01PTH_SMD_3.25X0.85MM_NO_SILK")
      (footprint "eagle-import:1X01_SMD_3.25X0.85MM_NO_SILK")
      (libsource (lib "eagle-import") (part "M01PTH_SMD_3.25X0.85MM_NO_SILK"))
    )
    (comp (ref "JP1191")
      (value "M01PTH_SMD_3.25X0.85MM_NO_SILK")
      (footprint "eagle-import:1X01_SMD_3.25X0.85MM_NO_SILK")
      (libsource (lib "eagle-import") (part "M01PTH_SMD_3.25X0.85MM_NO_SILK"))
    )
    (comp (ref "JP1192")
      (value "M01PTH_SMD_3.25X0.85MM_NO_SILK")
      (footprint "eagle-import:1X01_SMD_3.25X0.85MM_NO_SILK")
      (libsource (lib "eagle-import") (part "M01PTH_SMD_3.25X0.85MM_NO_SILK"))
    )
    (comp (ref "JP1193")
      (value "M01PTH_SMD_3.25X0.85MM_NO_SILK")
      (footprint "eagle-import:1X01_SMD_3.25X0.85MM_NO_SILK")
      (libsource (lib "eagle-import") (part "M01PTH_SMD_3.25X0.85MM_NO_SILK"))
    )
    (comp (ref "JP1194")
      (value "M01PTH_SMD_3.25X0.85MM_NO_SILK")
      (footprint "eagle-import:1X01_SMD_3.25X0.85MM_NO_SILK")
      (libsource (lib "eagle-import") (part "M01PTH_SMD_3.25X0.85MM_NO_SILK"))
    )
    (comp (ref "JP1195")
      (value "M01PTH_SMD_3.25X0.85MM_NO_SILK")
      (footprint "eagle-import:1X01_SMD_3.25X0.85MM_NO_SILK")
      (libsource (lib "eagle-import") (part "M01PTH_SMD_3.25X0.85MM_NO_SILK"))
    )
    (comp (ref "JP1196")
      (value "M01PTH_SMD_3.25X0.85MM_NO_SILK")
      (footprint "eagle-import:1X01_SMD_3.25X0.85MM_NO_SILK")
      (libsource (lib "eagle-import") (part "M01PTH_SMD_3.25X0.85MM_NO_SILK"))
    )
    (comp (ref "JP1197")
      (value "M01PTH_SMD_3.25X0.85MM_NO_SILK")
      (footprint "eagle-import:1X01_SMD_3.25X0.85MM_NO_SILK")
      (libsource (lib "eagle-import") (part "M01PTH_SMD_3.25X0.85MM_NO_SILK"))
    )
    (comp (ref "JP1198")
      (value "M01PTH_SMD_3.25X0.85MM_NO_SILK")
      (footprint "eagle-import:1X01_SMD_3.25X0.85MM_NO_SILK")
      (libsource (lib "eagle-import") (part "M01PTH_SMD_3.25X0.85MM_NO_SILK"))
    )
    (comp (ref "JP1199")
      (value "M01PTH_SMD_3.25X0.85MM_NO_SILK")
      (footprint "eagle-import:1X01_SMD_3.25X0.85MM_NO_SILK")
      (libsource (lib "eagle-import") (part "M01PTH_SMD_3.25X0.85MM_NO_SILK"))
    )
    (comp (ref "JP1200")
      (value "M01PTH_SMD_3.25X0.85MM_NO_SILK")
      (footprint "eagle-import:1X01_SMD_3.25X0.85MM_NO_SILK")
      (libsource (lib "eagle-import") (part "M01PTH_SMD_3.25X0.85MM_NO_SILK"))
    )
  )
  (nets
    (net (code "1") (name "/0_1440127218") (class "Default")
      (node (ref "JP1") (pin "1") (pinfunction "1_1") (pintype "passive"))
      (node (ref "JP961") (pin "P$1") (pinfunction "1_P$1") (pintype "passive"))
    )
    (net (code "2") (name "/0_1440127248") (class "Default")
      (node (ref "JP10") (pin "1") (pinfunction "1_1") (pintype "passive"))
      (node (ref "JP1021") (pin "P$1") (pinfunction "1_P$1") (pintype "passive"))
    )
    (net (code "3") (name "/0_1440127317") (class "Default")
      (node (ref "JP1141") (pin "P$1") (pinfunction "1_P$1") (pintype "passive"))
      (node (ref "JP5") (pin "1") (pinfunction "1_1") (pintype "passive"))
    )
    (net (code "4") (name "/0_1440127347") (class "Default")
      (node (ref "JP1142") (pin "P$1") (pinfunction "1_P$1") (pintype "passive"))
      (node (ref "JP15") (pin "1") (pinfunction "1_1") (pintype "passive"))
    )
    (net (code "5") (name "/0_1440127366") (class "Default")
      (node (ref "JP1143") (pin "P$1") (pinfunction "1_P$1") (pintype "passive"))
      (node (ref "JP25") (pin "1") (pinfunction "1_1") (pintype "passive"))
    )
    (net (code "6") (name "/0_1440127382") (class "Default")
      (node (ref "JP1144") (pin "P$1") (pinfunction "1_P$1") (pintype "passive"))
      (node (ref "JP35") (pin "1") (pinfunction "1_1") (pintype "passive"))
    )
    (net (code "7") (name "/0_1440127392") (class "Default")
      (node (ref "JP1145") (pin "P$1") (pinfunction "1_P$1") (pintype "passive"))
      (node (ref "JP45") (pin "1") (pinfunction "1_1") (pintype "passive"))
    )
    (net (code "8") (name "/0_1440127421") (class "Default")
      (node (ref "JP1146") (pin "P$1") (pinfunction "1_P$1") (pintype "passive"))
      (node (ref "JP55") (pin "1") (pinfunction "1_1") (pintype "passive"))
    )
    (net (code "9") (name "/0_1440127430") (class "Default")
      (node (ref "JP1147") (pin "P$1") (pinfunction "1_P$1") (pintype "passive"))
      (node (ref "JP65") (pin "1") (pinfunction "1_1") (pintype "passive"))
    )
    (net (code "10") (name "/0_1440127608") (class "Default")
      (node (ref "JP1148") (pin "P$1") (pinfunction "1_P$1") (pintype "passive"))
      (node (ref "JP75") (pin "1") (pinfunction "1_1") (pintype "passive"))
    )
    (net (code "11") (name "/0_1440127617") (class "Default")
      (node (ref "JP1149") (pin "P$1") (pinfunction "1_P$1") (pintype "passive"))
      (node (ref "JP85") (pin "1") (pinfunction "1_1") (pintype "passive"))
    )
    (net (code "12") (name "/0_1440127627") (class "Default")
      (node (ref "JP1150") (pin "P$1") (pinfunction "1_P$1") (pintype "passive"))
      (node (ref "JP95") (pin "1") (pinfunction "1_1") (pintype "passive"))
    )
    (net (code "13") (name "/0_1440127700") (class "Default")
      (node (ref "JP105") (pin "1") (pinfunction "1_1") (pintype "passive"))
      (node (ref "JP1151") (pin "P$1") (pinfunction "1_P$1") (pintype "passive"))
    )
    (net (code "14") (name "/0_1440127712") (class "Default")
      (node (ref "JP115") (pin "1") (pinfunction "1_1") (pintype "passive"))
      (node (ref "JP1152") (pin "P$1") (pinfunction "1_P$1") (pintype "passive"))
    )
    (net (code "15") (name "/0_1440127720") (class "Default")
      (node (ref "JP1153") (pin "P$1") (pinfunction "1_P$1") (pintype "passive"))
      (node (ref "JP125") (pin "1") (pinfunction "1_1") (pintype "passive"))
    )
    (net (code "16") (name "/0_1440127729") (class "Default")
      (node (ref "JP1154") (pin "P$1") (pinfunction "1_P$1") (pintype "passive"))
      (node (ref "JP135") (pin "1") (pinfunction "1_1") (pintype "passive"))
    )
    (net (code "17") (name "/0_1440127744") (class "Default")
      (node (ref "JP1155") (pin "P$1") (pinfunction "1_P$1") (pintype "passive"))
      (node (ref "JP145") (pin "1") (pinfunction "1_1") (pintype "passive"))
    )
    (net (code "18") (name "/0_1440127816") (class "Default")
      (node (ref "JP1156") (pin "P$1") (pinfunction "1_P$1") (pintype "passive"))
      (node (ref "JP155") (pin "1") (pinfunction "1_1") (pintype "passive"))
    )
    (net (code "19") (name "/0_1440127828") (class "Default")
      (node (ref "JP1157") (pin "P$1") (pinfunction "1_P$1") (pintype "passive"))
      (node (ref "JP165") (pin "1") (pinfunction "1_1") (pintype "passive"))
    )
    (net (code "20") (name "/0_1440127838") (class "Default")
      (node (ref "JP1158") (pin "P$1") (pinfunction "1_P$1") (pintype "passive"))
      (node (ref "JP175") (pin "1") (pinfunction "1_1") (pintype "passive"))
    )
    (net (code "21") (name "/0_1440127850") (class "Default")
      (node (ref "JP1159") (pin "P$1") (pinfunction "1_P$1") (pintype "passive"))
      (node (ref "JP185") (pin "1") (pinfunction "1_1") (pintype "passive"))
    )
    (net (code "22") (name "/0_1440127870") (class "Default")
      (node (ref "JP1160") (pin "P$1") (pinfunction "1_P$1") (pintype "passive"))
      (node (ref "JP195") (pin "1") (pinfunction "1_1") (pintype "passive"))
    )
    (net (code "23") (name "/0_1440127904") (class "Default")
      (node (ref "JP1181") (pin "P$1") (pinfunction "1_P$1") (pintype "passive"))
      (node (ref "JP295") (pin "1") (pinfunction "1_1") (pintype "passive"))
    )
    (net (code "24") (name "/0_1440127914") (class "Default")
      (node (ref "JP1182") (pin "P$1") (pinfunction "1_P$1") (pintype "passive"))
      (node (ref "JP285") (pin "1") (pinfunction "1_1") (pintype "passive"))
    )
    (net (code "25") (name "/0_1440127944") (class "Default")
      (node (ref "JP1183") (pin "P$1") (pinfunction "1_P$1") (pintype "passive"))
      (node (ref "JP275") (pin "1") (pinfunction "1_1") (pintype "passive"))
    )
    (net (code "26") (name "/0_1440127955") (class "Default")
      (node (ref "JP1184") (pin "P$1") (pinfunction "1_P$1") (pintype "passive"))
      (node (ref "JP265") (pin "1") (pinfunction "1_1") (pintype "passive"))
    )
    (net (code "27") (name "/0_1440128006") (class "Default")
      (node (ref "JP1185") (pin "P$1") (pinfunction "1_P$1") (pintype "passive"))
      (node (ref "JP255") (pin "1") (pinfunction "1_1") (pintype "passive"))
    )
    (net (code "28") (name "/0_1440128015") (class "Default")
      (node (ref "JP1186") (pin "P$1") (pinfunction "1_P$1") (pintype "passive"))
      (node (ref "JP245") (pin "1") (pinfunction "1_1") (pintype "passive"))
    )
    (net (code "29") (name "/0_1440128025") (class "Default")
      (node (ref "JP1187") (pin "P$1") (pinfunction "1_P$1") (pintype "passive"))
      (node (ref "JP235") (pin "1") (pinfunction "1_1") (pintype "passive"))
    )
    (net (code "30") (name "/0_1440128039") (class "Default")
      (node (ref "JP1188") (pin "P$1") (pinfunction "1_P$1") (pintype "passive"))
      (node (ref "JP225") (pin "1") (pinfunction "1_1") (pintype "passive"))
    )
    (net (code "31") (name "/0_1440128052") (class "Default")
      (node (ref "JP1189") (pin "P$1") (pinfunction "1_P$1") (pintype "passive"))
      (node (ref "JP215") (pin "1") (pinfunction "1_1") (pintype "passive"))
    )
    (net (code "32") (name "/0_1440128062") (class "Default")
      (node (ref "JP1190") (pin "P$1") (pinfunction "1_P$1") (pintype "passive"))
      (node (ref "JP205") (pin "1") (pinfunction "1_1") (pintype "passive"))
    )
    (net (code "33") (name "/0_1440128088") (class "Default")
      (node (ref "JP1170") (pin "P$1") (pinfunction "1_P$1") (pintype "passive"))
      (node (ref "JP6") (pin "1") (pinfunction "1_1") (pintype "passive"))
    )
    (net (code "34") (name "/0_1440128098") (class "Default")
      (node (ref "JP1169") (pin "P$1") (pinfunction "1_P$1") (pintype "passive"))
      (node (ref "JP16") (pin "1") (pinfunction "1_1") (pintype "passive"))
    )
    (net (code "35") (name "/0_1440128106") (class "Default")
      (node (ref "JP1168") (pin "P$1") (pinfunction "1_P$1") (pintype "passive"))
      (node (ref "JP26") (pin "1") (pinfunction "1_1") (pintype "passive"))
    )
    (net (code "36") (name "/0_1440128116") (class "Default")
      (node (ref "JP1167") (pin "P$1") (pinfunction "1_P$1") (pintype "passive"))
      (node (ref "JP36") (pin "1") (pinfunction "1_1") (pintype "passive"))
    )
    (net (code "37") (name "/0_1440128126") (class "Default")
      (node (ref "JP1166") (pin "P$1") (pinfunction "1_P$1") (pintype "passive"))
      (node (ref "JP46") (pin "1") (pinfunction "1_1") (pintype "passive"))
    )
    (net (code "38") (name "/0_1440128135") (class "Default")
      (node (ref "JP1165") (pin "P$1") (pinfunction "1_P$1") (pintype "passive"))
      (node (ref "JP56") (pin "1") (pinfunction "1_1") (pintype "passive"))
    )
    (net (code "39") (name "/0_1440128149") (class "Default")
      (node (ref "JP1164") (pin "P$1") (pinfunction "1_P$1") (pintype "passive"))
      (node (ref "JP66") (pin "1") (pinfunction "1_1") (pintype "passive"))
    )
    (net (code "40") (name "/0_1440128159") (class "Default")
      (node (ref "JP1163") (pin "P$1") (pinfunction "1_P$1") (pintype "passive"))
      (node (ref "JP76") (pin "1") (pinfunction "1_1") (pintype "passive"))
    )
    (net (code "41") (name "/0_1440128167") (class "Default")
      (node (ref "JP1162") (pin "P$1") (pinfunction "1_P$1") (pintype "passive"))
      (node (ref "JP86") (pin "1") (pinfunction "1_1") (pintype "passive"))
    )
    (net (code "42") (name "/0_1440128175") (class "Default")
      (node (ref "JP1161") (pin "P$1") (pinfunction "1_P$1") (pintype "passive"))
      (node (ref "JP96") (pin "1") (pinfunction "1_1") (pintype "passive"))
    )
    (net (code "43") (name "/0_1440128223") (class "Default")
      (node (ref "JP106") (pin "1") (pinfunction "1_1") (pintype "passive"))
      (node (ref "JP1180") (pin "P$1") (pinfunction "1_P$1") (pintype "passive"))
    )
    (net (code "44") (name "/0_1440128233") (class "Default")
      (node (ref "JP116") (pin "1") (pinfunction "1_1") (pintype "passive"))
      (node (ref "JP1179") (pin "P$1") (pinfunction "1_P$1") (pintype "passive"))
    )
    (net (code "45") (name "/0_1440128243") (class "Default")
      (node (ref "JP1178") (pin "P$1") (pinfunction "1_P$1") (pintype "passive"))
      (node (ref "JP126") (pin "1") (pinfunction "1_1") (pintype "passive"))
    )
    (net (code "46") (name "/0_1440128252") (class "Default")
      (node (ref "JP1177") (pin "P$1") (pinfunction "1_P$1") (pintype "passive"))
      (node (ref "JP136") (pin "1") (pinfunction "1_1") (pintype "passive"))
    )
    (net (code "47") (name "/0_1440128264") (class "Default")
      (node (ref "JP1176") (pin "P$1") (pinfunction "1_P$1") (pintype "passive"))
      (node (ref "JP146") (pin "1") (pinfunction "1_1") (pintype "passive"))
    )
    (net (code "48") (name "/0_1440128275") (class "Default")
      (node (ref "JP1175") (pin "P$1") (pinfunction "1_P$1") (pintype "passive"))
      (node (ref "JP156") (pin "1") (pinfunction "1_1") (pintype "passive"))
    )
    (net (code "49") (name "/0_1440128290") (class "Default")
      (node (ref "JP1174") (pin "P$1") (pinfunction "1_P$1") (pintype "passive"))
      (node (ref "JP166") (pin "1") (pinfunction "1_1") (pintype "passive"))
    )
    (net (code "50") (name "/0_1440128302") (class "Default")
      (node (ref "JP1173") (pin "P$1") (pinfunction "1_P$1") (pintype "passive"))
      (node (ref "JP176") (pin "1") (pinfunction "1_1") (pintype "passive"))
    )
    (net (code "51") (name "/0_1440128314") (class "Default")
      (node (ref "JP1172") (pin "P$1") (pinfunction "1_P$1") (pintype "passive"))
      (node (ref "JP186") (pin "1") (pinfunction "1_1") (pintype "passive"))
    )
    (net (code "52") (name "/0_1440128326") (class "Default")
      (node (ref "JP1171") (pin "P$1") (pinfunction "1_P$1") (pintype "passive"))
      (node (ref "JP196") (pin "1") (pinfunction "1_1") (pintype "passive"))
    )
    (net (code "53") (name "/0_1440128344") (class "Default")
      (node (ref "JP1200") (pin "P$1") (pinfunction "1_P$1") (pintype "passive"))
      (node (ref "JP296") (pin "1") (pinfunction "1_1") (pintype "passive"))
    )
    (net (code "54") (name "/0_1440128353") (class "Default")
      (node (ref "JP1199") (pin "P$1") (pinfunction "1_P$1") (pintype "passive"))
      (node (ref "JP286") (pin "1") (pinfunction "1_1") (pintype "passive"))
    )
    (net (code "55") (name "/0_1440128363") (class "Default")
      (node (ref "JP1198") (pin "P$1") (pinfunction "1_P$1") (pintype "passive"))
      (node (ref "JP276") (pin "1") (pinfunction "1_1") (pintype "passive"))
    )
    (net (code "56") (name "/0_1440128375") (class "Default")
      (node (ref "JP1197") (pin "P$1") (pinfunction "1_P$1") (pintype "passive"))
      (node (ref "JP266") (pin "1") (pinfunction "1_1") (pintype "passive"))
    )
    (net (code "57") (name "/0_1440128386") (class "Default")
      (node (ref "JP1196") (pin "P$1") (pinfunction "1_P$1") (pintype "passive"))
      (node (ref "JP256") (pin "1") (pinfunction "1_1") (pintype "passive"))
    )
    (net (code "58") (name "/0_1440128396") (class "Default")
      (node (ref "JP1195") (pin "P$1") (pinfunction "1_P$1") (pintype "passive"))
      (node (ref "JP246") (pin "1") (pinfunction "1_1") (pintype "passive"))
    )
    (net (code "59") (name "/0_1440128405") (class "Default")
      (node (ref "JP1194") (pin "P$1") (pinfunction "1_P$1") (pintype "passive"))
      (node (ref "JP236") (pin "1") (pinfunction "1_1") (pintype "passive"))
    )
    (net (code "60") (name "/0_1440128414") (class "Default")
      (node (ref "JP1193") (pin "P$1") (pinfunction "1_P$1") (pintype "passive"))
      (node (ref "JP226") (pin "1") (pinfunction "1_1") (pintype "passive"))
    )
    (net (code "61") (name "/0_1440128424") (class "Default")
      (node (ref "JP1192") (pin "P$1") (pinfunction "1_P$1") (pintype "passive"))
      (node (ref "JP216") (pin "1") (pinfunction "1_1") (pintype "passive"))
    )
    (net (code "62") (name "/0_1440128432") (class "Default")
      (node (ref "JP1191") (pin "P$1") (pinfunction "1_P$1") (pintype "passive"))
      (node (ref "JP206") (pin "1") (pinfunction "1_1") (pintype "passive"))
    )
    (net (code "63") (name "/1_1440127218") (class "Default")
      (node (ref "JP11") (pin "1") (pinfunction "1_1") (pintype "passive"))
      (node (ref "JP963") (pin "P$1") (pinfunction "1_P$1") (pintype "passive"))
    )
    (net (code "64") (name "/1_1440127248") (class "Default")
      (node (ref "JP1023") (pin "P$1") (pinfunction "1_P$1") (pintype "passive"))
      (node (ref "JP20") (pin "1") (pinfunction "1_1") (pintype "passive"))
    )
    (net (code "65") (name "/2_1440127218") (class "Default")
      (node (ref "JP21") (pin "1") (pinfunction "1_1") (pintype "passive"))
      (node (ref "JP965") (pin "P$1") (pinfunction "1_P$1") (pintype "passive"))
    )
    (net (code "66") (name "/2_1440127248") (class "Default")
      (node (ref "JP1025") (pin "P$1") (pinfunction "1_P$1") (pintype "passive"))
      (node (ref "JP30") (pin "1") (pinfunction "1_1") (pintype "passive"))
    )
    (net (code "67") (name "/3_1440127218") (class "Default")
      (node (ref "JP31") (pin "1") (pinfunction "1_1") (pintype "passive"))
      (node (ref "JP967") (pin "P$1") (pinfunction "1_P$1") (pintype "passive"))
    )
    (net (code "68") (name "/3_1440127248") (class "Default")
      (node (ref "JP1027") (pin "P$1") (pinfunction "1_P$1") (pintype "passive"))
      (node (ref "JP40") (pin "1") (pinfunction "1_1") (pintype "passive"))
    )
    (net (code "69") (name "/4_1440127218") (class "Default")
      (node (ref "JP41") (pin "1") (pinfunction "1_1") (pintype "passive"))
      (node (ref "JP969") (pin "P$1") (pinfunction "1_P$1") (pintype "passive"))
    )
    (net (code "70") (name "/4_1440127248") (class "Default")
      (node (ref "JP1029") (pin "P$1") (pinfunction "1_P$1") (pintype "passive"))
      (node (ref "JP50") (pin "1") (pinfunction "1_1") (pintype "passive"))
    )
    (net (code "71") (name "/5_1440127218") (class "Default")
      (node (ref "JP51") (pin "1") (pinfunction "1_1") (pintype "passive"))
      (node (ref "JP971") (pin "P$1") (pinfunction "1_P$1") (pintype "passive"))
    )
    (net (code "72") (name "/5_1440127248") (class "Default")
      (node (ref "JP1031") (pin "P$1") (pinfunction "1_P$1") (pintype "passive"))
      (node (ref "JP60") (pin "1") (pinfunction "1_1") (pintype "passive"))
    )
    (net (code "73") (name "/6_1440127218") (class "Default")
      (node (ref "JP61") (pin "1") (pinfunction "1_1") (pintype "passive"))
      (node (ref "JP973") (pin "P$1") (pinfunction "1_P$1") (pintype "passive"))
    )
    (net (code "74") (name "/6_1440127248") (class "Default")
      (node (ref "JP1033") (pin "P$1") (pinfunction "1_P$1") (pintype "passive"))
      (node (ref "JP70") (pin "1") (pinfunction "1_1") (pintype "passive"))
    )
    (net (code "75") (name "/7_1440127218") (class "Default")
      (node (ref "JP71") (pin "1") (pinfunction "1_1") (pintype "passive"))
      (node (ref "JP975") (pin "P$1") (pinfunction "1_P$1") (pintype "passive"))
    )
    (net (code "76") (name "/7_1440127248") (class "Default")
      (node (ref "JP1035") (pin "P$1") (pinfunction "1_P$1") (pintype "passive"))
      (node (ref "JP80") (pin "1") (pinfunction "1_1") (pintype "passive"))
    )
    (net (code "77") (name "/8_1440127218") (class "Default")
      (node (ref "JP81") (pin "1") (pinfunction "1_1") (pintype "passive"))
      (node (ref "JP977") (pin "P$1") (pinfunction "1_P$1") (pintype "passive"))
    )
    (net (code "78") (name "/8_1440127248") (class "Default")
      (node (ref "JP1037") (pin "P$1") (pinfunction "1_P$1") (pintype "passive"))
      (node (ref "JP90") (pin "1") (pinfunction "1_1") (pintype "passive"))
    )
    (net (code "79") (name "/9_1440127218") (class "Default")
      (node (ref "JP91") (pin "1") (pinfunction "1_1") (pintype "passive"))
      (node (ref "JP979") (pin "P$1") (pinfunction "1_P$1") (pintype "passive"))
    )
    (net (code "80") (name "/9_1440127248") (class "Default")
      (node (ref "JP100") (pin "1") (pinfunction "1_1") (pintype "passive"))
      (node (ref "JP1039") (pin "P$1") (pinfunction "1_P$1") (pintype "passive"))
    )
    (net (code "81") (name "/10_1440127218") (class "Default")
      (node (ref "JP101") (pin "1") (pinfunction "1_1") (pintype "passive"))
      (node (ref "JP981") (pin "P$1") (pinfunction "1_P$1") (pintype "passive"))
    )
    (net (code "82") (name "/10_1440127248") (class "Default")
      (node (ref "JP1041") (pin "P$1") (pinfunction "1_P$1") (pintype "passive"))
      (node (ref "JP110") (pin "1") (pinfunction "1_1") (pintype "passive"))
    )
    (net (code "83") (name "/11_1440127218") (class "Default")
      (node (ref "JP111") (pin "1") (pinfunction "1_1") (pintype "passive"))
      (node (ref "JP983") (pin "P$1") (pinfunction "1_P$1") (pintype "passive"))
    )
    (net (code "84") (name "/11_1440127248") (class "Default")
      (node (ref "JP1043") (pin "P$1") (pinfunction "1_P$1") (pintype "passive"))
      (node (ref "JP120") (pin "1") (pinfunction "1_1") (pintype "passive"))
    )
    (net (code "85") (name "/12_1440127218") (class "Default")
      (node (ref "JP121") (pin "1") (pinfunction "1_1") (pintype "passive"))
      (node (ref "JP985") (pin "P$1") (pinfunction "1_P$1") (pintype "passive"))
    )
    (net (code "86") (name "/12_1440127248") (class "Default")
      (node (ref "JP1045") (pin "P$1") (pinfunction "1_P$1") (pintype "passive"))
      (node (ref "JP130") (pin "1") (pinfunction "1_1") (pintype "passive"))
    )
    (net (code "87") (name "/13_1440127218") (class "Default")
      (node (ref "JP131") (pin "1") (pinfunction "1_1") (pintype "passive"))
      (node (ref "JP987") (pin "P$1") (pinfunction "1_P$1") (pintype "passive"))
    )
    (net (code "88") (name "/13_1440127248") (class "Default")
      (node (ref "JP1047") (pin "P$1") (pinfunction "1_P$1") (pintype "passive"))
      (node (ref "JP140") (pin "1") (pinfunction "1_1") (pintype "passive"))
    )
    (net (code "89") (name "/14_1440127218") (class "Default")
      (node (ref "JP141") (pin "1") (pinfunction "1_1") (pintype "passive"))
      (node (ref "JP989") (pin "P$1") (pinfunction "1_P$1") (pintype "passive"))
    )
    (net (code "90") (name "/14_1440127248") (class "Default")
      (node (ref "JP1049") (pin "P$1") (pinfunction "1_P$1") (pintype "passive"))
      (node (ref "JP150") (pin "1") (pinfunction "1_1") (pintype "passive"))
    )
    (net (code "91") (name "/15_1440127218") (class "Default")
      (node (ref "JP151") (pin "1") (pinfunction "1_1") (pintype "passive"))
      (node (ref "JP991") (pin "P$1") (pinfunction "1_P$1") (pintype "passive"))
    )
    (net (code "92") (name "/15_1440127248") (class "Default")
      (node (ref "JP1051") (pin "P$1") (pinfunction "1_P$1") (pintype "passive"))
      (node (ref "JP160") (pin "1") (pinfunction "1_1") (pintype "passive"))
    )
    (net (code "93") (name "/16_1440127218") (class "Default")
      (node (ref "JP161") (pin "1") (pinfunction "1_1") (pintype "passive"))
      (node (ref "JP993") (pin "P$1") (pinfunction "1_P$1") (pintype "passive"))
    )
    (net (code "94") (name "/16_1440127248") (class "Default")
      (node (ref "JP1053") (pin "P$1") (pinfunction "1_P$1") (pintype "passive"))
      (node (ref "JP170") (pin "1") (pinfunction "1_1") (pintype "passive"))
    )
    (net (code "95") (name "/17_1440127218") (class "Default")
      (node (ref "JP171") (pin "1") (pinfunction "1_1") (pintype "passive"))
      (node (ref "JP995") (pin "P$1") (pinfunction "1_P$1") (pintype "passive"))
    )
    (net (code "96") (name "/17_1440127248") (class "Default")
      (node (ref "JP1055") (pin "P$1") (pinfunction "1_P$1") (pintype "passive"))
      (node (ref "JP180") (pin "1") (pinfunction "1_1") (pintype "passive"))
    )
    (net (code "97") (name "/18_1440127218") (class "Default")
      (node (ref "JP181") (pin "1") (pinfunction "1_1") (pintype "passive"))
      (node (ref "JP997") (pin "P$1") (pinfunction "1_P$1") (pintype "passive"))
    )
    (net (code "98") (name "/18_1440127248") (class "Default")
      (node (ref "JP1057") (pin "P$1") (pinfunction "1_P$1") (pintype "passive"))
      (node (ref "JP190") (pin "1") (pinfunction "1_1") (pintype "passive"))
    )
    (net (code "99") (name "/19_1440127218") (class "Default")
      (node (ref "JP191") (pin "1") (pinfunction "1_1") (pintype "passive"))
      (node (ref "JP999") (pin "P$1") (pinfunction "1_P$1") (pintype "passive"))
    )
    (net (code "100") (name "/19_1440127248") (class "Default")
      (node (ref "JP1059") (pin "P$1") (pinfunction "1_P$1") (pintype "passive"))
      (node (ref "JP200") (pin "1") (pinfunction "1_1") (pintype "passive"))
    )
    (net (code "101") (name "/20_1440127218") (class "Default")
      (node (ref "JP1001") (pin "P$1") (pinfunction "1_P$1") (pintype "passive"))
      (node (ref "JP201") (pin "1") (pinfunction "1_1") (pintype "passive"))
    )
    (net (code "102") (name "/20_1440127248") (class "Default")
      (node (ref "JP1061") (pin "P$1") (pinfunction "1_P$1") (pintype "passive"))
      (node (ref "JP210") (pin "1") (pinfunction "1_1") (pintype "passive"))
    )
    (net (code "103") (name "/21_1440127218") (class "Default")
      (node (ref "JP1003") (pin "P$1") (pinfunction "1_P$1") (pintype "passive"))
      (node (ref "JP211") (pin "1") (pinfunction "1_1") (pintype "passive"))
    )
    (net (code "104") (name "/21_1440127248") (class "Default")
      (node (ref "JP1063") (pin "P$1") (pinfunction "1_P$1") (pintype "passive"))
      (node (ref "JP220") (pin "1") (pinfunction "1_1") (pintype "passive"))
    )
    (net (code "105") (name "/22_1440127218") (class "Default")
      (node (ref "JP1005") (pin "P$1") (pinfunction "1_P$1") (pintype "passive"))
      (node (ref "JP221") (pin "1") (pinfunction "1_1") (pintype "passive"))
    )
    (net (code "106") (name "/22_1440127248") (class "Default")
      (node (ref "JP1065") (pin "P$1") (pinfunction "1_P$1") (pintype "passive"))
      (node (ref "JP230") (pin "1") (pinfunction "1_1") (pintype "passive"))
    )
    (net (code "107") (name "/23_1440127218") (class "Default")
      (node (ref "JP1007") (pin "P$1") (pinfunction "1_P$1") (pintype "passive"))
      (node (ref "JP231") (pin "1") (pinfunction "1_1") (pintype "passive"))
    )
    (net (code "108") (name "/23_1440127248") (class "Default")
      (node (ref "JP1067") (pin "P$1") (pinfunction "1_P$1") (pintype "passive"))
      (node (ref "JP240") (pin "1") (pinfunction "1_1") (pintype "passive"))
    )
    (net (code "109") (name "/24_1440127218") (class "Default")
      (node (ref "JP1009") (pin "P$1") (pinfunction "1_P$1") (pintype "passive"))
      (node (ref "JP241") (pin "1") (pinfunction "1_1") (pintype "passive"))
    )
    (net (code "110") (name "/24_1440127248") (class "Default")
      (node (ref "JP1069") (pin "P$1") (pinfunction "1_P$1") (pintype "passive"))
      (node (ref "JP250") (pin "1") (pinfunction "1_1") (pintype "passive"))
    )
    (net (code "111") (name "/25_1440127218") (class "Default")
      (node (ref "JP1011") (pin "P$1") (pinfunction "1_P$1") (pintype "passive"))
      (node (ref "JP251") (pin "1") (pinfunction "1_1") (pintype "passive"))
    )
    (net (code "112") (name "/25_1440127248") (class "Default")
      (node (ref "JP1071") (pin "P$1") (pinfunction "1_P$1") (pintype "passive"))
      (node (ref "JP260") (pin "1") (pinfunction "1_1") (pintype "passive"))
    )
    (net (code "113") (name "/26_1440127218") (class "Default")
      (node (ref "JP1013") (pin "P$1") (pinfunction "1_P$1") (pintype "passive"))
      (node (ref "JP261") (pin "1") (pinfunction "1_1") (pintype "passive"))
    )
    (net (code "114") (name "/26_1440127248") (class "Default")
      (node (ref "JP1073") (pin "P$1") (pinfunction "1_P$1") (pintype "passive"))
      (node (ref "JP270") (pin "1") (pinfunction "1_1") (pintype "passive"))
    )
    (net (code "115") (name "/27_1440127218") (class "Default")
      (node (ref "JP1015") (pin "P$1") (pinfunction "1_P$1") (pintype "passive"))
      (node (ref "JP271") (pin "1") (pinfunction "1_1") (pintype "passive"))
    )
    (net (code "116") (name "/27_1440127248") (class "Default")
      (node (ref "JP1075") (pin "P$1") (pinfunction "1_P$1") (pintype "passive"))
      (node (ref "JP280") (pin "1") (pinfunction "1_1") (pintype "passive"))
    )
    (net (code "117") (name "/28_1440127218") (class "Default")
      (node (ref "JP1017") (pin "P$1") (pinfunction "1_P$1") (pintype "passive"))
      (node (ref "JP281") (pin "1") (pinfunction "1_1") (pintype "passive"))
    )
    (net (code "118") (name "/28_1440127248") (class "Default")
      (node (ref "JP1077") (pin "P$1") (pinfunction "1_P$1") (pintype "passive"))
      (node (ref "JP290") (pin "1") (pinfunction "1_1") (pintype "passive"))
    )
    (net (code "119") (name "/29_1440127218") (class "Default")
      (node (ref "JP1019") (pin "P$1") (pinfunction "1_P$1") (pintype "passive"))
      (node (ref "JP291") (pin "1") (pinfunction "1_1") (pintype "passive"))
    )
    (net (code "120") (name "/29_1440127248") (class "Default")
      (node (ref "JP1079") (pin "P$1") (pinfunction "1_P$1") (pintype "passive"))
      (node (ref "JP300") (pin "1") (pinfunction "1_1") (pintype "passive"))
    )
    (net (code "121") (name "/30_1440127218") (class "Default")
      (node (ref "JP1020") (pin "P$1") (pinfunction "1_P$1") (pintype "passive"))
      (node (ref "JP292") (pin "1") (pinfunction "1_1") (pintype "passive"))
    )
    (net (code "122") (name "/30_1440127248") (class "Default")
      (node (ref "JP1080") (pin "P$1") (pinfunction "1_P$1") (pintype "passive"))
      (node (ref "JP299") (pin "1") (pinfunction "1_1") (pintype "passive"))
    )
    (net (code "123") (name "/31_1440127218") (class "Default")
      (node (ref "JP2") (pin "1") (pinfunction "1_1") (pintype "passive"))
      (node (ref "JP962") (pin "P$1") (pinfunction "1_P$1") (pintype "passive"))
    )
    (net (code "124") (name "/31_1440127248") (class "Default")
      (node (ref "JP1022") (pin "P$1") (pinfunction "1_P$1") (pintype "passive"))
      (node (ref "JP9") (pin "1") (pinfunction "1_1") (pintype "passive"))
    )
    (net (code "125") (name "/32_1440127218") (class "Default")
      (node (ref "JP12") (pin "1") (pinfunction "1_1") (pintype "passive"))
      (node (ref "JP964") (pin "P$1") (pinfunction "1_P$1") (pintype "passive"))
    )
    (net (code "126") (name "/32_1440127248") (class "Default")
      (node (ref "JP1024") (pin "P$1") (pinfunction "1_P$1") (pintype "passive"))
      (node (ref "JP19") (pin "1") (pinfunction "1_1") (pintype "passive"))
    )
    (net (code "127") (name "/33_1440127218") (class "Default")
      (node (ref "JP22") (pin "1") (pinfunction "1_1") (pintype "passive"))
      (node (ref "JP966") (pin "P$1") (pinfunction "1_P$1") (pintype "passive"))
    )
    (net (code "128") (name "/33_1440127248") (class "Default")
      (node (ref "JP1026") (pin "P$1") (pinfunction "1_P$1") (pintype "passive"))
      (node (ref "JP29") (pin "1") (pinfunction "1_1") (pintype "passive"))
    )
    (net (code "129") (name "/34_1440127218") (class "Default")
      (node (ref "JP32") (pin "1") (pinfunction "1_1") (pintype "passive"))
      (node (ref "JP968") (pin "P$1") (pinfunction "1_P$1") (pintype "passive"))
    )
    (net (code "130") (name "/34_1440127248") (class "Default")
      (node (ref "JP1028") (pin "P$1") (pinfunction "1_P$1") (pintype "passive"))
      (node (ref "JP39") (pin "1") (pinfunction "1_1") (pintype "passive"))
    )
    (net (code "131") (name "/35_1440127218") (class "Default")
      (node (ref "JP42") (pin "1") (pinfunction "1_1") (pintype "passive"))
      (node (ref "JP970") (pin "P$1") (pinfunction "1_P$1") (pintype "passive"))
    )
    (net (code "132") (name "/35_1440127248") (class "Default")
      (node (ref "JP1030") (pin "P$1") (pinfunction "1_P$1") (pintype "passive"))
      (node (ref "JP49") (pin "1") (pinfunction "1_1") (pintype "passive"))
    )
    (net (code "133") (name "/36_1440127218") (class "Default")
      (node (ref "JP52") (pin "1") (pinfunction "1_1") (pintype "passive"))
      (node (ref "JP972") (pin "P$1") (pinfunction "1_P$1") (pintype "passive"))
    )
    (net (code "134") (name "/36_1440127248") (class "Default")
      (node (ref "JP1032") (pin "P$1") (pinfunction "1_P$1") (pintype "passive"))
      (node (ref "JP59") (pin "1") (pinfunction "1_1") (pintype "passive"))
    )
    (net (code "135") (name "/37_1440127218") (class "Default")
      (node (ref "JP62") (pin "1") (pinfunction "1_1") (pintype "passive"))
      (node (ref "JP974") (pin "P$1") (pinfunction "1_P$1") (pintype "passive"))
    )
    (net (code "136") (name "/37_1440127248") (class "Default")
      (node (ref "JP1034") (pin "P$1") (pinfunction "1_P$1") (pintype "passive"))
      (node (ref "JP69") (pin "1") (pinfunction "1_1") (pintype "passive"))
    )
    (net (code "137") (name "/38_1440127218") (class "Default")
      (node (ref "JP72") (pin "1") (pinfunction "1_1") (pintype "passive"))
      (node (ref "JP976") (pin "P$1") (pinfunction "1_P$1") (pintype "passive"))
    )
    (net (code "138") (name "/38_1440127248") (class "Default")
      (node (ref "JP1036") (pin "P$1") (pinfunction "1_P$1") (pintype "passive"))
      (node (ref "JP79") (pin "1") (pinfunction "1_1") (pintype "passive"))
    )
    (net (code "139") (name "/39_1440127218") (class "Default")
      (node (ref "JP82") (pin "1") (pinfunction "1_1") (pintype "passive"))
      (node (ref "JP978") (pin "P$1") (pinfunction "1_P$1") (pintype "passive"))
    )
    (net (code "140") (name "/39_1440127248") (class "Default")
      (node (ref "JP1038") (pin "P$1") (pinfunction "1_P$1") (pintype "passive"))
      (node (ref "JP89") (pin "1") (pinfunction "1_1") (pintype "passive"))
    )
    (net (code "141") (name "/40_1440127218") (class "Default")
      (node (ref "JP92") (pin "1") (pinfunction "1_1") (pintype "passive"))
      (node (ref "JP980") (pin "P$1") (pinfunction "1_P$1") (pintype "passive"))
    )
    (net (code "142") (name "/40_1440127248") (class "Default")
      (node (ref "JP1040") (pin "P$1") (pinfunction "1_P$1") (pintype "passive"))
      (node (ref "JP99") (pin "1") (pinfunction "1_1") (pintype "passive"))
    )
    (net (code "143") (name "/41_1440127218") (class "Default")
      (node (ref "JP102") (pin "1") (pinfunction "1_1") (pintype "passive"))
      (node (ref "JP982") (pin "P$1") (pinfunction "1_P$1") (pintype "passive"))
    )
    (net (code "144") (name "/41_1440127248") (class "Default")
      (node (ref "JP1042") (pin "P$1") (pinfunction "1_P$1") (pintype "passive"))
      (node (ref "JP109") (pin "1") (pinfunction "1_1") (pintype "passive"))
    )
    (net (code "145") (name "/42_1440127218") (class "Default")
      (node (ref "JP112") (pin "1") (pinfunction "1_1") (pintype "passive"))
      (node (ref "JP984") (pin "P$1") (pinfunction "1_P$1") (pintype "passive"))
    )
    (net (code "146") (name "/42_1440127248") (class "Default")
      (node (ref "JP1044") (pin "P$1") (pinfunction "1_P$1") (pintype "passive"))
      (node (ref "JP119") (pin "1") (pinfunction "1_1") (pintype "passive"))
    )
    (net (code "147") (name "/43_1440127218") (class "Default")
      (node (ref "JP122") (pin "1") (pinfunction "1_1") (pintype "passive"))
      (node (ref "JP986") (pin "P$1") (pinfunction "1_P$1") (pintype "passive"))
    )
    (net (code "148") (name "/43_1440127248") (class "Default")
      (node (ref "JP1046") (pin "P$1") (pinfunction "1_P$1") (pintype "passive"))
      (node (ref "JP129") (pin "1") (pinfunction "1_1") (pintype "passive"))
    )
    (net (code "149") (name "/44_1440127218") (class "Default")
      (node (ref "JP132") (pin "1") (pinfunction "1_1") (pintype "passive"))
      (node (ref "JP988") (pin "P$1") (pinfunction "1_P$1") (pintype "passive"))
    )
    (net (code "150") (name "/44_1440127248") (class "Default")
      (node (ref "JP1048") (pin "P$1") (pinfunction "1_P$1") (pintype "passive"))
      (node (ref "JP139") (pin "1") (pinfunction "1_1") (pintype "passive"))
    )
    (net (code "151") (name "/45_1440127218") (class "Default")
      (node (ref "JP142") (pin "1") (pinfunction "1_1") (pintype "passive"))
      (node (ref "JP990") (pin "P$1") (pinfunction "1_P$1") (pintype "passive"))
    )
    (net (code "152") (name "/45_1440127248") (class "Default")
      (node (ref "JP1050") (pin "P$1") (pinfunction "1_P$1") (pintype "passive"))
      (node (ref "JP149") (pin "1") (pinfunction "1_1") (pintype "passive"))
    )
    (net (code "153") (name "/46_1440127218") (class "Default")
      (node (ref "JP152") (pin "1") (pinfunction "1_1") (pintype "passive"))
      (node (ref "JP992") (pin "P$1") (pinfunction "1_P$1") (pintype "passive"))
    )
    (net (code "154") (name "/46_1440127248") (class "Default")
      (node (ref "JP1052") (pin "P$1") (pinfunction "1_P$1") (pintype "passive"))
      (node (ref "JP159") (pin "1") (pinfunction "1_1") (pintype "passive"))
    )
    (net (code "155") (name "/47_1440127218") (class "Default")
      (node (ref "JP162") (pin "1") (pinfunction "1_1") (pintype "passive"))
      (node (ref "JP994") (pin "P$1") (pinfunction "1_P$1") (pintype "passive"))
    )
    (net (code "156") (name "/47_1440127248") (class "Default")
      (node (ref "JP1054") (pin "P$1") (pinfunction "1_P$1") (pintype "passive"))
      (node (ref "JP169") (pin "1") (pinfunction "1_1") (pintype "passive"))
    )
    (net (code "157") (name "/48_1440127218") (class "Default")
      (node (ref "JP172") (pin "1") (pinfunction "1_1") (pintype "passive"))
      (node (ref "JP996") (pin "P$1") (pinfunction "1_P$1") (pintype "passive"))
    )
    (net (code "158") (name "/48_1440127248") (class "Default")
      (node (ref "JP1056") (pin "P$1") (pinfunction "1_P$1") (pintype "passive"))
      (node (ref "JP179") (pin "1") (pinfunction "1_1") (pintype "passive"))
    )
    (net (code "159") (name "/49_1440127218") (class "Default")
      (node (ref "JP182") (pin "1") (pinfunction "1_1") (pintype "passive"))
      (node (ref "JP998") (pin "P$1") (pinfunction "1_P$1") (pintype "passive"))
    )
    (net (code "160") (name "/49_1440127248") (class "Default")
      (node (ref "JP1058") (pin "P$1") (pinfunction "1_P$1") (pintype "passive"))
      (node (ref "JP189") (pin "1") (pinfunction "1_1") (pintype "passive"))
    )
    (net (code "161") (name "/50_1440127218") (class "Default")
      (node (ref "JP1000") (pin "P$1") (pinfunction "1_P$1") (pintype "passive"))
      (node (ref "JP192") (pin "1") (pinfunction "1_1") (pintype "passive"))
    )
    (net (code "162") (name "/50_1440127248") (class "Default")
      (node (ref "JP1060") (pin "P$1") (pinfunction "1_P$1") (pintype "passive"))
      (node (ref "JP199") (pin "1") (pinfunction "1_1") (pintype "passive"))
    )
    (net (code "163") (name "/51_1440127218") (class "Default")
      (node (ref "JP1002") (pin "P$1") (pinfunction "1_P$1") (pintype "passive"))
      (node (ref "JP202") (pin "1") (pinfunction "1_1") (pintype "passive"))
    )
    (net (code "164") (name "/51_1440127248") (class "Default")
      (node (ref "JP1062") (pin "P$1") (pinfunction "1_P$1") (pintype "passive"))
      (node (ref "JP209") (pin "1") (pinfunction "1_1") (pintype "passive"))
    )
    (net (code "165") (name "/52_1440127218") (class "Default")
      (node (ref "JP1004") (pin "P$1") (pinfunction "1_P$1") (pintype "passive"))
      (node (ref "JP212") (pin "1") (pinfunction "1_1") (pintype "passive"))
    )
    (net (code "166") (name "/52_1440127248") (class "Default")
      (node (ref "JP1064") (pin "P$1") (pinfunction "1_P$1") (pintype "passive"))
      (node (ref "JP219") (pin "1") (pinfunction "1_1") (pintype "passive"))
    )
    (net (code "167") (name "/53_1440127218") (class "Default")
      (node (ref "JP1006") (pin "P$1") (pinfunction "1_P$1") (pintype "passive"))
      (node (ref "JP222") (pin "1") (pinfunction "1_1") (pintype "passive"))
    )
    (net (code "168") (name "/53_1440127248") (class "Default")
      (node (ref "JP1066") (pin "P$1") (pinfunction "1_P$1") (pintype "passive"))
      (node (ref "JP229") (pin "1") (pinfunction "1_1") (pintype "passive"))
    )
    (net (code "169") (name "/54_1440127218") (class "Default")
      (node (ref "JP1008") (pin "P$1") (pinfunction "1_P$1") (pintype "passive"))
      (node (ref "JP232") (pin "1") (pinfunction "1_1") (pintype "passive"))
    )
    (net (code "170") (name "/54_1440127248") (class "Default")
      (node (ref "JP1068") (pin "P$1") (pinfunction "1_P$1") (pintype "passive"))
      (node (ref "JP239") (pin "1") (pinfunction "1_1") (pintype "passive"))
    )
    (net (code "171") (name "/55_1440127218") (class "Default")
      (node (ref "JP1010") (pin "P$1") (pinfunction "1_P$1") (pintype "passive"))
      (node (ref "JP242") (pin "1") (pinfunction "1_1") (pintype "passive"))
    )
    (net (code "172") (name "/55_1440127248") (class "Default")
      (node (ref "JP1070") (pin "P$1") (pinfunction "1_P$1") (pintype "passive"))
      (node (ref "JP249") (pin "1") (pinfunction "1_1") (pintype "passive"))
    )
    (net (code "173") (name "/56_1440127218") (class "Default")
      (node (ref "JP1012") (pin "P$1") (pinfunction "1_P$1") (pintype "passive"))
      (node (ref "JP252") (pin "1") (pinfunction "1_1") (pintype "passive"))
    )
    (net (code "174") (name "/56_1440127248") (class "Default")
      (node (ref "JP1072") (pin "P$1") (pinfunction "1_P$1") (pintype "passive"))
      (node (ref "JP259") (pin "1") (pinfunction "1_1") (pintype "passive"))
    )
    (net (code "175") (name "/57_1440127218") (class "Default")
      (node (ref "JP1014") (pin "P$1") (pinfunction "1_P$1") (pintype "passive"))
      (node (ref "JP262") (pin "1") (pinfunction "1_1") (pintype "passive"))
    )
    (net (code "176") (name "/57_1440127248") (class "Default")
      (node (ref "JP1074") (pin "P$1") (pinfunction "1_P$1") (pintype "passive"))
      (node (ref "JP269") (pin "1") (pinfunction "1_1") (pintype "passive"))
    )
    (net (code "177") (name "/58_1440127218") (class "Default")
      (node (ref "JP1016") (pin "P$1") (pinfunction "1_P$1") (pintype "passive"))
      (node (ref "JP272") (pin "1") (pinfunction "1_1") (pintype "passive"))
    )
    (net (code "178") (name "/58_1440127248") (class "Default")
      (node (ref "JP1076") (pin "P$1") (pinfunction "1_P$1") (pintype "passive"))
      (node (ref "JP279") (pin "1") (pinfunction "1_1") (pintype "passive"))
    )
    (net (code "179") (name "/59_1440127218") (class "Default")
      (node (ref "JP1018") (pin "P$1") (pinfunction "1_P$1") (pintype "passive"))
      (node (ref "JP282") (pin "1") (pinfunction "1_1") (pintype "passive"))
    )
    (net (code "180") (name "/59_1440127248") (class "Default")
      (node (ref "JP1078") (pin "P$1") (pinfunction "1_P$1") (pintype "passive"))
      (node (ref "JP289") (pin "1") (pinfunction "1_1") (pintype "passive"))
    )
    (net (code "181") (name "/60_1440127218") (class "Default")
      (node (ref "JP3") (pin "1") (pinfunction "1_1") (pintype "passive"))
      (node (ref "JP901") (pin "P$1") (pinfunction "1_P$1") (pintype "passive"))
    )
    (net (code "182") (name "/60_1440127248") (class "Default")
      (node (ref "JP1081") (pin "P$1") (pinfunction "1_P$1") (pintype "passive"))
      (node (ref "JP8") (pin "1") (pinfunction "1_1") (pintype "passive"))
    )
    (net (code "183") (name "/61_1440127218") (class "Default")
      (node (ref "JP13") (pin "1") (pinfunction "1_1") (pintype "passive"))
      (node (ref "JP903") (pin "P$1") (pinfunction "1_P$1") (pintype "passive"))
    )
    (net (code "184") (name "/61_1440127248") (class "Default")
      (node (ref "JP1083") (pin "P$1") (pinfunction "1_P$1") (pintype "passive"))
      (node (ref "JP18") (pin "1") (pinfunction "1_1") (pintype "passive"))
    )
    (net (code "185") (name "/62_1440127218") (class "Default")
      (node (ref "JP23") (pin "1") (pinfunction "1_1") (pintype "passive"))
      (node (ref "JP905") (pin "P$1") (pinfunction "1_P$1") (pintype "passive"))
    )
    (net (code "186") (name "/62_1440127248") (class "Default")
      (node (ref "JP1085") (pin "P$1") (pinfunction "1_P$1") (pintype "passive"))
      (node (ref "JP28") (pin "1") (pinfunction "1_1") (pintype "passive"))
    )
    (net (code "187") (name "/63_1440127218") (class "Default")
      (node (ref "JP33") (pin "1") (pinfunction "1_1") (pintype "passive"))
      (node (ref "JP907") (pin "P$1") (pinfunction "1_P$1") (pintype "passive"))
    )
    (net (code "188") (name "/63_1440127248") (class "Default")
      (node (ref "JP1087") (pin "P$1") (pinfunction "1_P$1") (pintype "passive"))
      (node (ref "JP38") (pin "1") (pinfunction "1_1") (pintype "passive"))
    )
    (net (code "189") (name "/64_1440127218") (class "Default")
      (node (ref "JP43") (pin "1") (pinfunction "1_1") (pintype "passive"))
      (node (ref "JP909") (pin "P$1") (pinfunction "1_P$1") (pintype "passive"))
    )
    (net (code "190") (name "/64_1440127248") (class "Default")
      (node (ref "JP1089") (pin "P$1") (pinfunction "1_P$1") (pintype "passive"))
      (node (ref "JP48") (pin "1") (pinfunction "1_1") (pintype "passive"))
    )
    (net (code "191") (name "/65_1440127218") (class "Default")
      (node (ref "JP53") (pin "1") (pinfunction "1_1") (pintype "passive"))
      (node (ref "JP911") (pin "P$1") (pinfunction "1_P$1") (pintype "passive"))
    )
    (net (code "192") (name "/65_1440127248") (class "Default")
      (node (ref "JP1091") (pin "P$1") (pinfunction "1_P$1") (pintype "passive"))
      (node (ref "JP58") (pin "1") (pinfunction "1_1") (pintype "passive"))
    )
    (net (code "193") (name "/66_1440127218") (class "Default")
      (node (ref "JP63") (pin "1") (pinfunction "1_1") (pintype "passive"))
      (node (ref "JP913") (pin "P$1") (pinfunction "1_P$1") (pintype "passive"))
    )
    (net (code "194") (name "/66_1440127248") (class "Default")
      (node (ref "JP1093") (pin "P$1") (pinfunction "1_P$1") (pintype "passive"))
      (node (ref "JP68") (pin "1") (pinfunction "1_1") (pintype "passive"))
    )
    (net (code "195") (name "/67_1440127218") (class "Default")
      (node (ref "JP73") (pin "1") (pinfunction "1_1") (pintype "passive"))
      (node (ref "JP915") (pin "P$1") (pinfunction "1_P$1") (pintype "passive"))
    )
    (net (code "196") (name "/67_1440127248") (class "Default")
      (node (ref "JP1095") (pin "P$1") (pinfunction "1_P$1") (pintype "passive"))
      (node (ref "JP78") (pin "1") (pinfunction "1_1") (pintype "passive"))
    )
    (net (code "197") (name "/68_1440127218") (class "Default")
      (node (ref "JP83") (pin "1") (pinfunction "1_1") (pintype "passive"))
      (node (ref "JP917") (pin "P$1") (pinfunction "1_P$1") (pintype "passive"))
    )
    (net (code "198") (name "/68_1440127248") (class "Default")
      (node (ref "JP1097") (pin "P$1") (pinfunction "1_P$1") (pintype "passive"))
      (node (ref "JP88") (pin "1") (pinfunction "1_1") (pintype "passive"))
    )
    (net (code "199") (name "/69_1440127218") (class "Default")
      (node (ref "JP919") (pin "P$1") (pinfunction "1_P$1") (pintype "passive"))
      (node (ref "JP93") (pin "1") (pinfunction "1_1") (pintype "passive"))
    )
    (net (code "200") (name "/69_1440127248") (class "Default")
      (node (ref "JP1099") (pin "P$1") (pinfunction "1_P$1") (pintype "passive"))
      (node (ref "JP98") (pin "1") (pinfunction "1_1") (pintype "passive"))
    )
    (net (code "201") (name "/70_1440127218") (class "Default")
      (node (ref "JP103") (pin "1") (pinfunction "1_1") (pintype "passive"))
      (node (ref "JP921") (pin "P$1") (pinfunction "1_P$1") (pintype "passive"))
    )
    (net (code "202") (name "/70_1440127248") (class "Default")
      (node (ref "JP108") (pin "1") (pinfunction "1_1") (pintype "passive"))
      (node (ref "JP1101") (pin "P$1") (pinfunction "1_P$1") (pintype "passive"))
    )
    (net (code "203") (name "/71_1440127218") (class "Default")
      (node (ref "JP113") (pin "1") (pinfunction "1_1") (pintype "passive"))
      (node (ref "JP923") (pin "P$1") (pinfunction "1_P$1") (pintype "passive"))
    )
    (net (code "204") (name "/71_1440127248") (class "Default")
      (node (ref "JP1103") (pin "P$1") (pinfunction "1_P$1") (pintype "passive"))
      (node (ref "JP118") (pin "1") (pinfunction "1_1") (pintype "passive"))
    )
    (net (code "205") (name "/72_1440127218") (class "Default")
      (node (ref "JP123") (pin "1") (pinfunction "1_1") (pintype "passive"))
      (node (ref "JP925") (pin "P$1") (pinfunction "1_P$1") (pintype "passive"))
    )
    (net (code "206") (name "/72_1440127248") (class "Default")
      (node (ref "JP1105") (pin "P$1") (pinfunction "1_P$1") (pintype "passive"))
      (node (ref "JP128") (pin "1") (pinfunction "1_1") (pintype "passive"))
    )
    (net (code "207") (name "/73_1440127218") (class "Default")
      (node (ref "JP133") (pin "1") (pinfunction "1_1") (pintype "passive"))
      (node (ref "JP927") (pin "P$1") (pinfunction "1_P$1") (pintype "passive"))
    )
    (net (code "208") (name "/73_1440127248") (class "Default")
      (node (ref "JP1107") (pin "P$1") (pinfunction "1_P$1") (pintype "passive"))
      (node (ref "JP138") (pin "1") (pinfunction "1_1") (pintype "passive"))
    )
    (net (code "209") (name "/74_1440127218") (class "Default")
      (node (ref "JP143") (pin "1") (pinfunction "1_1") (pintype "passive"))
      (node (ref "JP929") (pin "P$1") (pinfunction "1_P$1") (pintype "passive"))
    )
    (net (code "210") (name "/74_1440127248") (class "Default")
      (node (ref "JP1109") (pin "P$1") (pinfunction "1_P$1") (pintype "passive"))
      (node (ref "JP148") (pin "1") (pinfunction "1_1") (pintype "passive"))
    )
    (net (code "211") (name "/75_1440127218") (class "Default")
      (node (ref "JP153") (pin "1") (pinfunction "1_1") (pintype "passive"))
      (node (ref "JP931") (pin "P$1") (pinfunction "1_P$1") (pintype "passive"))
    )
    (net (code "212") (name "/75_1440127248") (class "Default")
      (node (ref "JP1111") (pin "P$1") (pinfunction "1_P$1") (pintype "passive"))
      (node (ref "JP158") (pin "1") (pinfunction "1_1") (pintype "passive"))
    )
    (net (code "213") (name "/76_1440127218") (class "Default")
      (node (ref "JP163") (pin "1") (pinfunction "1_1") (pintype "passive"))
      (node (ref "JP933") (pin "P$1") (pinfunction "1_P$1") (pintype "passive"))
    )
    (net (code "214") (name "/76_1440127248") (class "Default")
      (node (ref "JP1113") (pin "P$1") (pinfunction "1_P$1") (pintype "passive"))
      (node (ref "JP168") (pin "1") (pinfunction "1_1") (pintype "passive"))
    )
    (net (code "215") (name "/77_1440127218") (class "Default")
      (node (ref "JP173") (pin "1") (pinfunction "1_1") (pintype "passive"))
      (node (ref "JP935") (pin "P$1") (pinfunction "1_P$1") (pintype "passive"))
    )
    (net (code "216") (name "/77_1440127248") (class "Default")
      (node (ref "JP1115") (pin "P$1") (pinfunction "1_P$1") (pintype "passive"))
      (node (ref "JP178") (pin "1") (pinfunction "1_1") (pintype "passive"))
    )
    (net (code "217") (name "/78_1440127218") (class "Default")
      (node (ref "JP183") (pin "1") (pinfunction "1_1") (pintype "passive"))
      (node (ref "JP937") (pin "P$1") (pinfunction "1_P$1") (pintype "passive"))
    )
    (net (code "218") (name "/78_1440127248") (class "Default")
      (node (ref "JP1117") (pin "P$1") (pinfunction "1_P$1") (pintype "passive"))
      (node (ref "JP188") (pin "1") (pinfunction "1_1") (pintype "passive"))
    )
    (net (code "219") (name "/79_1440127218") (class "Default")
      (node (ref "JP193") (pin "1") (pinfunction "1_1") (pintype "passive"))
      (node (ref "JP939") (pin "P$1") (pinfunction "1_P$1") (pintype "passive"))
    )
    (net (code "220") (name "/79_1440127248") (class "Default")
      (node (ref "JP1119") (pin "P$1") (pinfunction "1_P$1") (pintype "passive"))
      (node (ref "JP198") (pin "1") (pinfunction "1_1") (pintype "passive"))
    )
    (net (code "221") (name "/80_1440127218") (class "Default")
      (node (ref "JP203") (pin "1") (pinfunction "1_1") (pintype "passive"))
      (node (ref "JP941") (pin "P$1") (pinfunction "1_P$1") (pintype "passive"))
    )
    (net (code "222") (name "/80_1440127248") (class "Default")
      (node (ref "JP1121") (pin "P$1") (pinfunction "1_P$1") (pintype "passive"))
      (node (ref "JP208") (pin "1") (pinfunction "1_1") (pintype "passive"))
    )
    (net (code "223") (name "/81_1440127218") (class "Default")
      (node (ref "JP213") (pin "1") (pinfunction "1_1") (pintype "passive"))
      (node (ref "JP943") (pin "P$1") (pinfunction "1_P$1") (pintype "passive"))
    )
    (net (code "224") (name "/81_1440127248") (class "Default")
      (node (ref "JP1123") (pin "P$1") (pinfunction "1_P$1") (pintype "passive"))
      (node (ref "JP218") (pin "1") (pinfunction "1_1") (pintype "passive"))
    )
    (net (code "225") (name "/82_1440127218") (class "Default")
      (node (ref "JP223") (pin "1") (pinfunction "1_1") (pintype "passive"))
      (node (ref "JP945") (pin "P$1") (pinfunction "1_P$1") (pintype "passive"))
    )
    (net (code "226") (name "/82_1440127248") (class "Default")
      (node (ref "JP1125") (pin "P$1") (pinfunction "1_P$1") (pintype "passive"))
      (node (ref "JP228") (pin "1") (pinfunction "1_1") (pintype "passive"))
    )
    (net (code "227") (name "/83_1440127218") (class "Default")
      (node (ref "JP233") (pin "1") (pinfunction "1_1") (pintype "passive"))
      (node (ref "JP947") (pin "P$1") (pinfunction "1_P$1") (pintype "passive"))
    )
    (net (code "228") (name "/83_1440127248") (class "Default")
      (node (ref "JP1127") (pin "P$1") (pinfunction "1_P$1") (pintype "passive"))
      (node (ref "JP238") (pin "1") (pinfunction "1_1") (pintype "passive"))
    )
    (net (code "229") (name "/84_1440127218") (class "Default")
      (node (ref "JP243") (pin "1") (pinfunction "1_1") (pintype "passive"))
      (node (ref "JP949") (pin "P$1") (pinfunction "1_P$1") (pintype "passive"))
    )
    (net (code "230") (name "/84_1440127248") (class "Default")
      (node (ref "JP1129") (pin "P$1") (pinfunction "1_P$1") (pintype "passive"))
      (node (ref "JP248") (pin "1") (pinfunction "1_1") (pintype "passive"))
    )
    (net (code "231") (name "/85_1440127218") (class "Default")
      (node (ref "JP253") (pin "1") (pinfunction "1_1") (pintype "passive"))
      (node (ref "JP951") (pin "P$1") (pinfunction "1_P$1") (pintype "passive"))
    )
    (net (code "232") (name "/85_1440127248") (class "Default")
      (node (ref "JP1131") (pin "P$1") (pinfunction "1_P$1") (pintype "passive"))
      (node (ref "JP258") (pin "1") (pinfunction "1_1") (pintype "passive"))
    )
    (net (code "233") (name "/86_1440127218") (class "Default")
      (node (ref "JP263") (pin "1") (pinfunction "1_1") (pintype "passive"))
      (node (ref "JP953") (pin "P$1") (pinfunction "1_P$1") (pintype "passive"))
    )
    (net (code "234") (name "/86_1440127248") (class "Default")
      (node (ref "JP1133") (pin "P$1") (pinfunction "1_P$1") (pintype "passive"))
      (node (ref "JP268") (pin "1") (pinfunction "1_1") (pintype "passive"))
    )
    (net (code "235") (name "/87_1440127218") (class "Default")
      (node (ref "JP273") (pin "1") (pinfunction "1_1") (pintype "passive"))
      (node (ref "JP955") (pin "P$1") (pinfunction "1_P$1") (pintype "passive"))
    )
    (net (code "236") (name "/87_1440127248") (class "Default")
      (node (ref "JP1135") (pin "P$1") (pinfunction "1_P$1") (pintype "passive"))
      (node (ref "JP278") (pin "1") (pinfunction "1_1") (pintype "passive"))
    )
    (net (code "237") (name "/88_1440127218") (class "Default")
      (node (ref "JP283") (pin "1") (pinfunction "1_1") (pintype "passive"))
      (node (ref "JP957") (pin "P$1") (pinfunction "1_P$1") (pintype "passive"))
    )
    (net (code "238") (name "/88_1440127248") (class "Default")
      (node (ref "JP1137") (pin "P$1") (pinfunction "1_P$1") (pintype "passive"))
      (node (ref "JP288") (pin "1") (pinfunction "1_1") (pintype "passive"))
    )
    (net (code "239") (name "/89_1440127218") (class "Default")
      (node (ref "JP293") (pin "1") (pinfunction "1_1") (pintype "passive"))
      (node (ref "JP959") (pin "P$1") (pinfunction "1_P$1") (pintype "passive"))
    )
    (net (code "240") (name "/89_1440127248") (class "Default")
      (node (ref "JP1139") (pin "P$1") (pinfunction "1_P$1") (pintype "passive"))
      (node (ref "JP298") (pin "1") (pinfunction "1_1") (pintype "passive"))
    )
    (net (code "241") (name "/90_1440127218") (class "Default")
      (node (ref "JP294") (pin "1") (pinfunction "1_1") (pintype "passive"))
      (node (ref "JP960") (pin "P$1") (pinfunction "1_P$1") (pintype "passive"))
    )
    (net (code "242") (name "/90_1440127248") (class "Default")
      (node (ref "JP1140") (pin "P$1") (pinfunction "1_P$1") (pintype "passive"))
      (node (ref "JP297") (pin "1") (pinfunction "1_1") (pintype "passive"))
    )
    (net (code "243") (name "/91_1440127218") (class "Default")
      (node (ref "JP4") (pin "1") (pinfunction "1_1") (pintype "passive"))
      (node (ref "JP902") (pin "P$1") (pinfunction "1_P$1") (pintype "passive"))
    )
    (net (code "244") (name "/91_1440127248") (class "Default")
      (node (ref "JP1082") (pin "P$1") (pinfunction "1_P$1") (pintype "passive"))
      (node (ref "JP7") (pin "1") (pinfunction "1_1") (pintype "passive"))
    )
    (net (code "245") (name "/92_1440127218") (class "Default")
      (node (ref "JP14") (pin "1") (pinfunction "1_1") (pintype "passive"))
      (node (ref "JP904") (pin "P$1") (pinfunction "1_P$1") (pintype "passive"))
    )
    (net (code "246") (name "/92_1440127248") (class "Default")
      (node (ref "JP1084") (pin "P$1") (pinfunction "1_P$1") (pintype "passive"))
      (node (ref "JP17") (pin "1") (pinfunction "1_1") (pintype "passive"))
    )
    (net (code "247") (name "/93_1440127218") (class "Default")
      (node (ref "JP24") (pin "1") (pinfunction "1_1") (pintype "passive"))
      (node (ref "JP906") (pin "P$1") (pinfunction "1_P$1") (pintype "passive"))
    )
    (net (code "248") (name "/93_1440127248") (class "Default")
      (node (ref "JP1086") (pin "P$1") (pinfunction "1_P$1") (pintype "passive"))
      (node (ref "JP27") (pin "1") (pinfunction "1_1") (pintype "passive"))
    )
    (net (code "249") (name "/94_1440127218") (class "Default")
      (node (ref "JP34") (pin "1") (pinfunction "1_1") (pintype "passive"))
      (node (ref "JP908") (pin "P$1") (pinfunction "1_P$1") (pintype "passive"))
    )
    (net (code "250") (name "/94_1440127248") (class "Default")
      (node (ref "JP1088") (pin "P$1") (pinfunction "1_P$1") (pintype "passive"))
      (node (ref "JP37") (pin "1") (pinfunction "1_1") (pintype "passive"))
    )
    (net (code "251") (name "/95_1440127218") (class "Default")
      (node (ref "JP44") (pin "1") (pinfunction "1_1") (pintype "passive"))
      (node (ref "JP910") (pin "P$1") (pinfunction "1_P$1") (pintype "passive"))
    )
    (net (code "252") (name "/95_1440127248") (class "Default")
      (node (ref "JP1090") (pin "P$1") (pinfunction "1_P$1") (pintype "passive"))
      (node (ref "JP47") (pin "1") (pinfunction "1_1") (pintype "passive"))
    )
    (net (code "253") (name "/96_1440127218") (class "Default")
      (node (ref "JP54") (pin "1") (pinfunction "1_1") (pintype "passive"))
      (node (ref "JP912") (pin "P$1") (pinfunction "1_P$1") (pintype "passive"))
    )
    (net (code "254") (name "/96_1440127248") (class "Default")
      (node (ref "JP1092") (pin "P$1") (pinfunction "1_P$1") (pintype "passive"))
      (node (ref "JP57") (pin "1") (pinfunction "1_1") (pintype "passive"))
    )
    (net (code "255") (name "/97_1440127218") (class "Default")
      (node (ref "JP64") (pin "1") (pinfunction "1_1") (pintype "passive"))
      (node (ref "JP914") (pin "P$1") (pinfunction "1_P$1") (pintype "passive"))
    )
    (net (code "256") (name "/97_1440127248") (class "Default")
      (node (ref "JP1094") (pin "P$1") (pinfunction "1_P$1") (pintype "passive"))
      (node (ref "JP67") (pin "1") (pinfunction "1_1") (pintype "passive"))
    )
    (net (code "257") (name "/98_1440127218") (class "Default")
      (node (ref "JP74") (pin "1") (pinfunction "1_1") (pintype "passive"))
      (node (ref "JP916") (pin "P$1") (pinfunction "1_P$1") (pintype "passive"))
    )
    (net (code "258") (name "/98_1440127248") (class "Default")
      (node (ref "JP1096") (pin "P$1") (pinfunction "1_P$1") (pintype "passive"))
      (node (ref "JP77") (pin "1") (pinfunction "1_1") (pintype "passive"))
    )
    (net (code "259") (name "/99_1440127218") (class "Default")
      (node (ref "JP84") (pin "1") (pinfunction "1_1") (pintype "passive"))
      (node (ref "JP918") (pin "P$1") (pinfunction "1_P$1") (pintype "passive"))
    )
    (net (code "260") (name "/99_1440127248") (class "Default")
      (node (ref "JP1098") (pin "P$1") (pinfunction "1_P$1") (pintype "passive"))
      (node (ref "JP87") (pin "1") (pinfunction "1_1") (pintype "passive"))
    )
    (net (code "261") (name "/100_1440127218") (class "Default")
      (node (ref "JP920") (pin "P$1") (pinfunction "1_P$1") (pintype "passive"))
      (node (ref "JP94") (pin "1") (pinfunction "1_1") (pintype "passive"))
    )
    (net (code "262") (name "/100_1440127248") (class "Default")
      (node (ref "JP1100") (pin "P$1") (pinfunction "1_P$1") (pintype "passive"))
      (node (ref "JP97") (pin "1") (pinfunction "1_1") (pintype "passive"))
    )
    (net (code "263") (name "/101_1440127218") (class "Default")
      (node (ref "JP104") (pin "1") (pinfunction "1_1") (pintype "passive"))
      (node (ref "JP922") (pin "P$1") (pinfunction "1_P$1") (pintype "passive"))
    )
    (net (code "264") (name "/101_1440127248") (class "Default")
      (node (ref "JP107") (pin "1") (pinfunction "1_1") (pintype "passive"))
      (node (ref "JP1102") (pin "P$1") (pinfunction "1_P$1") (pintype "passive"))
    )
    (net (code "265") (name "/102_1440127218") (class "Default")
      (node (ref "JP114") (pin "1") (pinfunction "1_1") (pintype "passive"))
      (node (ref "JP924") (pin "P$1") (pinfunction "1_P$1") (pintype "passive"))
    )
    (net (code "266") (name "/102_1440127248") (class "Default")
      (node (ref "JP1104") (pin "P$1") (pinfunction "1_P$1") (pintype "passive"))
      (node (ref "JP117") (pin "1") (pinfunction "1_1") (pintype "passive"))
    )
    (net (code "267") (name "/103_1440127218") (class "Default")
      (node (ref "JP124") (pin "1") (pinfunction "1_1") (pintype "passive"))
      (node (ref "JP926") (pin "P$1") (pinfunction "1_P$1") (pintype "passive"))
    )
    (net (code "268") (name "/103_1440127248") (class "Default")
      (node (ref "JP1106") (pin "P$1") (pinfunction "1_P$1") (pintype "passive"))
      (node (ref "JP127") (pin "1") (pinfunction "1_1") (pintype "passive"))
    )
    (net (code "269") (name "/104_1440127218") (class "Default")
      (node (ref "JP134") (pin "1") (pinfunction "1_1") (pintype "passive"))
      (node (ref "JP928") (pin "P$1") (pinfunction "1_P$1") (pintype "passive"))
    )
    (net (code "270") (name "/104_1440127248") (class "Default")
      (node (ref "JP1108") (pin "P$1") (pinfunction "1_P$1") (pintype "passive"))
      (node (ref "JP137") (pin "1") (pinfunction "1_1") (pintype "passive"))
    )
    (net (code "271") (name "/105_1440127218") (class "Default")
      (node (ref "JP144") (pin "1") (pinfunction "1_1") (pintype "passive"))
      (node (ref "JP930") (pin "P$1") (pinfunction "1_P$1") (pintype "passive"))
    )
    (net (code "272") (name "/105_1440127248") (class "Default")
      (node (ref "JP1110") (pin "P$1") (pinfunction "1_P$1") (pintype "passive"))
      (node (ref "JP147") (pin "1") (pinfunction "1_1") (pintype "passive"))
    )
    (net (code "273") (name "/106_1440127218") (class "Default")
      (node (ref "JP154") (pin "1") (pinfunction "1_1") (pintype "passive"))
      (node (ref "JP932") (pin "P$1") (pinfunction "1_P$1") (pintype "passive"))
    )
    (net (code "274") (name "/106_1440127248") (class "Default")
      (node (ref "JP1112") (pin "P$1") (pinfunction "1_P$1") (pintype "passive"))
      (node (ref "JP157") (pin "1") (pinfunction "1_1") (pintype "passive"))
    )
    (net (code "275") (name "/107_1440127218") (class "Default")
      (node (ref "JP164") (pin "1") (pinfunction "1_1") (pintype "passive"))
      (node (ref "JP934") (pin "P$1") (pinfunction "1_P$1") (pintype "passive"))
    )
    (net (code "276") (name "/107_1440127248") (class "Default")
      (node (ref "JP1114") (pin "P$1") (pinfunction "1_P$1") (pintype "passive"))
      (node (ref "JP167") (pin "1") (pinfunction "1_1") (pintype "passive"))
    )
    (net (code "277") (name "/108_1440127218") (class "Default")
      (node (ref "JP174") (pin "1") (pinfunction "1_1") (pintype "passive"))
      (node (ref "JP936") (pin "P$1") (pinfunction "1_P$1") (pintype "passive"))
    )
    (net (code "278") (name "/108_1440127248") (class "Default")
      (node (ref "JP1116") (pin "P$1") (pinfunction "1_P$1") (pintype "passive"))
      (node (ref "JP177") (pin "1") (pinfunction "1_1") (pintype "passive"))
    )
    (net (code "279") (name "/109_1440127218") (class "Default")
      (node (ref "JP184") (pin "1") (pinfunction "1_1") (pintype "passive"))
      (node (ref "JP938") (pin "P$1") (pinfunction "1_P$1") (pintype "passive"))
    )
    (net (code "280") (name "/109_1440127248") (class "Default")
      (node (ref "JP1118") (pin "P$1") (pinfunction "1_P$1") (pintype "passive"))
      (node (ref "JP187") (pin "1") (pinfunction "1_1") (pintype "passive"))
    )
    (net (code "281") (name "/110_1440127218") (class "Default")
      (node (ref "JP194") (pin "1") (pinfunction "1_1") (pintype "passive"))
      (node (ref "JP940") (pin "P$1") (pinfunction "1_P$1") (pintype "passive"))
    )
    (net (code "282") (name "/110_1440127248") (class "Default")
      (node (ref "JP1120") (pin "P$1") (pinfunction "1_P$1") (pintype "passive"))
      (node (ref "JP197") (pin "1") (pinfunction "1_1") (pintype "passive"))
    )
    (net (code "283") (name "/111_1440127218") (class "Default")
      (node (ref "JP204") (pin "1") (pinfunction "1_1") (pintype "passive"))
      (node (ref "JP942") (pin "P$1") (pinfunction "1_P$1") (pintype "passive"))
    )
    (net (code "284") (name "/111_1440127248") (class "Default")
      (node (ref "JP1122") (pin "P$1") (pinfunction "1_P$1") (pintype "passive"))
      (node (ref "JP207") (pin "1") (pinfunction "1_1") (pintype "passive"))
    )
    (net (code "285") (name "/112_1440127218") (class "Default")
      (node (ref "JP214") (pin "1") (pinfunction "1_1") (pintype "passive"))
      (node (ref "JP944") (pin "P$1") (pinfunction "1_P$1") (pintype "passive"))
    )
    (net (code "286") (name "/112_1440127248") (class "Default")
      (node (ref "JP1124") (pin "P$1") (pinfunction "1_P$1") (pintype "passive"))
      (node (ref "JP217") (pin "1") (pinfunction "1_1") (pintype "passive"))
    )
    (net (code "287") (name "/113_1440127218") (class "Default")
      (node (ref "JP224") (pin "1") (pinfunction "1_1") (pintype "passive"))
      (node (ref "JP946") (pin "P$1") (pinfunction "1_P$1") (pintype "passive"))
    )
    (net (code "288") (name "/113_1440127248") (class "Default")
      (node (ref "JP1126") (pin "P$1") (pinfunction "1_P$1") (pintype "passive"))
      (node (ref "JP227") (pin "1") (pinfunction "1_1") (pintype "passive"))
    )
    (net (code "289") (name "/114_1440127218") (class "Default")
      (node (ref "JP234") (pin "1") (pinfunction "1_1") (pintype "passive"))
      (node (ref "JP948") (pin "P$1") (pinfunction "1_P$1") (pintype "passive"))
    )
    (net (code "290") (name "/114_1440127248") (class "Default")
      (node (ref "JP1128") (pin "P$1") (pinfunction "1_P$1") (pintype "passive"))
      (node (ref "JP237") (pin "1") (pinfunction "1_1") (pintype "passive"))
    )
    (net (code "291") (name "/115_1440127218") (class "Default")
      (node (ref "JP244") (pin "1") (pinfunction "1_1") (pintype "passive"))
      (node (ref "JP950") (pin "P$1") (pinfunction "1_P$1") (pintype "passive"))
    )
    (net (code "292") (name "/115_1440127248") (class "Default")
      (node (ref "JP1130") (pin "P$1") (pinfunction "1_P$1") (pintype "passive"))
      (node (ref "JP247") (pin "1") (pinfunction "1_1") (pintype "passive"))
    )
    (net (code "293") (name "/116_1440127218") (class "Default")
      (node (ref "JP254") (pin "1") (pinfunction "1_1") (pintype "passive"))
      (node (ref "JP952") (pin "P$1") (pinfunction "1_P$1") (pintype "passive"))
    )
    (net (code "294") (name "/116_1440127248") (class "Default")
      (node (ref "JP1132") (pin "P$1") (pinfunction "1_P$1") (pintype "passive"))
      (node (ref "JP257") (pin "1") (pinfunction "1_1") (pintype "passive"))
    )
    (net (code "295") (name "/117_1440127218") (class "Default")
      (node (ref "JP264") (pin "1") (pinfunction "1_1") (pintype "passive"))
      (node (ref "JP954") (pin "P$1") (pinfunction "1_P$1") (pintype "passive"))
    )
    (net (code "296") (name "/117_1440127248") (class "Default")
      (node (ref "JP1134") (pin "P$1") (pinfunction "1_P$1") (pintype "passive"))
      (node (ref "JP267") (pin "1") (pinfunction "1_1") (pintype "passive"))
    )
    (net (code "297") (name "/118_1440127218") (class "Default")
      (node (ref "JP274") (pin "1") (pinfunction "1_1") (pintype "passive"))
      (node (ref "JP956") (pin "P$1") (pinfunction "1_P$1") (pintype "passive"))
    )
    (net (code "298") (name "/118_1440127248") (class "Default")
      (node (ref "JP1136") (pin "P$1") (pinfunction "1_P$1") (pintype "passive"))
      (node (ref "JP277") (pin "1") (pinfunction "1_1") (pintype "passive"))
    )
    (net (code "299") (name "/119_1440127218") (class "Default")
      (node (ref "JP284") (pin "1") (pinfunction "1_1") (pintype "passive"))
      (node (ref "JP958") (pin "P$1") (pinfunction "1_P$1") (pintype "passive"))
    )
    (net (code "300") (name "/119_1440127248") (class "Default")
      (node (ref "JP1138") (pin "P$1") (pinfunction "1_P$1") (pintype "passive"))
      (node (ref "JP287") (pin "1") (pinfunction "1_1") (pintype "passive"))
    )
  )
)
